# bm812inl.net
KiCad netlist of a schematic drawn in EAGLE
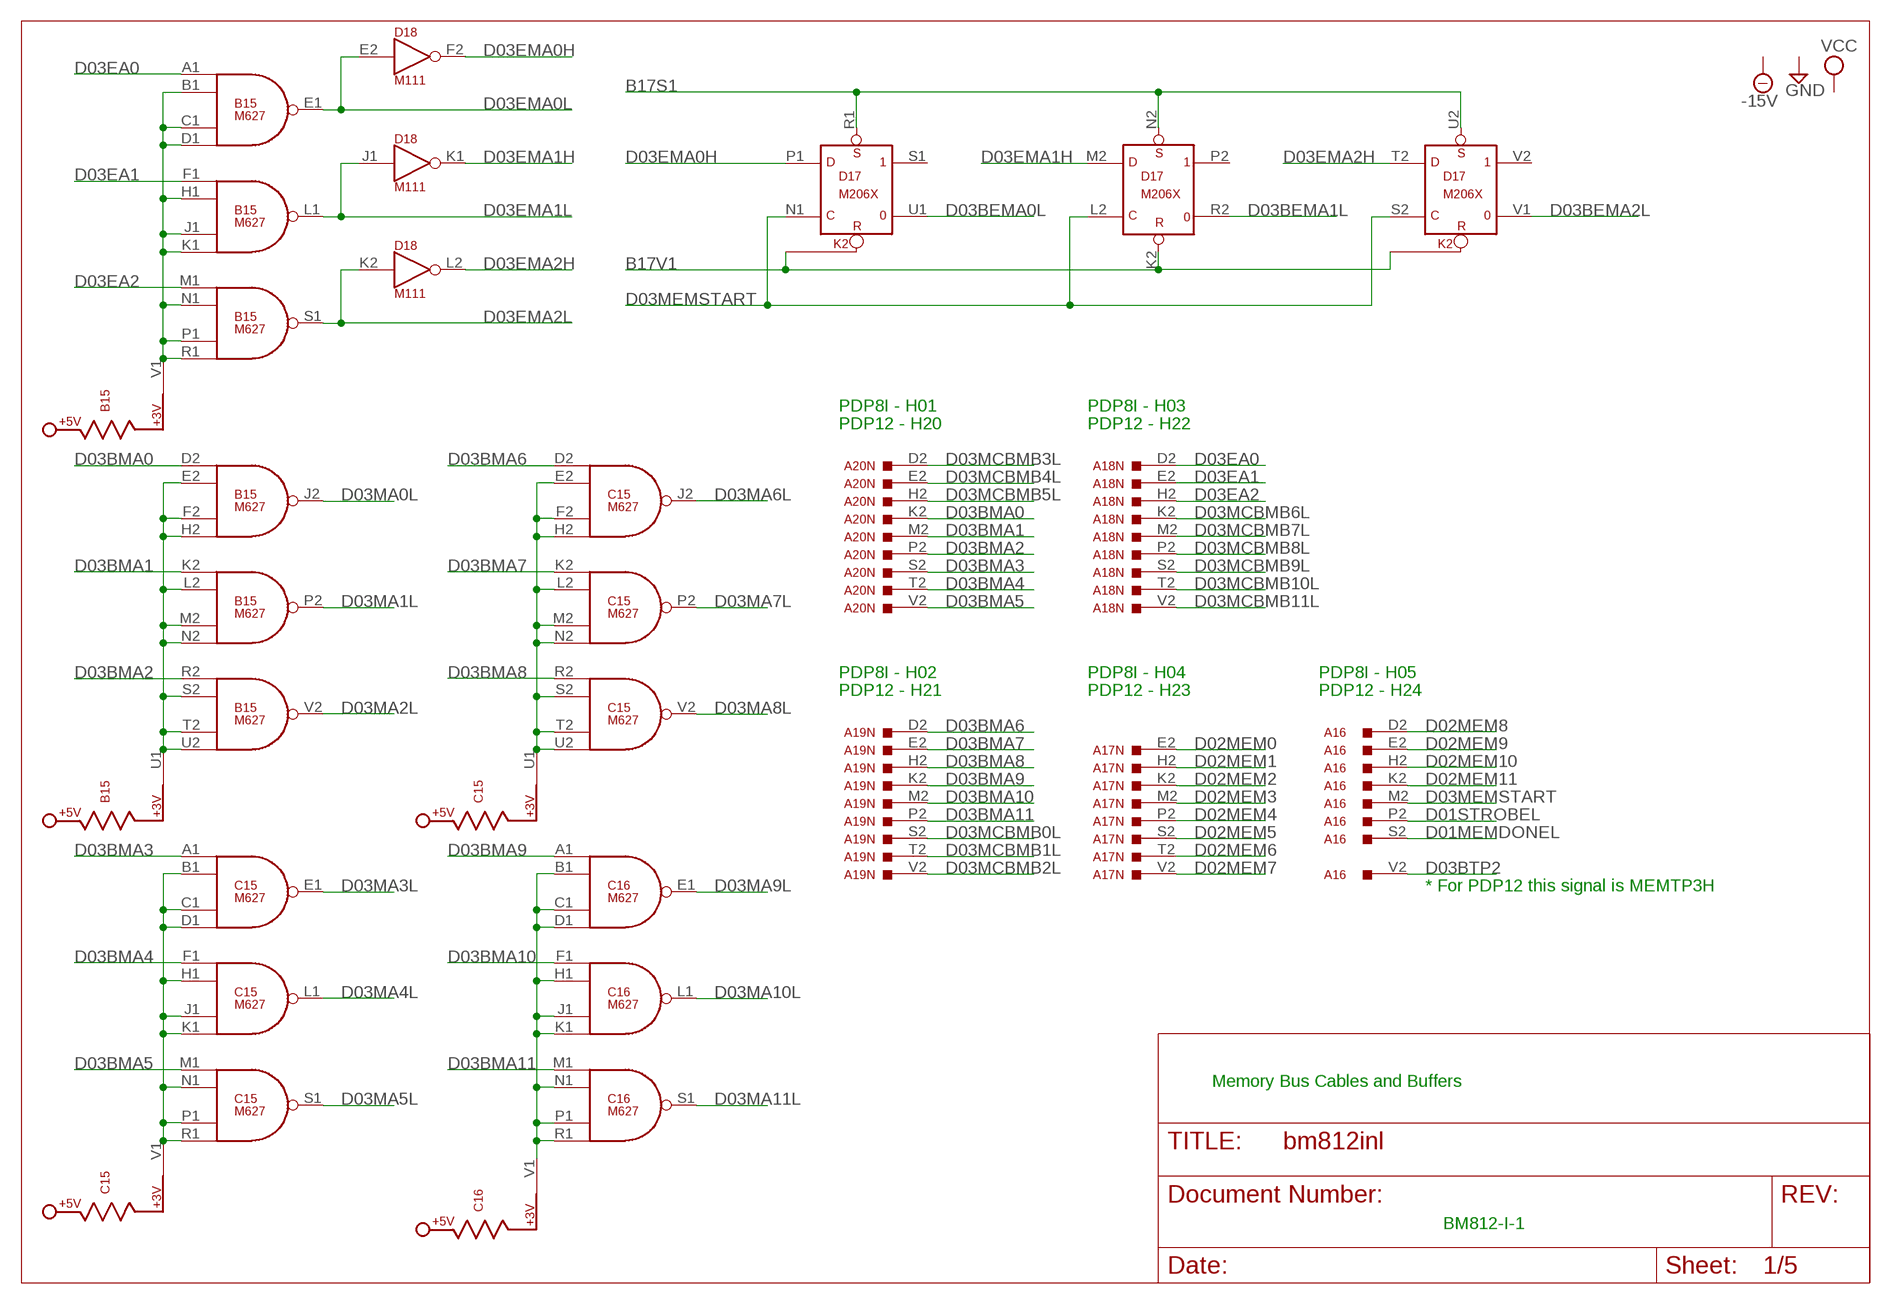
[diagram p0: schematic, sheet 1]
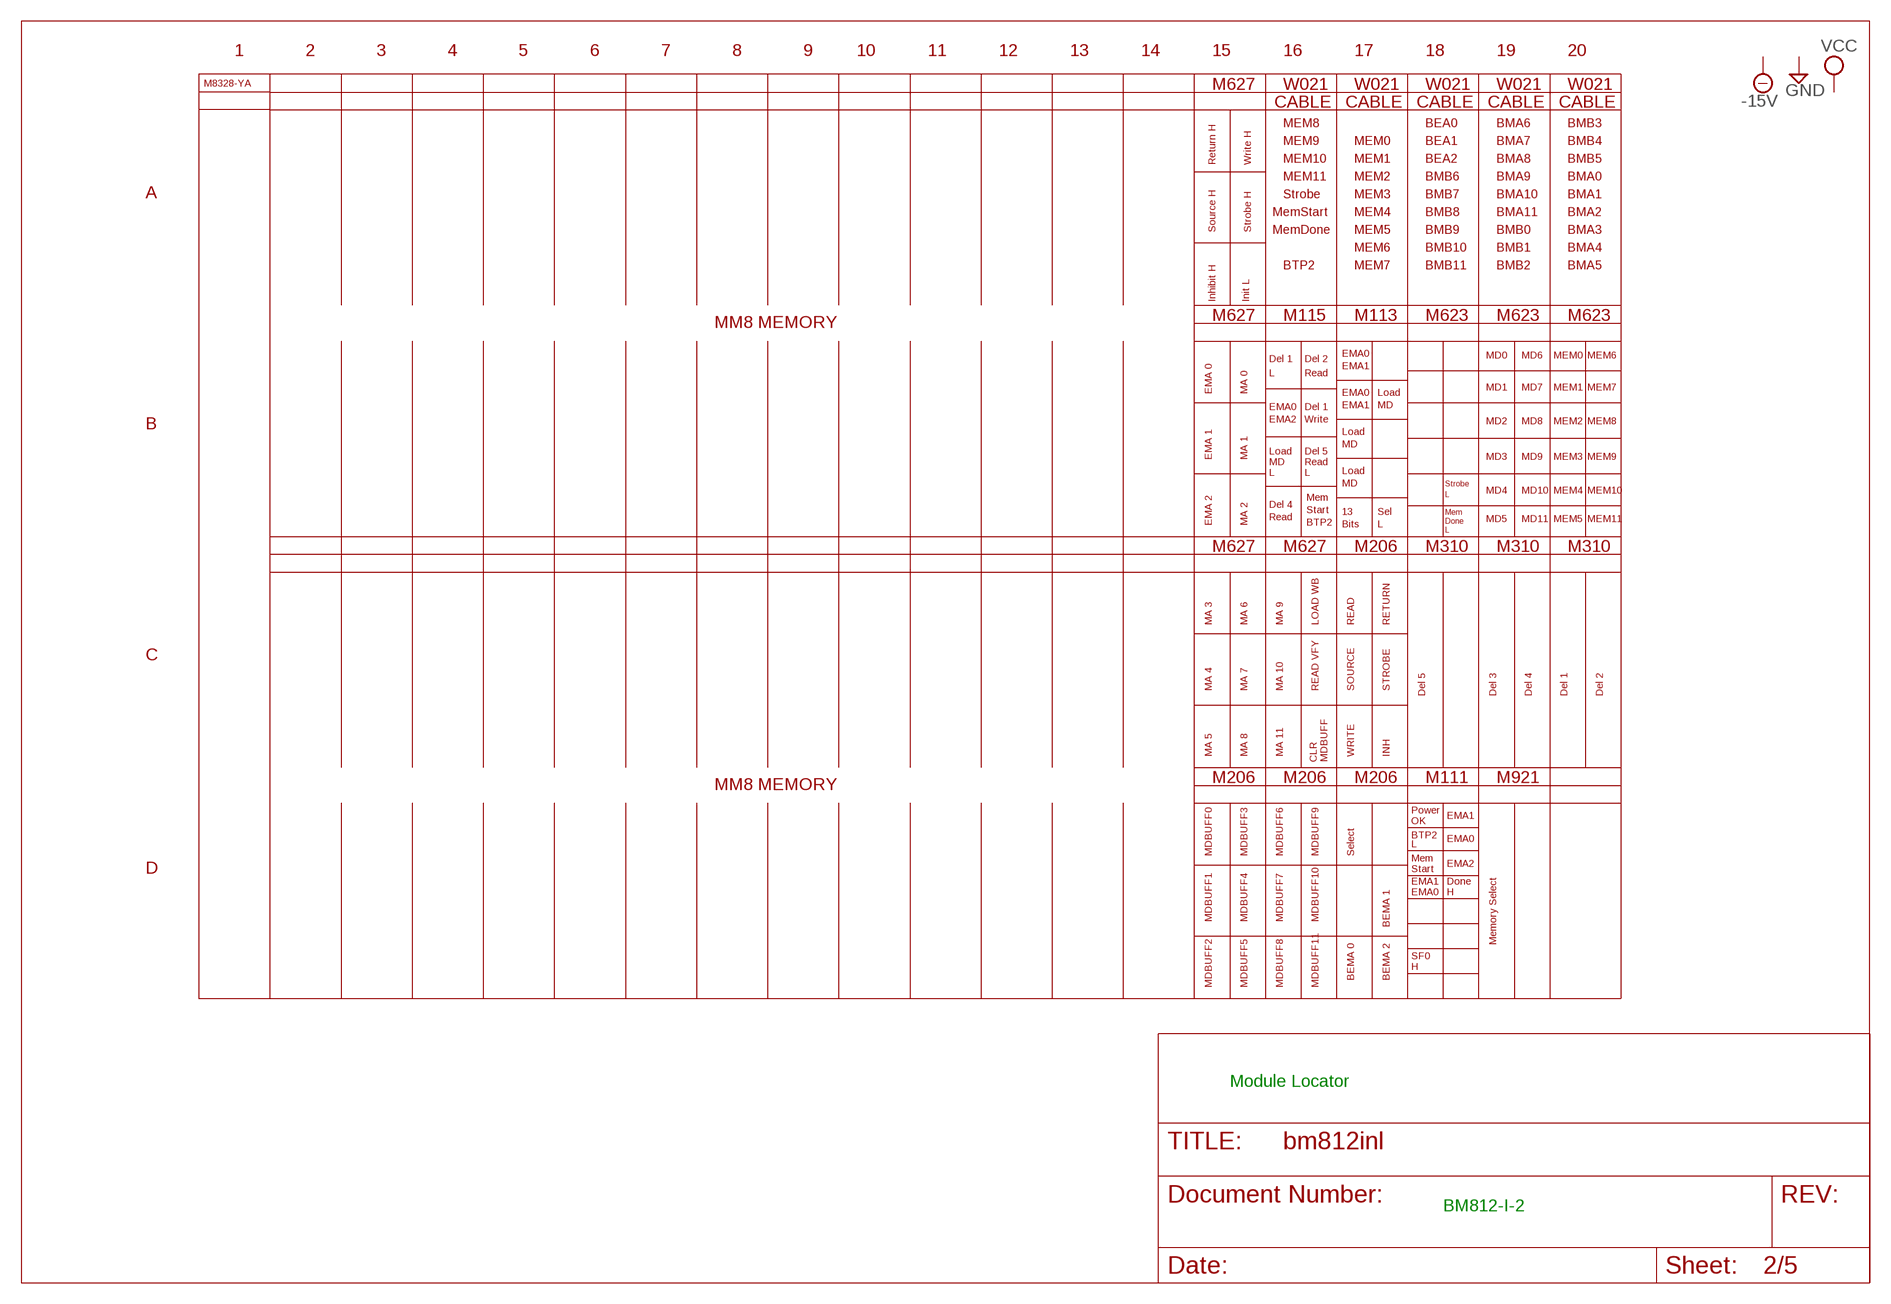
[diagram p1: schematic, sheet 2]
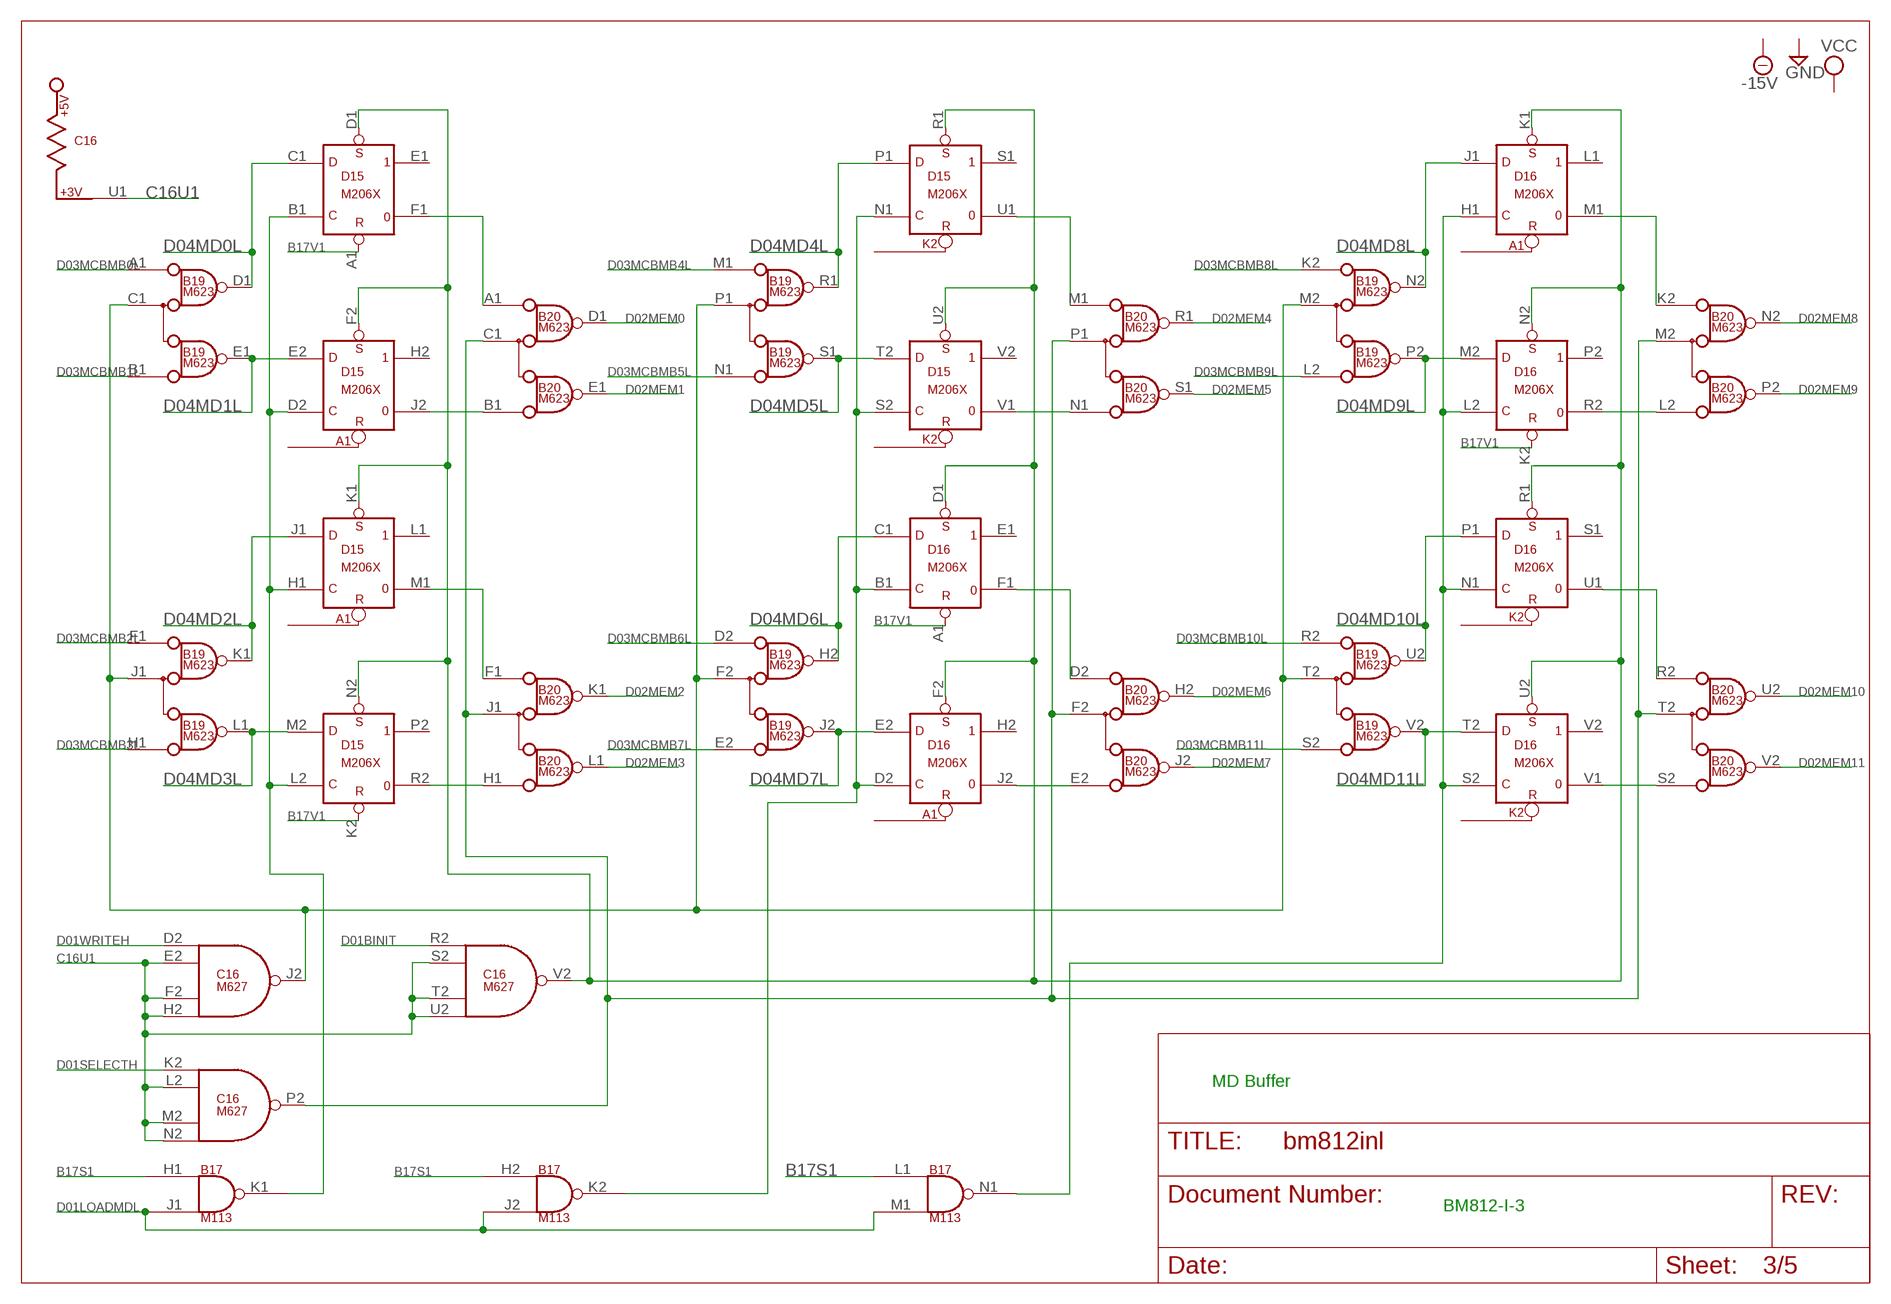
[diagram p2: schematic, sheet 3]
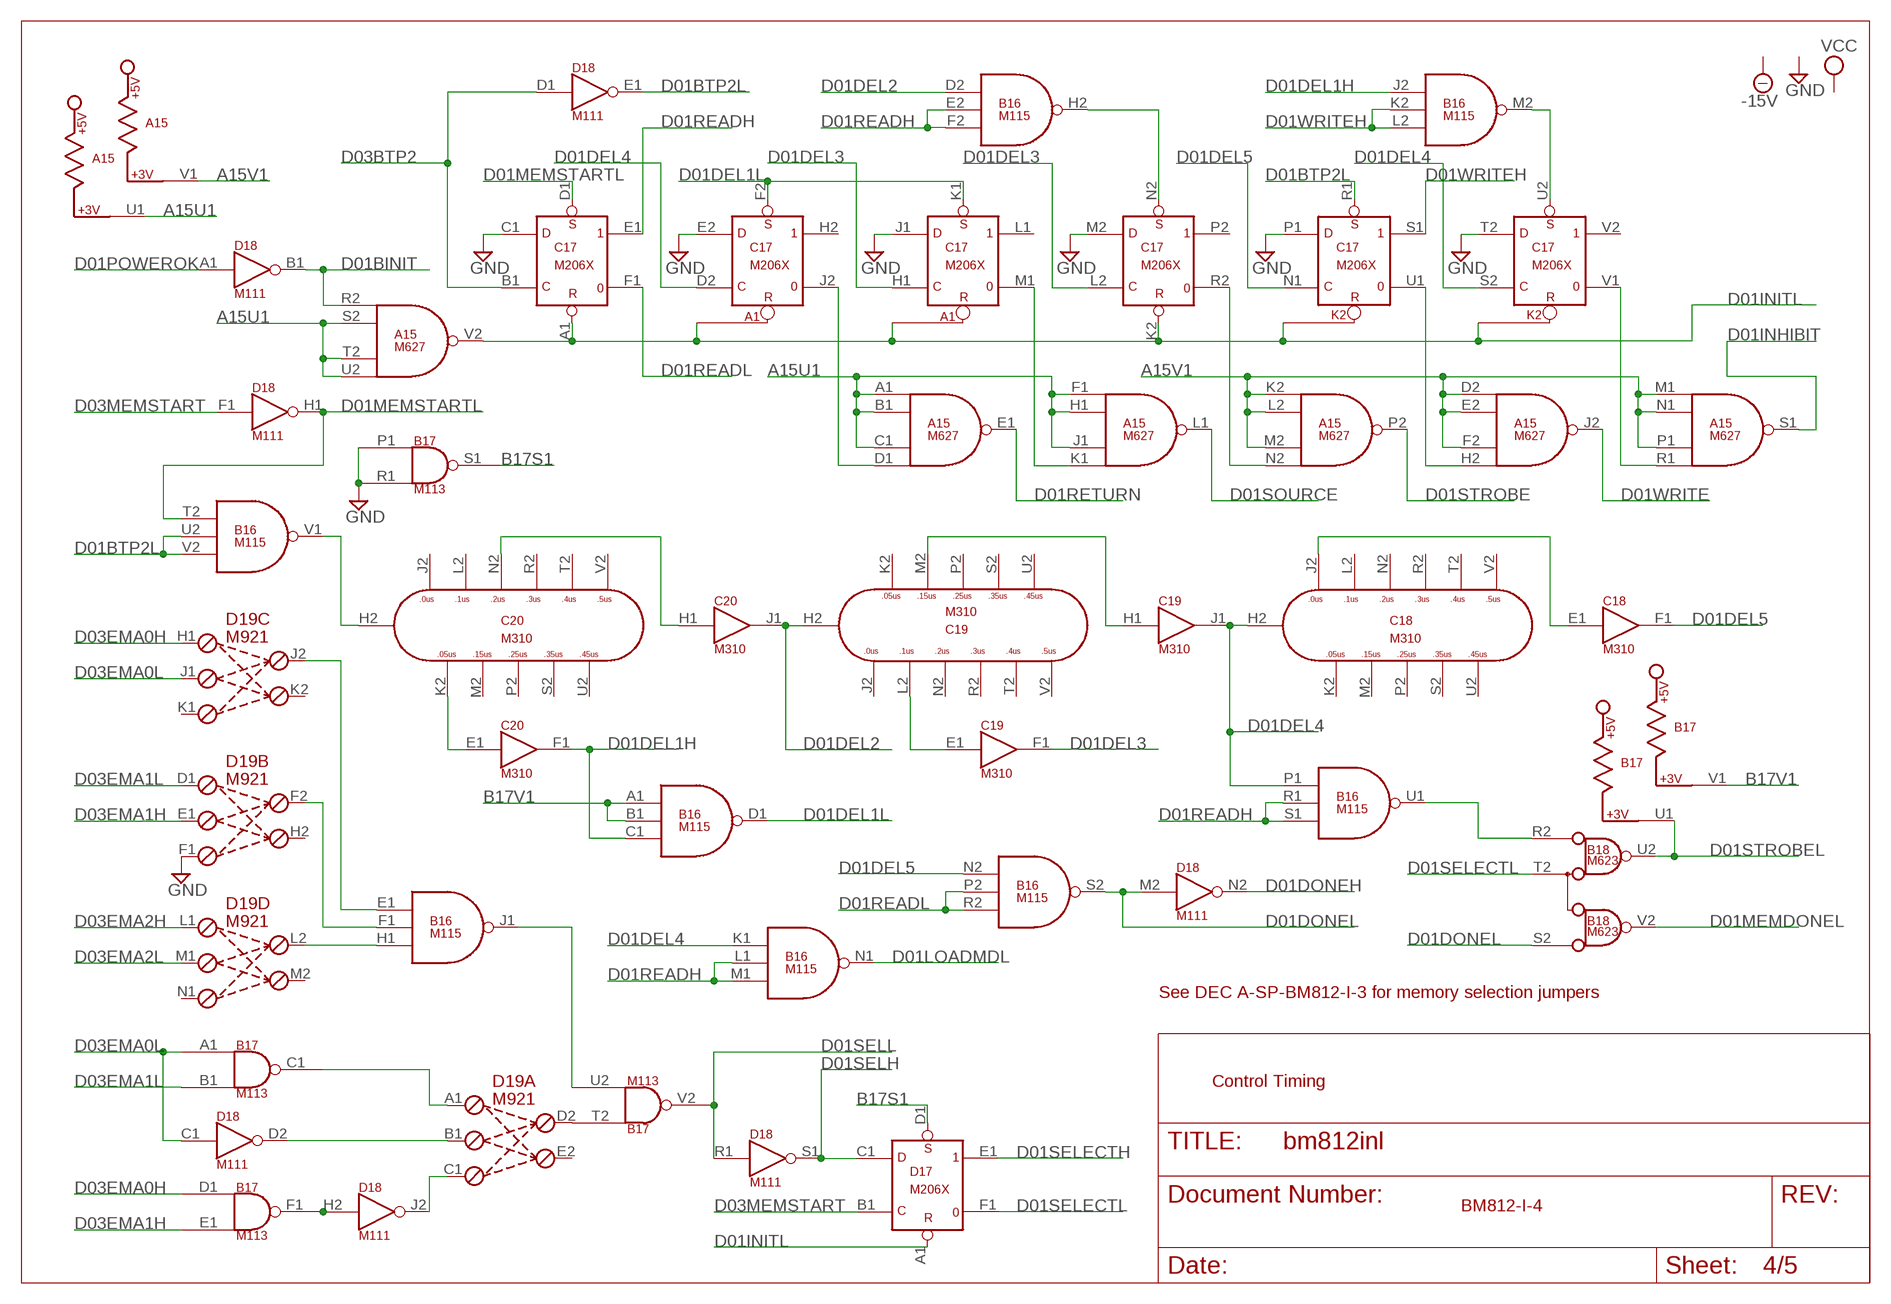
[diagram p3: schematic, sheet 4]
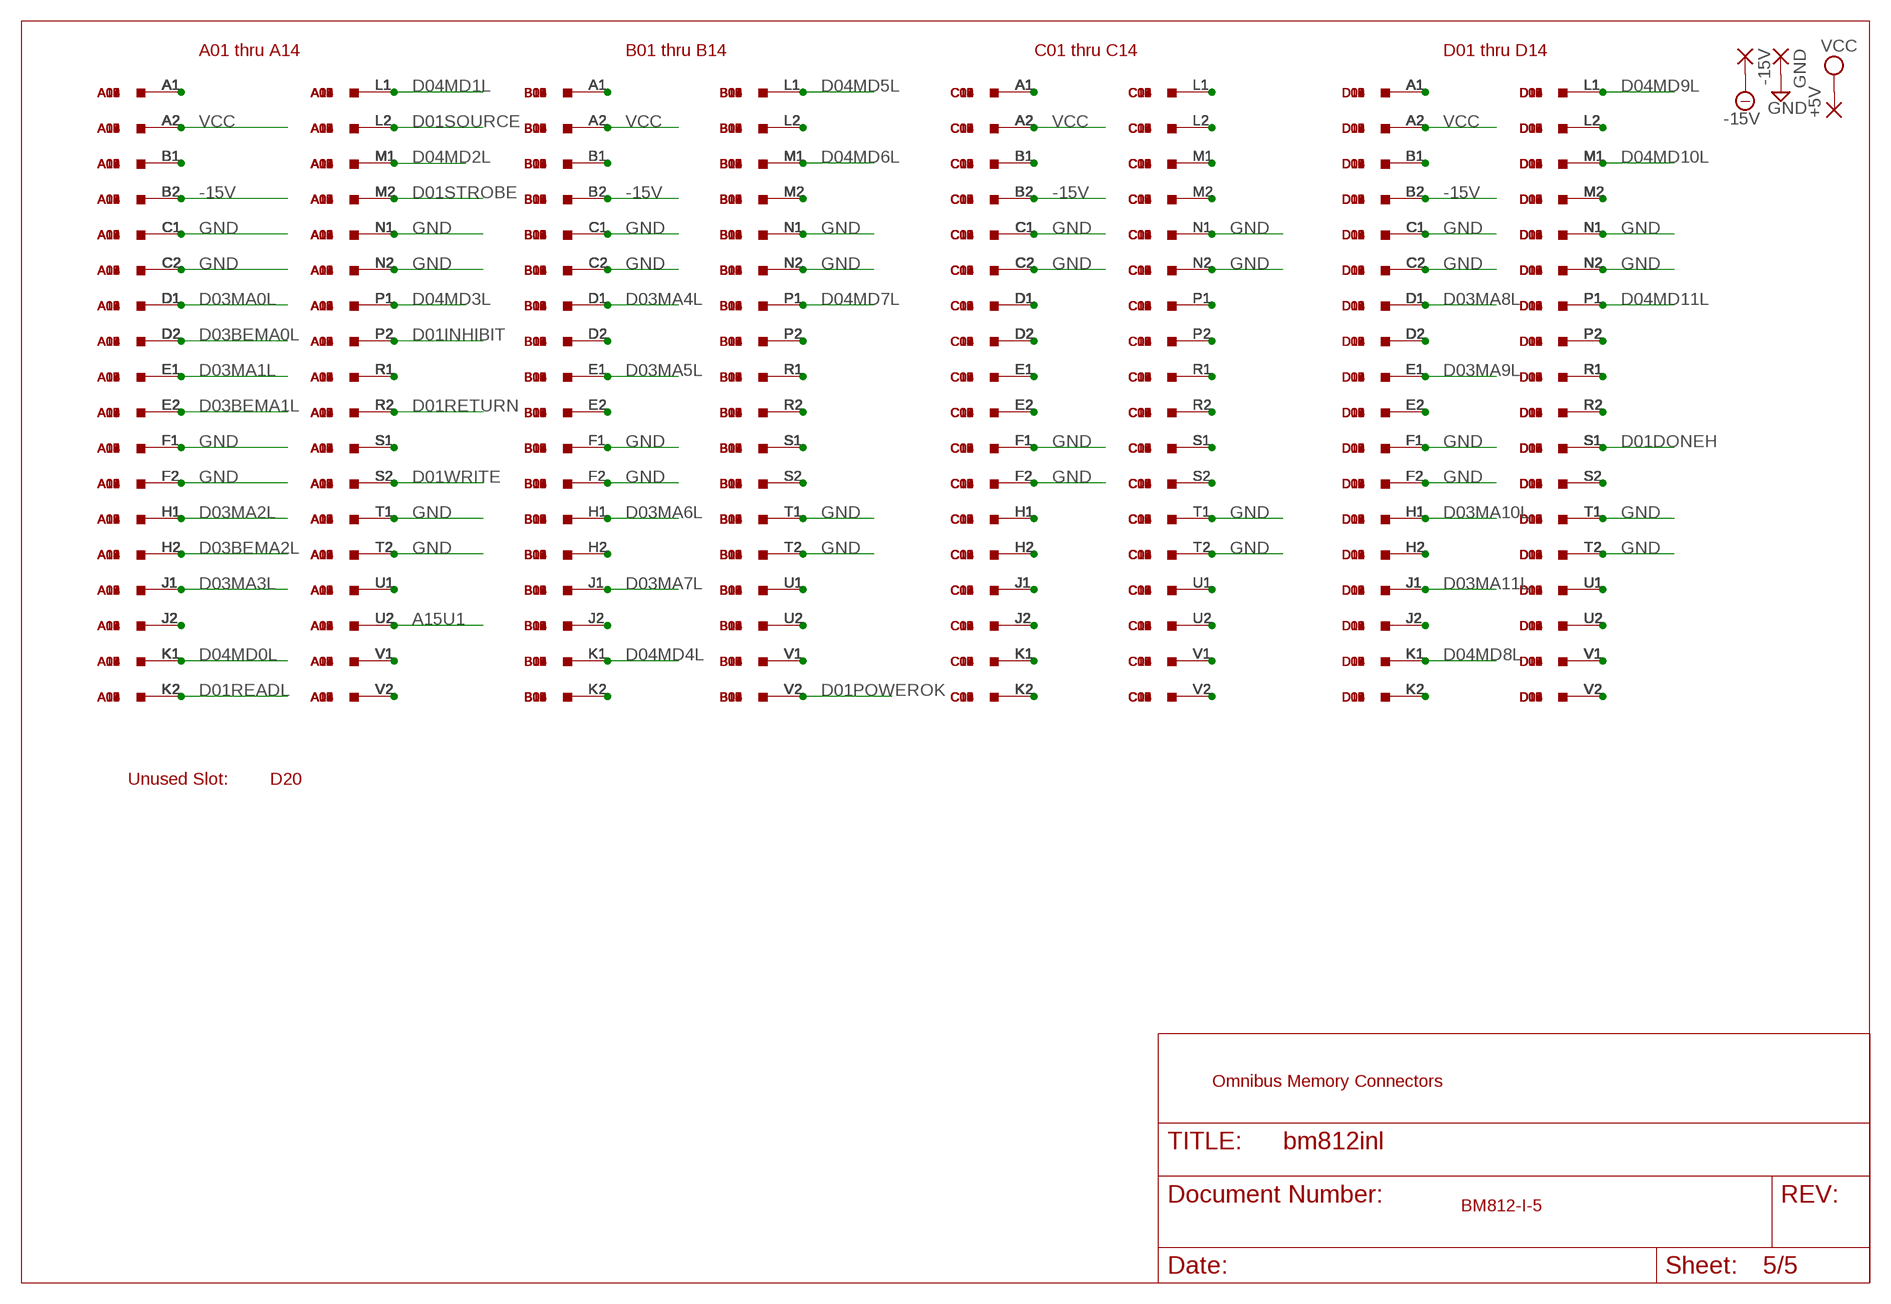
[diagram p4: schematic, sheet 5]

(export (version "E")
  (design (tool "Eeschema 10.0.6"))
  (components
    (comp (ref "A16")
      (value "M903")
      (footprint "eagle-import:H807")
      (libsource (lib "eagle-import") (part "M903"))
    )
    (comp (ref "A17N")
      (value "M903")
      (footprint "eagle-import:H807")
      (libsource (lib "eagle-import") (part "M903"))
    )
    (comp (ref "A18N")
      (value "M903")
      (footprint "eagle-import:H807")
      (libsource (lib "eagle-import") (part "M903"))
    )
    (comp (ref "A19N")
      (value "M903")
      (footprint "eagle-import:H807")
      (libsource (lib "eagle-import") (part "M903"))
    )
    (comp (ref "A20N")
      (value "M903")
      (footprint "eagle-import:H807")
      (libsource (lib "eagle-import") (part "M903"))
    )
    (comp (ref "B15")
      (value "M627")
      (footprint "eagle-import:H807")
      (libsource (lib "eagle-import") (part "M627"))
    )
    (comp (ref "C15")
      (value "M627")
      (footprint "eagle-import:H807")
      (libsource (lib "eagle-import") (part "M627"))
    )
    (comp (ref "C16")
      (value "M627")
      (footprint "eagle-import:H807")
      (libsource (lib "eagle-import") (part "M627"))
    )
    (comp (ref "D17")
      (value "M206X")
      (footprint "eagle-import:H807")
      (libsource (lib "eagle-import") (part "M206X"))
    )
    (comp (ref "D18")
      (value "M111")
      (footprint "eagle-import:H807")
      (libsource (lib "eagle-import") (part "M111"))
    )
    (comp (ref "A15")
      (value "M627")
      (footprint "eagle-import:H807")
      (libsource (lib "eagle-import") (part "M627"))
    )
    (comp (ref "B16")
      (value "M115")
      (footprint "eagle-import:H807")
      (libsource (lib "eagle-import") (part "M115"))
    )
    (comp (ref "B17")
      (value "M113")
      (footprint "eagle-import:H807")
      (libsource (lib "eagle-import") (part "M113"))
    )
    (comp (ref "B18")
      (value "M623")
      (footprint "eagle-import:H807")
      (libsource (lib "eagle-import") (part "M623"))
    )
    (comp (ref "C17")
      (value "M206X")
      (footprint "eagle-import:H807")
      (libsource (lib "eagle-import") (part "M206X"))
    )
    (comp (ref "C18")
      (value "M310")
      (footprint "eagle-import:H807")
      (libsource (lib "eagle-import") (part "M310"))
    )
    (comp (ref "C19")
      (value "M310")
      (footprint "eagle-import:H807")
      (libsource (lib "eagle-import") (part "M310"))
    )
    (comp (ref "C20")
      (value "M310")
      (footprint "eagle-import:H807")
      (libsource (lib "eagle-import") (part "M310"))
    )
    (comp (ref "D19")
      (value "M921")
      (footprint "eagle-import:H807")
      (libsource (lib "eagle-import") (part "M921"))
    )
    (comp (ref "+5V")
      (value "2,54/0,8")
      (footprint "eagle-import:2,54_0,8")
      (libsource (lib "eagle-import") (part "2,54/0,8"))
    )
    (comp (ref "-15V")
      (value "2,54/0,8")
      (footprint "eagle-import:2,54_0,8")
      (libsource (lib "eagle-import") (part "2,54/0,8"))
    )
    (comp (ref "A01")
      (value "M916")
      (footprint "eagle-import:H807")
      (libsource (lib "eagle-import") (part "M916"))
    )
    (comp (ref "A02")
      (value "M916")
      (footprint "eagle-import:H807")
      (libsource (lib "eagle-import") (part "M916"))
    )
    (comp (ref "A03")
      (value "M916")
      (footprint "eagle-import:H807")
      (libsource (lib "eagle-import") (part "M916"))
    )
    (comp (ref "A04")
      (value "M916")
      (footprint "eagle-import:H807")
      (libsource (lib "eagle-import") (part "M916"))
    )
    (comp (ref "A05")
      (value "M916")
      (footprint "eagle-import:H807")
      (libsource (lib "eagle-import") (part "M916"))
    )
    (comp (ref "A06")
      (value "M916")
      (footprint "eagle-import:H807")
      (libsource (lib "eagle-import") (part "M916"))
    )
    (comp (ref "A07")
      (value "M916")
      (footprint "eagle-import:H807")
      (libsource (lib "eagle-import") (part "M916"))
    )
    (comp (ref "A08")
      (value "M916")
      (footprint "eagle-import:H807")
      (libsource (lib "eagle-import") (part "M916"))
    )
    (comp (ref "A09")
      (value "M916")
      (footprint "eagle-import:H807")
      (libsource (lib "eagle-import") (part "M916"))
    )
    (comp (ref "A10")
      (value "M916")
      (footprint "eagle-import:H807")
      (libsource (lib "eagle-import") (part "M916"))
    )
    (comp (ref "A11")
      (value "M916")
      (footprint "eagle-import:H807")
      (libsource (lib "eagle-import") (part "M916"))
    )
    (comp (ref "A12")
      (value "M916")
      (footprint "eagle-import:H807")
      (libsource (lib "eagle-import") (part "M916"))
    )
    (comp (ref "A13")
      (value "M916")
      (footprint "eagle-import:H807")
      (libsource (lib "eagle-import") (part "M916"))
    )
    (comp (ref "A14")
      (value "M916")
      (footprint "eagle-import:H807")
      (libsource (lib "eagle-import") (part "M916"))
    )
    (comp (ref "B01")
      (value "M916")
      (footprint "eagle-import:H807")
      (libsource (lib "eagle-import") (part "M916"))
    )
    (comp (ref "B02")
      (value "M916")
      (footprint "eagle-import:H807")
      (libsource (lib "eagle-import") (part "M916"))
    )
    (comp (ref "B03")
      (value "M916")
      (footprint "eagle-import:H807")
      (libsource (lib "eagle-import") (part "M916"))
    )
    (comp (ref "B04")
      (value "M916")
      (footprint "eagle-import:H807")
      (libsource (lib "eagle-import") (part "M916"))
    )
    (comp (ref "B05")
      (value "M916")
      (footprint "eagle-import:H807")
      (libsource (lib "eagle-import") (part "M916"))
    )
    (comp (ref "B06")
      (value "M916")
      (footprint "eagle-import:H807")
      (libsource (lib "eagle-import") (part "M916"))
    )
    (comp (ref "B07")
      (value "M916")
      (footprint "eagle-import:H807")
      (libsource (lib "eagle-import") (part "M916"))
    )
    (comp (ref "B08")
      (value "M916")
      (footprint "eagle-import:H807")
      (libsource (lib "eagle-import") (part "M916"))
    )
    (comp (ref "B09")
      (value "M916")
      (footprint "eagle-import:H807")
      (libsource (lib "eagle-import") (part "M916"))
    )
    (comp (ref "B10")
      (value "M916")
      (footprint "eagle-import:H807")
      (libsource (lib "eagle-import") (part "M916"))
    )
    (comp (ref "B11")
      (value "M916")
      (footprint "eagle-import:H807")
      (libsource (lib "eagle-import") (part "M916"))
    )
    (comp (ref "B12")
      (value "M916")
      (footprint "eagle-import:H807")
      (libsource (lib "eagle-import") (part "M916"))
    )
    (comp (ref "B13")
      (value "M916")
      (footprint "eagle-import:H807")
      (libsource (lib "eagle-import") (part "M916"))
    )
    (comp (ref "B14")
      (value "M916")
      (footprint "eagle-import:H807")
      (libsource (lib "eagle-import") (part "M916"))
    )
    (comp (ref "C01")
      (value "M916")
      (footprint "eagle-import:H807")
      (libsource (lib "eagle-import") (part "M916"))
    )
    (comp (ref "C02")
      (value "M916")
      (footprint "eagle-import:H807")
      (libsource (lib "eagle-import") (part "M916"))
    )
    (comp (ref "C03")
      (value "M916")
      (footprint "eagle-import:H807")
      (libsource (lib "eagle-import") (part "M916"))
    )
    (comp (ref "C04")
      (value "M916")
      (footprint "eagle-import:H807")
      (libsource (lib "eagle-import") (part "M916"))
    )
    (comp (ref "C05")
      (value "M916")
      (footprint "eagle-import:H807")
      (libsource (lib "eagle-import") (part "M916"))
    )
    (comp (ref "C06")
      (value "M916")
      (footprint "eagle-import:H807")
      (libsource (lib "eagle-import") (part "M916"))
    )
    (comp (ref "C07")
      (value "M916")
      (footprint "eagle-import:H807")
      (libsource (lib "eagle-import") (part "M916"))
    )
    (comp (ref "C08")
      (value "M916")
      (footprint "eagle-import:H807")
      (libsource (lib "eagle-import") (part "M916"))
    )
    (comp (ref "C09")
      (value "M916")
      (footprint "eagle-import:H807")
      (libsource (lib "eagle-import") (part "M916"))
    )
    (comp (ref "C10")
      (value "M916")
      (footprint "eagle-import:H807")
      (libsource (lib "eagle-import") (part "M916"))
    )
    (comp (ref "C11")
      (value "M916")
      (footprint "eagle-import:H807")
      (libsource (lib "eagle-import") (part "M916"))
    )
    (comp (ref "C12")
      (value "M916")
      (footprint "eagle-import:H807")
      (libsource (lib "eagle-import") (part "M916"))
    )
    (comp (ref "C13")
      (value "M916")
      (footprint "eagle-import:H807")
      (libsource (lib "eagle-import") (part "M916"))
    )
    (comp (ref "C14")
      (value "M916")
      (footprint "eagle-import:H807")
      (libsource (lib "eagle-import") (part "M916"))
    )
    (comp (ref "D01")
      (value "M916")
      (footprint "eagle-import:H807")
      (libsource (lib "eagle-import") (part "M916"))
    )
    (comp (ref "D02")
      (value "M916")
      (footprint "eagle-import:H807")
      (libsource (lib "eagle-import") (part "M916"))
    )
    (comp (ref "D03")
      (value "M916")
      (footprint "eagle-import:H807")
      (libsource (lib "eagle-import") (part "M916"))
    )
    (comp (ref "D04")
      (value "M916")
      (footprint "eagle-import:H807")
      (libsource (lib "eagle-import") (part "M916"))
    )
    (comp (ref "D05")
      (value "M916")
      (footprint "eagle-import:H807")
      (libsource (lib "eagle-import") (part "M916"))
    )
    (comp (ref "D06")
      (value "M916")
      (footprint "eagle-import:H807")
      (libsource (lib "eagle-import") (part "M916"))
    )
    (comp (ref "D07")
      (value "M916")
      (footprint "eagle-import:H807")
      (libsource (lib "eagle-import") (part "M916"))
    )
    (comp (ref "D08")
      (value "M916")
      (footprint "eagle-import:H807")
      (libsource (lib "eagle-import") (part "M916"))
    )
    (comp (ref "D09")
      (value "M916")
      (footprint "eagle-import:H807")
      (libsource (lib "eagle-import") (part "M916"))
    )
    (comp (ref "D10")
      (value "M916")
      (footprint "eagle-import:H807")
      (libsource (lib "eagle-import") (part "M916"))
    )
    (comp (ref "D11")
      (value "M916")
      (footprint "eagle-import:H807")
      (libsource (lib "eagle-import") (part "M916"))
    )
    (comp (ref "D12")
      (value "M916")
      (footprint "eagle-import:H807")
      (libsource (lib "eagle-import") (part "M916"))
    )
    (comp (ref "D13")
      (value "M916")
      (footprint "eagle-import:H807")
      (libsource (lib "eagle-import") (part "M916"))
    )
    (comp (ref "D14")
      (value "M916")
      (footprint "eagle-import:H807")
      (libsource (lib "eagle-import") (part "M916"))
    )
    (comp (ref "D20")
      (value "H807")
      (footprint "eagle-import:H807")
      (libsource (lib "eagle-import") (part "H807"))
    )
    (comp (ref "GND")
      (value "2,54/0,8")
      (footprint "eagle-import:2,54_0,8")
      (libsource (lib "eagle-import") (part "2,54/0,8"))
    )
    (comp (ref "B19")
      (value "M623")
      (footprint "eagle-import:H807")
      (libsource (lib "eagle-import") (part "M623"))
    )
    (comp (ref "B20")
      (value "M623")
      (footprint "eagle-import:H807")
      (libsource (lib "eagle-import") (part "M623"))
    )
    (comp (ref "D15")
      (value "M206X")
      (footprint "eagle-import:H807")
      (libsource (lib "eagle-import") (part "M206X"))
    )
    (comp (ref "D16")
      (value "M206X")
      (footprint "eagle-import:H807")
      (libsource (lib "eagle-import") (part "M206X"))
    )
  )
  (nets
    (net (code "1") (name "-15V") (class "Default")
      (node (ref "-15V") (pin "1") (pinfunction "P_1") (pintype "passive"))
      (node (ref "A01") (pin "B2") (pinfunction "P$2_B2") (pintype "bidirectional"))
      (node (ref "A02") (pin "B2") (pinfunction "P$2_B2") (pintype "bidirectional"))
      (node (ref "A03") (pin "B2") (pinfunction "P$2_B2") (pintype "bidirectional"))
      (node (ref "A04") (pin "B2") (pinfunction "P$2_B2") (pintype "bidirectional"))
      (node (ref "A05") (pin "B2") (pinfunction "P$2_B2") (pintype "bidirectional"))
      (node (ref "A06") (pin "B2") (pinfunction "P$2_B2") (pintype "bidirectional"))
      (node (ref "A07") (pin "B2") (pinfunction "P$2_B2") (pintype "bidirectional"))
      (node (ref "A08") (pin "B2") (pinfunction "P$2_B2") (pintype "bidirectional"))
      (node (ref "A09") (pin "B2") (pinfunction "P$2_B2") (pintype "bidirectional"))
      (node (ref "A10") (pin "B2") (pinfunction "P$2_B2") (pintype "bidirectional"))
      (node (ref "A11") (pin "B2") (pinfunction "P$2_B2") (pintype "bidirectional"))
      (node (ref "A12") (pin "B2") (pinfunction "P$2_B2") (pintype "bidirectional"))
      (node (ref "A13") (pin "B2") (pinfunction "P$2_B2") (pintype "bidirectional"))
      (node (ref "A14") (pin "B2") (pinfunction "P$2_B2") (pintype "bidirectional"))
      (node (ref "B01") (pin "B2") (pinfunction "P$2_B2") (pintype "bidirectional"))
      (node (ref "B02") (pin "B2") (pinfunction "P$2_B2") (pintype "bidirectional"))
      (node (ref "B03") (pin "B2") (pinfunction "P$2_B2") (pintype "bidirectional"))
      (node (ref "B04") (pin "B2") (pinfunction "P$2_B2") (pintype "bidirectional"))
      (node (ref "B05") (pin "B2") (pinfunction "P$2_B2") (pintype "bidirectional"))
      (node (ref "B06") (pin "B2") (pinfunction "P$2_B2") (pintype "bidirectional"))
      (node (ref "B07") (pin "B2") (pinfunction "P$2_B2") (pintype "bidirectional"))
      (node (ref "B08") (pin "B2") (pinfunction "P$2_B2") (pintype "bidirectional"))
      (node (ref "B09") (pin "B2") (pinfunction "P$2_B2") (pintype "bidirectional"))
      (node (ref "B10") (pin "B2") (pinfunction "P$2_B2") (pintype "bidirectional"))
      (node (ref "B11") (pin "B2") (pinfunction "P$2_B2") (pintype "bidirectional"))
      (node (ref "B12") (pin "B2") (pinfunction "P$2_B2") (pintype "bidirectional"))
      (node (ref "B13") (pin "B2") (pinfunction "P$2_B2") (pintype "bidirectional"))
      (node (ref "B14") (pin "B2") (pinfunction "P$2_B2") (pintype "bidirectional"))
      (node (ref "C01") (pin "B2") (pinfunction "P$2_B2") (pintype "bidirectional"))
      (node (ref "C02") (pin "B2") (pinfunction "P$2_B2") (pintype "bidirectional"))
      (node (ref "C03") (pin "B2") (pinfunction "P$2_B2") (pintype "bidirectional"))
      (node (ref "C04") (pin "B2") (pinfunction "P$2_B2") (pintype "bidirectional"))
      (node (ref "C05") (pin "B2") (pinfunction "P$2_B2") (pintype "bidirectional"))
      (node (ref "C06") (pin "B2") (pinfunction "P$2_B2") (pintype "bidirectional"))
      (node (ref "C07") (pin "B2") (pinfunction "P$2_B2") (pintype "bidirectional"))
      (node (ref "C08") (pin "B2") (pinfunction "P$2_B2") (pintype "bidirectional"))
      (node (ref "C09") (pin "B2") (pinfunction "P$2_B2") (pintype "bidirectional"))
      (node (ref "C10") (pin "B2") (pinfunction "P$2_B2") (pintype "bidirectional"))
      (node (ref "C11") (pin "B2") (pinfunction "P$2_B2") (pintype "bidirectional"))
      (node (ref "C12") (pin "B2") (pinfunction "P$2_B2") (pintype "bidirectional"))
      (node (ref "C13") (pin "B2") (pinfunction "P$2_B2") (pintype "bidirectional"))
      (node (ref "C14") (pin "B2") (pinfunction "P$2_B2") (pintype "bidirectional"))
      (node (ref "D01") (pin "B2") (pinfunction "P$2_B2") (pintype "bidirectional"))
      (node (ref "D02") (pin "B2") (pinfunction "P$2_B2") (pintype "bidirectional"))
      (node (ref "D03") (pin "B2") (pinfunction "P$2_B2") (pintype "bidirectional"))
      (node (ref "D04") (pin "B2") (pinfunction "P$2_B2") (pintype "bidirectional"))
      (node (ref "D05") (pin "B2") (pinfunction "P$2_B2") (pintype "bidirectional"))
      (node (ref "D06") (pin "B2") (pinfunction "P$2_B2") (pintype "bidirectional"))
      (node (ref "D07") (pin "B2") (pinfunction "P$2_B2") (pintype "bidirectional"))
      (node (ref "D08") (pin "B2") (pinfunction "P$2_B2") (pintype "bidirectional"))
      (node (ref "D09") (pin "B2") (pinfunction "P$2_B2") (pintype "bidirectional"))
      (node (ref "D10") (pin "B2") (pinfunction "P$2_B2") (pintype "bidirectional"))
      (node (ref "D11") (pin "B2") (pinfunction "P$2_B2") (pintype "bidirectional"))
      (node (ref "D12") (pin "B2") (pinfunction "P$2_B2") (pintype "bidirectional"))
      (node (ref "D13") (pin "B2") (pinfunction "P$2_B2") (pintype "bidirectional"))
      (node (ref "D14") (pin "B2") (pinfunction "P$2_B2") (pintype "bidirectional"))
    )
    (net (code "2") (name "A15U1") (class "Default")
      (node (ref "A01") (pin "U2") (pinfunction "P$2_U2") (pintype "bidirectional"))
      (node (ref "A02") (pin "U2") (pinfunction "P$2_U2") (pintype "bidirectional"))
      (node (ref "A03") (pin "U2") (pinfunction "P$2_U2") (pintype "bidirectional"))
      (node (ref "A04") (pin "U2") (pinfunction "P$2_U2") (pintype "bidirectional"))
      (node (ref "A05") (pin "U2") (pinfunction "P$2_U2") (pintype "bidirectional"))
      (node (ref "A06") (pin "U2") (pinfunction "P$2_U2") (pintype "bidirectional"))
      (node (ref "A07") (pin "U2") (pinfunction "P$2_U2") (pintype "bidirectional"))
      (node (ref "A08") (pin "U2") (pinfunction "P$2_U2") (pintype "bidirectional"))
      (node (ref "A09") (pin "U2") (pinfunction "P$2_U2") (pintype "bidirectional"))
      (node (ref "A10") (pin "U2") (pinfunction "P$2_U2") (pintype "bidirectional"))
      (node (ref "A11") (pin "U2") (pinfunction "P$2_U2") (pintype "bidirectional"))
      (node (ref "A12") (pin "U2") (pinfunction "P$2_U2") (pintype "bidirectional"))
      (node (ref "A13") (pin "U2") (pinfunction "P$2_U2") (pintype "bidirectional"))
      (node (ref "A14") (pin "U2") (pinfunction "P$2_U2") (pintype "bidirectional"))
      (node (ref "A15") (pin "A1") (pinfunction "IN1_A1") (pintype "input"))
      (node (ref "A15") (pin "B1") (pinfunction "IN2_B1") (pintype "input"))
      (node (ref "A15") (pin "C1") (pinfunction "IN3_C1") (pintype "input"))
      (node (ref "A15") (pin "F1") (pinfunction "IN1_F1") (pintype "input"))
      (node (ref "A15") (pin "H1") (pinfunction "IN2_H1") (pintype "input"))
      (node (ref "A15") (pin "J1") (pinfunction "IN3_J1") (pintype "input"))
      (node (ref "A15") (pin "S2") (pinfunction "IN2_S2") (pintype "input"))
      (node (ref "A15") (pin "T2") (pinfunction "IN3_T2") (pintype "input"))
      (node (ref "A15") (pin "U1") (pinfunction "P$1_U1") (pintype "passive"))
      (node (ref "A15") (pin "U2") (pinfunction "IN4_U2") (pintype "input"))
    )
    (net (code "3") (name "A15V1") (class "Default")
      (node (ref "A15") (pin "D2") (pinfunction "IN1_D2") (pintype "input"))
      (node (ref "A15") (pin "E2") (pinfunction "IN2_E2") (pintype "input"))
      (node (ref "A15") (pin "F2") (pinfunction "IN3_F2") (pintype "input"))
      (node (ref "A15") (pin "K2") (pinfunction "IN1_K2") (pintype "input"))
      (node (ref "A15") (pin "L2") (pinfunction "IN2_L2") (pintype "input"))
      (node (ref "A15") (pin "M1") (pinfunction "IN1_M1") (pintype "input"))
      (node (ref "A15") (pin "M2") (pinfunction "IN3_M2") (pintype "input"))
      (node (ref "A15") (pin "N1") (pinfunction "IN2_N1") (pintype "input"))
      (node (ref "A15") (pin "P1") (pinfunction "IN3_P1") (pintype "input"))
      (node (ref "A15") (pin "V1") (pinfunction "P$1_V1") (pintype "passive"))
    )
    (net (code "4") (name "B17S1") (class "Default")
      (node (ref "B17") (pin "H1") (pinfunction "IN1_H1") (pintype "input"))
      (node (ref "B17") (pin "H2") (pinfunction "IN1_H2") (pintype "input"))
      (node (ref "B17") (pin "L1") (pinfunction "IN1_L1") (pintype "input"))
      (node (ref "B17") (pin "S1") (pinfunction "OUT_S1") (pintype "output"))
      (node (ref "D17") (pin "D1") (pinfunction "S_D1") (pintype "input"))
      (node (ref "D17") (pin "N2") (pinfunction "S_N2") (pintype "input"))
      (node (ref "D17") (pin "R1") (pinfunction "S_R1") (pintype "input"))
      (node (ref "D17") (pin "U2") (pinfunction "S_U2") (pintype "input"))
    )
    (net (code "5") (name "B17V1") (class "Default")
      (node (ref "B16") (pin "A1") (pinfunction "IN1_A1") (pintype "input"))
      (node (ref "B16") (pin "B1") (pinfunction "IN2_B1") (pintype "input"))
      (node (ref "B17") (pin "V1") (pinfunction "P$1_V1") (pintype "passive"))
      (node (ref "D15") (pin "A1") (pinfunction "R_A1") (pintype "input"))
      (node (ref "D15") (pin "K2") (pinfunction "R_K2") (pintype "input"))
      (node (ref "D16") (pin "A1") (pinfunction "R_A1") (pintype "input"))
      (node (ref "D16") (pin "K2") (pinfunction "R_K2") (pintype "input"))
      (node (ref "D17") (pin "K2") (pinfunction "R_K2") (pintype "input"))
    )
    (net (code "6") (name "C16U1") (class "Default")
      (node (ref "C16") (pin "E2") (pinfunction "IN2_E2") (pintype "input"))
      (node (ref "C16") (pin "F2") (pinfunction "IN3_F2") (pintype "input"))
      (node (ref "C16") (pin "H2") (pinfunction "IN4_H2") (pintype "input"))
      (node (ref "C16") (pin "L2") (pinfunction "IN2_L2") (pintype "input"))
      (node (ref "C16") (pin "M2") (pinfunction "IN3_M2") (pintype "input"))
      (node (ref "C16") (pin "N2") (pinfunction "IN4_N2") (pintype "input"))
      (node (ref "C16") (pin "S2") (pinfunction "IN2_S2") (pintype "input"))
      (node (ref "C16") (pin "T2") (pinfunction "IN3_T2") (pintype "input"))
      (node (ref "C16") (pin "U1") (pinfunction "P$1_U1") (pintype "passive"))
      (node (ref "C16") (pin "U2") (pinfunction "IN4_U2") (pintype "input"))
    )
    (net (code "7") (name "D01BINIT") (class "Default")
      (node (ref "A15") (pin "R2") (pinfunction "IN1_R2") (pintype "input"))
      (node (ref "C16") (pin "R2") (pinfunction "IN1_R2") (pintype "input"))
      (node (ref "D18") (pin "B1") (pinfunction "OUT_B1") (pintype "output"))
    )
    (net (code "8") (name "D01BTP2L") (class "Default")
      (node (ref "B16") (pin "U2") (pinfunction "IN2_U2") (pintype "input"))
      (node (ref "B16") (pin "V2") (pinfunction "IN3_V2") (pintype "input"))
      (node (ref "C17") (pin "R1") (pinfunction "S_R1") (pintype "input"))
      (node (ref "D18") (pin "E1") (pinfunction "OUT_E1") (pintype "output"))
    )
    (net (code "9") (name "D01DEL1H") (class "Default")
      (node (ref "B16") (pin "C1") (pinfunction "IN3_C1") (pintype "input"))
      (node (ref "B16") (pin "J2") (pinfunction "IN1_J2") (pintype "input"))
      (node (ref "C20") (pin "F1") (pinfunction "OUT_F1") (pintype "output"))
    )
    (net (code "10") (name "D01DEL1L") (class "Default")
      (node (ref "B16") (pin "D1") (pinfunction "OUT_D1") (pintype "output"))
      (node (ref "C17") (pin "F2") (pinfunction "S_F2") (pintype "input"))
      (node (ref "C17") (pin "K1") (pinfunction "S_K1") (pintype "input"))
    )
    (net (code "11") (name "D01DEL2") (class "Default")
      (node (ref "B16") (pin "D2") (pinfunction "IN1_D2") (pintype "input"))
      (node (ref "C19") (pin "H2") (pinfunction "H2_H2") (pintype "input"))
      (node (ref "C20") (pin "J1") (pinfunction "OUT_J1") (pintype "output"))
    )
    (net (code "12") (name "D01DEL3") (class "Default")
      (node (ref "C17") (pin "H1") (pinfunction "C_H1") (pintype "input"))
      (node (ref "C17") (pin "L2") (pinfunction "C_L2") (pintype "input"))
      (node (ref "C19") (pin "F1") (pinfunction "OUT_F1") (pintype "output"))
    )
    (net (code "13") (name "D01DEL4") (class "Default")
      (node (ref "B16") (pin "K1") (pinfunction "IN1_K1") (pintype "input"))
      (node (ref "B16") (pin "P1") (pinfunction "IN1_P1") (pintype "input"))
      (node (ref "C17") (pin "D2") (pinfunction "C_D2") (pintype "input"))
      (node (ref "C17") (pin "S2") (pinfunction "C_S2") (pintype "input"))
      (node (ref "C18") (pin "H2") (pinfunction "H2_H2") (pintype "input"))
      (node (ref "C19") (pin "J1") (pinfunction "OUT_J1") (pintype "output"))
    )
    (net (code "14") (name "D01DEL5") (class "Default")
      (node (ref "B16") (pin "N2") (pinfunction "IN1_N2") (pintype "input"))
      (node (ref "C17") (pin "N1") (pinfunction "C_N1") (pintype "input"))
      (node (ref "C18") (pin "F1") (pinfunction "OUT_F1") (pintype "output"))
    )
    (net (code "15") (name "D01DONEH") (class "Default")
      (node (ref "D01") (pin "S1") (pinfunction "P$2_S1") (pintype "bidirectional"))
      (node (ref "D02") (pin "S1") (pinfunction "P$2_S1") (pintype "bidirectional"))
      (node (ref "D03") (pin "S1") (pinfunction "P$2_S1") (pintype "bidirectional"))
      (node (ref "D04") (pin "S1") (pinfunction "P$2_S1") (pintype "bidirectional"))
      (node (ref "D05") (pin "S1") (pinfunction "P$2_S1") (pintype "bidirectional"))
      (node (ref "D06") (pin "S1") (pinfunction "P$2_S1") (pintype "bidirectional"))
      (node (ref "D07") (pin "S1") (pinfunction "P$2_S1") (pintype "bidirectional"))
      (node (ref "D08") (pin "S1") (pinfunction "P$2_S1") (pintype "bidirectional"))
      (node (ref "D09") (pin "S1") (pinfunction "P$2_S1") (pintype "bidirectional"))
      (node (ref "D10") (pin "S1") (pinfunction "P$2_S1") (pintype "bidirectional"))
      (node (ref "D11") (pin "S1") (pinfunction "P$2_S1") (pintype "bidirectional"))
      (node (ref "D12") (pin "S1") (pinfunction "P$2_S1") (pintype "bidirectional"))
      (node (ref "D13") (pin "S1") (pinfunction "P$2_S1") (pintype "bidirectional"))
      (node (ref "D14") (pin "S1") (pinfunction "P$2_S1") (pintype "bidirectional"))
      (node (ref "D18") (pin "N2") (pinfunction "OUT_N2") (pintype "output"))
    )
    (net (code "16") (name "D01DONEL") (class "Default")
      (node (ref "B16") (pin "S2") (pinfunction "OUT_S2") (pintype "output"))
      (node (ref "B18") (pin "S2") (pinfunction "B_S2") (pintype "input"))
      (node (ref "D18") (pin "M2") (pinfunction "IN_M2") (pintype "input"))
    )
    (net (code "17") (name "D01INHIBIT") (class "Default")
      (node (ref "A01") (pin "P2") (pinfunction "P$2_P2") (pintype "bidirectional"))
      (node (ref "A02") (pin "P2") (pinfunction "P$2_P2") (pintype "bidirectional"))
      (node (ref "A03") (pin "P2") (pinfunction "P$2_P2") (pintype "bidirectional"))
      (node (ref "A04") (pin "P2") (pinfunction "P$2_P2") (pintype "bidirectional"))
      (node (ref "A05") (pin "P2") (pinfunction "P$2_P2") (pintype "bidirectional"))
      (node (ref "A06") (pin "P2") (pinfunction "P$2_P2") (pintype "bidirectional"))
      (node (ref "A07") (pin "P2") (pinfunction "P$2_P2") (pintype "bidirectional"))
      (node (ref "A08") (pin "P2") (pinfunction "P$2_P2") (pintype "bidirectional"))
      (node (ref "A09") (pin "P2") (pinfunction "P$2_P2") (pintype "bidirectional"))
      (node (ref "A10") (pin "P2") (pinfunction "P$2_P2") (pintype "bidirectional"))
      (node (ref "A11") (pin "P2") (pinfunction "P$2_P2") (pintype "bidirectional"))
      (node (ref "A12") (pin "P2") (pinfunction "P$2_P2") (pintype "bidirectional"))
      (node (ref "A13") (pin "P2") (pinfunction "P$2_P2") (pintype "bidirectional"))
      (node (ref "A14") (pin "P2") (pinfunction "P$2_P2") (pintype "bidirectional"))
      (node (ref "A15") (pin "S1") (pinfunction "OUT_S1") (pintype "output"))
    )
    (net (code "18") (name "D01INITL") (class "Default")
      (node (ref "A15") (pin "V2") (pinfunction "OUT_V2") (pintype "output"))
      (node (ref "C17") (pin "A1") (pinfunction "R_A1") (pintype "input"))
      (node (ref "C17") (pin "K2") (pinfunction "R_K2") (pintype "input"))
      (node (ref "D17") (pin "A1") (pinfunction "R_A1") (pintype "input"))
    )
    (net (code "19") (name "D01LOADMDL") (class "Default")
      (node (ref "B16") (pin "N1") (pinfunction "OUT_N1") (pintype "output"))
      (node (ref "B17") (pin "J1") (pinfunction "IN2_J1") (pintype "input"))
      (node (ref "B17") (pin "J2") (pinfunction "IN2_J2") (pintype "input"))
      (node (ref "B17") (pin "M1") (pinfunction "IN2_M1") (pintype "input"))
    )
    (net (code "20") (name "D01MEMDONEL") (class "Default")
      (node (ref "A16") (pin "S2") (pinfunction "P$2_S2") (pintype "bidirectional"))
      (node (ref "B18") (pin "V2") (pinfunction "E_V2") (pintype "open_collector"))
    )
    (net (code "21") (name "D01MEMSTARTL") (class "Default")
      (node (ref "B16") (pin "T2") (pinfunction "IN1_T2") (pintype "input"))
      (node (ref "C17") (pin "D1") (pinfunction "S_D1") (pintype "input"))
      (node (ref "D18") (pin "H1") (pinfunction "OUT_H1") (pintype "output"))
    )
    (net (code "22") (name "D01POWEROK") (class "Default")
      (node (ref "B01") (pin "V2") (pinfunction "P$2_V2") (pintype "bidirectional"))
      (node (ref "B02") (pin "V2") (pinfunction "P$2_V2") (pintype "bidirectional"))
      (node (ref "B03") (pin "V2") (pinfunction "P$2_V2") (pintype "bidirectional"))
      (node (ref "B04") (pin "V2") (pinfunction "P$2_V2") (pintype "bidirectional"))
      (node (ref "B05") (pin "V2") (pinfunction "P$2_V2") (pintype "bidirectional"))
      (node (ref "B06") (pin "V2") (pinfunction "P$2_V2") (pintype "bidirectional"))
      (node (ref "B07") (pin "V2") (pinfunction "P$2_V2") (pintype "bidirectional"))
      (node (ref "B08") (pin "V2") (pinfunction "P$2_V2") (pintype "bidirectional"))
      (node (ref "B09") (pin "V2") (pinfunction "P$2_V2") (pintype "bidirectional"))
      (node (ref "B10") (pin "V2") (pinfunction "P$2_V2") (pintype "bidirectional"))
      (node (ref "B11") (pin "V2") (pinfunction "P$2_V2") (pintype "bidirectional"))
      (node (ref "B12") (pin "V2") (pinfunction "P$2_V2") (pintype "bidirectional"))
      (node (ref "B13") (pin "V2") (pinfunction "P$2_V2") (pintype "bidirectional"))
      (node (ref "B14") (pin "V2") (pinfunction "P$2_V2") (pintype "bidirectional"))
      (node (ref "D18") (pin "A1") (pinfunction "IN_A1") (pintype "input"))
    )
    (net (code "23") (name "D01READH") (class "Default")
      (node (ref "B16") (pin "E2") (pinfunction "IN2_E2") (pintype "input"))
      (node (ref "B16") (pin "F2") (pinfunction "IN3_F2") (pintype "input"))
      (node (ref "B16") (pin "L1") (pinfunction "IN2_L1") (pintype "input"))
      (node (ref "B16") (pin "M1") (pinfunction "IN3_M1") (pintype "input"))
      (node (ref "B16") (pin "R1") (pinfunction "IN2_R1") (pintype "input"))
      (node (ref "B16") (pin "S1") (pinfunction "IN3_S1") (pintype "input"))
      (node (ref "C17") (pin "E1") (pinfunction "1_E1") (pintype "output"))
    )
    (net (code "24") (name "D01READL") (class "Default")
      (node (ref "A01") (pin "K2") (pinfunction "P$2_K2") (pintype "bidirectional"))
      (node (ref "A02") (pin "K2") (pinfunction "P$2_K2") (pintype "bidirectional"))
      (node (ref "A03") (pin "K2") (pinfunction "P$2_K2") (pintype "bidirectional"))
      (node (ref "A04") (pin "K2") (pinfunction "P$2_K2") (pintype "bidirectional"))
      (node (ref "A05") (pin "K2") (pinfunction "P$2_K2") (pintype "bidirectional"))
      (node (ref "A06") (pin "K2") (pinfunction "P$2_K2") (pintype "bidirectional"))
      (node (ref "A07") (pin "K2") (pinfunction "P$2_K2") (pintype "bidirectional"))
      (node (ref "A08") (pin "K2") (pinfunction "P$2_K2") (pintype "bidirectional"))
      (node (ref "A09") (pin "K2") (pinfunction "P$2_K2") (pintype "bidirectional"))
      (node (ref "A10") (pin "K2") (pinfunction "P$2_K2") (pintype "bidirectional"))
      (node (ref "A11") (pin "K2") (pinfunction "P$2_K2") (pintype "bidirectional"))
      (node (ref "A12") (pin "K2") (pinfunction "P$2_K2") (pintype "bidirectional"))
      (node (ref "A13") (pin "K2") (pinfunction "P$2_K2") (pintype "bidirectional"))
      (node (ref "A14") (pin "K2") (pinfunction "P$2_K2") (pintype "bidirectional"))
      (node (ref "B16") (pin "P2") (pinfunction "IN2_P2") (pintype "input"))
      (node (ref "B16") (pin "R2") (pinfunction "IN3_R2") (pintype "input"))
      (node (ref "C17") (pin "F1") (pinfunction "0_F1") (pintype "output"))
    )
    (net (code "25") (name "D01RETURN") (class "Default")
      (node (ref "A01") (pin "R2") (pinfunction "P$2_R2") (pintype "bidirectional"))
      (node (ref "A02") (pin "R2") (pinfunction "P$2_R2") (pintype "bidirectional"))
      (node (ref "A03") (pin "R2") (pinfunction "P$2_R2") (pintype "bidirectional"))
      (node (ref "A04") (pin "R2") (pinfunction "P$2_R2") (pintype "bidirectional"))
      (node (ref "A05") (pin "R2") (pinfunction "P$2_R2") (pintype "bidirectional"))
      (node (ref "A06") (pin "R2") (pinfunction "P$2_R2") (pintype "bidirectional"))
      (node (ref "A07") (pin "R2") (pinfunction "P$2_R2") (pintype "bidirectional"))
      (node (ref "A08") (pin "R2") (pinfunction "P$2_R2") (pintype "bidirectional"))
      (node (ref "A09") (pin "R2") (pinfunction "P$2_R2") (pintype "bidirectional"))
      (node (ref "A10") (pin "R2") (pinfunction "P$2_R2") (pintype "bidirectional"))
      (node (ref "A11") (pin "R2") (pinfunction "P$2_R2") (pintype "bidirectional"))
      (node (ref "A12") (pin "R2") (pinfunction "P$2_R2") (pintype "bidirectional"))
      (node (ref "A13") (pin "R2") (pinfunction "P$2_R2") (pintype "bidirectional"))
      (node (ref "A14") (pin "R2") (pinfunction "P$2_R2") (pintype "bidirectional"))
      (node (ref "A15") (pin "E1") (pinfunction "OUT_E1") (pintype "output"))
    )
    (net (code "26") (name "D01SELECTH") (class "Default")
      (node (ref "C16") (pin "K2") (pinfunction "IN1_K2") (pintype "input"))
      (node (ref "D17") (pin "E1") (pinfunction "1_E1") (pintype "output"))
    )
    (net (code "27") (name "D01SELECTL") (class "Default")
      (node (ref "B18") (pin "T2") (pinfunction "C_T2") (pintype "input"))
      (node (ref "D17") (pin "F1") (pinfunction "0_F1") (pintype "output"))
    )
    (net (code "28") (name "D01SELH") (class "Default")
      (node (ref "D17") (pin "C1") (pinfunction "D_C1") (pintype "input"))
      (node (ref "D18") (pin "S1") (pinfunction "OUT_S1") (pintype "output"))
    )
    (net (code "29") (name "D01SELL") (class "Default")
      (node (ref "B17") (pin "V2") (pinfunction "OUT_V2") (pintype "output"))
      (node (ref "D18") (pin "R1") (pinfunction "IN_R1") (pintype "input"))
    )
    (net (code "30") (name "D01SOURCE") (class "Default")
      (node (ref "A01") (pin "L2") (pinfunction "P$2_L2") (pintype "bidirectional"))
      (node (ref "A02") (pin "L2") (pinfunction "P$2_L2") (pintype "bidirectional"))
      (node (ref "A03") (pin "L2") (pinfunction "P$2_L2") (pintype "bidirectional"))
      (node (ref "A04") (pin "L2") (pinfunction "P$2_L2") (pintype "bidirectional"))
      (node (ref "A05") (pin "L2") (pinfunction "P$2_L2") (pintype "bidirectional"))
      (node (ref "A06") (pin "L2") (pinfunction "P$2_L2") (pintype "bidirectional"))
      (node (ref "A07") (pin "L2") (pinfunction "P$2_L2") (pintype "bidirectional"))
      (node (ref "A08") (pin "L2") (pinfunction "P$2_L2") (pintype "bidirectional"))
      (node (ref "A09") (pin "L2") (pinfunction "P$2_L2") (pintype "bidirectional"))
      (node (ref "A10") (pin "L2") (pinfunction "P$2_L2") (pintype "bidirectional"))
      (node (ref "A11") (pin "L2") (pinfunction "P$2_L2") (pintype "bidirectional"))
      (node (ref "A12") (pin "L2") (pinfunction "P$2_L2") (pintype "bidirectional"))
      (node (ref "A13") (pin "L2") (pinfunction "P$2_L2") (pintype "bidirectional"))
      (node (ref "A14") (pin "L2") (pinfunction "P$2_L2") (pintype "bidirectional"))
      (node (ref "A15") (pin "L1") (pinfunction "OUT_L1") (pintype "output"))
    )
    (net (code "31") (name "D01STROBE") (class "Default")
      (node (ref "A01") (pin "M2") (pinfunction "P$2_M2") (pintype "bidirectional"))
      (node (ref "A02") (pin "M2") (pinfunction "P$2_M2") (pintype "bidirectional"))
      (node (ref "A03") (pin "M2") (pinfunction "P$2_M2") (pintype "bidirectional"))
      (node (ref "A04") (pin "M2") (pinfunction "P$2_M2") (pintype "bidirectional"))
      (node (ref "A05") (pin "M2") (pinfunction "P$2_M2") (pintype "bidirectional"))
      (node (ref "A06") (pin "M2") (pinfunction "P$2_M2") (pintype "bidirectional"))
      (node (ref "A07") (pin "M2") (pinfunction "P$2_M2") (pintype "bidirectional"))
      (node (ref "A08") (pin "M2") (pinfunction "P$2_M2") (pintype "bidirectional"))
      (node (ref "A09") (pin "M2") (pinfunction "P$2_M2") (pintype "bidirectional"))
      (node (ref "A10") (pin "M2") (pinfunction "P$2_M2") (pintype "bidirectional"))
      (node (ref "A11") (pin "M2") (pinfunction "P$2_M2") (pintype "bidirectional"))
      (node (ref "A12") (pin "M2") (pinfunction "P$2_M2") (pintype "bidirectional"))
      (node (ref "A13") (pin "M2") (pinfunction "P$2_M2") (pintype "bidirectional"))
      (node (ref "A14") (pin "M2") (pinfunction "P$2_M2") (pintype "bidirectional"))
      (node (ref "A15") (pin "P2") (pinfunction "OUT_P2") (pintype "output"))
    )
    (net (code "32") (name "D01STROBEL") (class "Default")
      (node (ref "A16") (pin "P2") (pinfunction "P$2_P2") (pintype "bidirectional"))
      (node (ref "B17") (pin "U1") (pinfunction "P$1_U1") (pintype "passive"))
      (node (ref "B18") (pin "U2") (pinfunction "D_U2") (pintype "open_collector"))
    )
    (net (code "33") (name "D01WRITE") (class "Default")
      (node (ref "A01") (pin "S2") (pinfunction "P$2_S2") (pintype "bidirectional"))
      (node (ref "A02") (pin "S2") (pinfunction "P$2_S2") (pintype "bidirectional"))
      (node (ref "A03") (pin "S2") (pinfunction "P$2_S2") (pintype "bidirectional"))
      (node (ref "A04") (pin "S2") (pinfunction "P$2_S2") (pintype "bidirectional"))
      (node (ref "A05") (pin "S2") (pinfunction "P$2_S2") (pintype "bidirectional"))
      (node (ref "A06") (pin "S2") (pinfunction "P$2_S2") (pintype "bidirectional"))
      (node (ref "A07") (pin "S2") (pinfunction "P$2_S2") (pintype "bidirectional"))
      (node (ref "A08") (pin "S2") (pinfunction "P$2_S2") (pintype "bidirectional"))
      (node (ref "A09") (pin "S2") (pinfunction "P$2_S2") (pintype "bidirectional"))
      (node (ref "A10") (pin "S2") (pinfunction "P$2_S2") (pintype "bidirectional"))
      (node (ref "A11") (pin "S2") (pinfunction "P$2_S2") (pintype "bidirectional"))
      (node (ref "A12") (pin "S2") (pinfunction "P$2_S2") (pintype "bidirectional"))
      (node (ref "A13") (pin "S2") (pinfunction "P$2_S2") (pintype "bidirectional"))
      (node (ref "A14") (pin "S2") (pinfunction "P$2_S2") (pintype "bidirectional"))
      (node (ref "A15") (pin "J2") (pinfunction "OUT_J2") (pintype "output"))
    )
    (net (code "34") (name "D01WRITEH") (class "Default")
      (node (ref "B16") (pin "K2") (pinfunction "IN2_K2") (pintype "input"))
      (node (ref "B16") (pin "L2") (pinfunction "IN3_L2") (pintype "input"))
      (node (ref "C16") (pin "D2") (pinfunction "IN1_D2") (pintype "input"))
      (node (ref "C17") (pin "S1") (pinfunction "1_S1") (pintype "output"))
    )
    (net (code "35") (name "D02MEM0") (class "Default")
      (node (ref "A17N") (pin "E2") (pinfunction "P$2_E2") (pintype "bidirectional"))
      (node (ref "B20") (pin "D1") (pinfunction "D_D1") (pintype "open_collector"))
    )
    (net (code "36") (name "D02MEM1") (class "Default")
      (node (ref "A17N") (pin "H2") (pinfunction "P$2_H2") (pintype "bidirectional"))
      (node (ref "B20") (pin "E1") (pinfunction "E_E1") (pintype "open_collector"))
    )
    (net (code "37") (name "D02MEM2") (class "Default")
      (node (ref "A17N") (pin "K2") (pinfunction "P$2_K2") (pintype "bidirectional"))
      (node (ref "B20") (pin "K1") (pinfunction "D_K1") (pintype "open_collector"))
    )
    (net (code "38") (name "D02MEM3") (class "Default")
      (node (ref "A17N") (pin "M2") (pinfunction "P$2_M2") (pintype "bidirectional"))
      (node (ref "B20") (pin "L1") (pinfunction "E_L1") (pintype "open_collector"))
    )
    (net (code "39") (name "D02MEM4") (class "Default")
      (node (ref "A17N") (pin "P2") (pinfunction "P$2_P2") (pintype "bidirectional"))
      (node (ref "B20") (pin "R1") (pinfunction "D_R1") (pintype "open_collector"))
    )
    (net (code "40") (name "D02MEM5") (class "Default")
      (node (ref "A17N") (pin "S2") (pinfunction "P$2_S2") (pintype "bidirectional"))
      (node (ref "B20") (pin "S1") (pinfunction "E_S1") (pintype "open_collector"))
    )
    (net (code "41") (name "D02MEM6") (class "Default")
      (node (ref "A17N") (pin "T2") (pinfunction "P$2_T2") (pintype "bidirectional"))
      (node (ref "B20") (pin "H2") (pinfunction "D_H2") (pintype "open_collector"))
    )
    (net (code "42") (name "D02MEM7") (class "Default")
      (node (ref "A17N") (pin "V2") (pinfunction "P$2_V2") (pintype "bidirectional"))
      (node (ref "B20") (pin "J2") (pinfunction "E_J2") (pintype "open_collector"))
    )
    (net (code "43") (name "D02MEM8") (class "Default")
      (node (ref "A16") (pin "D2") (pinfunction "P$2_D2") (pintype "bidirectional"))
      (node (ref "B20") (pin "N2") (pinfunction "D_N2") (pintype "open_collector"))
    )
    (net (code "44") (name "D02MEM9") (class "Default")
      (node (ref "A16") (pin "E2") (pinfunction "P$2_E2") (pintype "bidirectional"))
      (node (ref "B20") (pin "P2") (pinfunction "E_P2") (pintype "open_collector"))
    )
    (net (code "45") (name "D02MEM10") (class "Default")
      (node (ref "A16") (pin "H2") (pinfunction "P$2_H2") (pintype "bidirectional"))
      (node (ref "B20") (pin "U2") (pinfunction "D_U2") (pintype "open_collector"))
    )
    (net (code "46") (name "D02MEM11") (class "Default")
      (node (ref "A16") (pin "K2") (pinfunction "P$2_K2") (pintype "bidirectional"))
      (node (ref "B20") (pin "V2") (pinfunction "E_V2") (pintype "open_collector"))
    )
    (net (code "47") (name "D03BEMA0L") (class "Default")
      (node (ref "A01") (pin "D2") (pinfunction "P$2_D2") (pintype "bidirectional"))
      (node (ref "A02") (pin "D2") (pinfunction "P$2_D2") (pintype "bidirectional"))
      (node (ref "A03") (pin "D2") (pinfunction "P$2_D2") (pintype "bidirectional"))
      (node (ref "A04") (pin "D2") (pinfunction "P$2_D2") (pintype "bidirectional"))
      (node (ref "A05") (pin "D2") (pinfunction "P$2_D2") (pintype "bidirectional"))
      (node (ref "A06") (pin "D2") (pinfunction "P$2_D2") (pintype "bidirectional"))
      (node (ref "A07") (pin "D2") (pinfunction "P$2_D2") (pintype "bidirectional"))
      (node (ref "A08") (pin "D2") (pinfunction "P$2_D2") (pintype "bidirectional"))
      (node (ref "A09") (pin "D2") (pinfunction "P$2_D2") (pintype "bidirectional"))
      (node (ref "A10") (pin "D2") (pinfunction "P$2_D2") (pintype "bidirectional"))
      (node (ref "A11") (pin "D2") (pinfunction "P$2_D2") (pintype "bidirectional"))
      (node (ref "A12") (pin "D2") (pinfunction "P$2_D2") (pintype "bidirectional"))
      (node (ref "A13") (pin "D2") (pinfunction "P$2_D2") (pintype "bidirectional"))
      (node (ref "A14") (pin "D2") (pinfunction "P$2_D2") (pintype "bidirectional"))
      (node (ref "D17") (pin "U1") (pinfunction "0_U1") (pintype "output"))
    )
    (net (code "48") (name "D03BEMA1L") (class "Default")
      (node (ref "A01") (pin "E2") (pinfunction "P$2_E2") (pintype "bidirectional"))
      (node (ref "A02") (pin "E2") (pinfunction "P$2_E2") (pintype "bidirectional"))
      (node (ref "A03") (pin "E2") (pinfunction "P$2_E2") (pintype "bidirectional"))
      (node (ref "A04") (pin "E2") (pinfunction "P$2_E2") (pintype "bidirectional"))
      (node (ref "A05") (pin "E2") (pinfunction "P$2_E2") (pintype "bidirectional"))
      (node (ref "A06") (pin "E2") (pinfunction "P$2_E2") (pintype "bidirectional"))
      (node (ref "A07") (pin "E2") (pinfunction "P$2_E2") (pintype "bidirectional"))
      (node (ref "A08") (pin "E2") (pinfunction "P$2_E2") (pintype "bidirectional"))
      (node (ref "A09") (pin "E2") (pinfunction "P$2_E2") (pintype "bidirectional"))
      (node (ref "A10") (pin "E2") (pinfunction "P$2_E2") (pintype "bidirectional"))
      (node (ref "A11") (pin "E2") (pinfunction "P$2_E2") (pintype "bidirectional"))
      (node (ref "A12") (pin "E2") (pinfunction "P$2_E2") (pintype "bidirectional"))
      (node (ref "A13") (pin "E2") (pinfunction "P$2_E2") (pintype "bidirectional"))
      (node (ref "A14") (pin "E2") (pinfunction "P$2_E2") (pintype "bidirectional"))
      (node (ref "D17") (pin "R2") (pinfunction "0_R2") (pintype "output"))
    )
    (net (code "49") (name "D03BEMA2L") (class "Default")
      (node (ref "A01") (pin "H2") (pinfunction "P$2_H2") (pintype "bidirectional"))
      (node (ref "A02") (pin "H2") (pinfunction "P$2_H2") (pintype "bidirectional"))
      (node (ref "A03") (pin "H2") (pinfunction "P$2_H2") (pintype "bidirectional"))
      (node (ref "A04") (pin "H2") (pinfunction "P$2_H2") (pintype "bidirectional"))
      (node (ref "A05") (pin "H2") (pinfunction "P$2_H2") (pintype "bidirectional"))
      (node (ref "A06") (pin "H2") (pinfunction "P$2_H2") (pintype "bidirectional"))
      (node (ref "A07") (pin "H2") (pinfunction "P$2_H2") (pintype "bidirectional"))
      (node (ref "A08") (pin "H2") (pinfunction "P$2_H2") (pintype "bidirectional"))
      (node (ref "A09") (pin "H2") (pinfunction "P$2_H2") (pintype "bidirectional"))
      (node (ref "A10") (pin "H2") (pinfunction "P$2_H2") (pintype "bidirectional"))
      (node (ref "A11") (pin "H2") (pinfunction "P$2_H2") (pintype "bidirectional"))
      (node (ref "A12") (pin "H2") (pinfunction "P$2_H2") (pintype "bidirectional"))
      (node (ref "A13") (pin "H2") (pinfunction "P$2_H2") (pintype "bidirectional"))
      (node (ref "A14") (pin "H2") (pinfunction "P$2_H2") (pintype "bidirectional"))
      (node (ref "D17") (pin "V1") (pinfunction "0_V1") (pintype "output"))
    )
    (net (code "50") (name "D03BMA0") (class "Default")
      (node (ref "A20N") (pin "K2") (pinfunction "P$2_K2") (pintype "bidirectional"))
      (node (ref "B15") (pin "D2") (pinfunction "IN1_D2") (pintype "input"))
    )
    (net (code "51") (name "D03BMA1") (class "Default")
      (node (ref "A20N") (pin "M2") (pinfunction "P$2_M2") (pintype "bidirectional"))
      (node (ref "B15") (pin "K2") (pinfunction "IN1_K2") (pintype "input"))
    )
    (net (code "52") (name "D03BMA2") (class "Default")
      (node (ref "A20N") (pin "P2") (pinfunction "P$2_P2") (pintype "bidirectional"))
      (node (ref "B15") (pin "R2") (pinfunction "IN1_R2") (pintype "input"))
    )
    (net (code "53") (name "D03BMA3") (class "Default")
      (node (ref "A20N") (pin "S2") (pinfunction "P$2_S2") (pintype "bidirectional"))
      (node (ref "C15") (pin "A1") (pinfunction "IN1_A1") (pintype "input"))
    )
    (net (code "54") (name "D03BMA4") (class "Default")
      (node (ref "A20N") (pin "T2") (pinfunction "P$2_T2") (pintype "bidirectional"))
      (node (ref "C15") (pin "F1") (pinfunction "IN1_F1") (pintype "input"))
    )
    (net (code "55") (name "D03BMA5") (class "Default")
      (node (ref "A20N") (pin "V2") (pinfunction "P$2_V2") (pintype "bidirectional"))
      (node (ref "C15") (pin "M1") (pinfunction "IN1_M1") (pintype "input"))
    )
    (net (code "56") (name "D03BMA6") (class "Default")
      (node (ref "A19N") (pin "D2") (pinfunction "P$2_D2") (pintype "bidirectional"))
      (node (ref "C15") (pin "D2") (pinfunction "IN1_D2") (pintype "input"))
    )
    (net (code "57") (name "D03BMA7") (class "Default")
      (node (ref "A19N") (pin "E2") (pinfunction "P$2_E2") (pintype "bidirectional"))
      (node (ref "C15") (pin "K2") (pinfunction "IN1_K2") (pintype "input"))
    )
    (net (code "58") (name "D03BMA8") (class "Default")
      (node (ref "A19N") (pin "H2") (pinfunction "P$2_H2") (pintype "bidirectional"))
      (node (ref "C15") (pin "R2") (pinfunction "IN1_R2") (pintype "input"))
    )
    (net (code "59") (name "D03BMA9") (class "Default")
      (node (ref "A19N") (pin "K2") (pinfunction "P$2_K2") (pintype "bidirectional"))
      (node (ref "C16") (pin "A1") (pinfunction "IN1_A1") (pintype "input"))
    )
    (net (code "60") (name "D03BMA10") (class "Default")
      (node (ref "A19N") (pin "M2") (pinfunction "P$2_M2") (pintype "bidirectional"))
      (node (ref "C16") (pin "F1") (pinfunction "IN1_F1") (pintype "input"))
    )
    (net (code "61") (name "D03BMA11") (class "Default")
      (node (ref "A19N") (pin "P2") (pinfunction "P$2_P2") (pintype "bidirectional"))
      (node (ref "C16") (pin "M1") (pinfunction "IN1_M1") (pintype "input"))
    )
    (net (code "62") (name "D03BTP2") (class "Default")
      (node (ref "A16") (pin "V2") (pinfunction "P$2_V2") (pintype "bidirectional"))
      (node (ref "C17") (pin "B1") (pinfunction "C_B1") (pintype "input"))
      (node (ref "D18") (pin "D1") (pinfunction "IN_D1") (pintype "input"))
    )
    (net (code "63") (name "D03EA0") (class "Default")
      (node (ref "A18N") (pin "D2") (pinfunction "P$2_D2") (pintype "bidirectional"))
      (node (ref "B15") (pin "A1") (pinfunction "IN1_A1") (pintype "input"))
    )
    (net (code "64") (name "D03EA1") (class "Default")
      (node (ref "A18N") (pin "E2") (pinfunction "P$2_E2") (pintype "bidirectional"))
      (node (ref "B15") (pin "F1") (pinfunction "IN1_F1") (pintype "input"))
    )
    (net (code "65") (name "D03EA2") (class "Default")
      (node (ref "A18N") (pin "H2") (pinfunction "P$2_H2") (pintype "bidirectional"))
      (node (ref "B15") (pin "M1") (pinfunction "IN1_M1") (pintype "input"))
    )
    (net (code "66") (name "D03EMA0H") (class "Default")
      (node (ref "B17") (pin "D1") (pinfunction "IN1_D1") (pintype "input"))
      (node (ref "D17") (pin "P1") (pinfunction "D_P1") (pintype "input"))
      (node (ref "D18") (pin "F2") (pinfunction "OUT_F2") (pintype "output"))
      (node (ref "D19") (pin "H1") (pinfunction "L1_H1") (pintype "bidirectional"))
    )
    (net (code "67") (name "D03EMA0L") (class "Default")
      (node (ref "B15") (pin "E1") (pinfunction "OUT_E1") (pintype "output"))
      (node (ref "B17") (pin "A1") (pinfunction "IN1_A1") (pintype "input"))
      (node (ref "D18") (pin "C1") (pinfunction "IN_C1") (pintype "input"))
      (node (ref "D18") (pin "E2") (pinfunction "IN_E2") (pintype "input"))
      (node (ref "D19") (pin "J1") (pinfunction "L2_J1") (pintype "bidirectional"))
    )
    (net (code "68") (name "D03EMA1H") (class "Default")
      (node (ref "B17") (pin "E1") (pinfunction "IN2_E1") (pintype "input"))
      (node (ref "D17") (pin "M2") (pinfunction "D_M2") (pintype "input"))
      (node (ref "D18") (pin "K1") (pinfunction "OUT_K1") (pintype "output"))
      (node (ref "D19") (pin "E1") (pinfunction "L2_E1") (pintype "bidirectional"))
    )
    (net (code "69") (name "D03EMA1L") (class "Default")
      (node (ref "B15") (pin "L1") (pinfunction "OUT_L1") (pintype "output"))
      (node (ref "B17") (pin "B1") (pinfunction "IN2_B1") (pintype "input"))
      (node (ref "D18") (pin "J1") (pinfunction "IN_J1") (pintype "input"))
      (node (ref "D19") (pin "D1") (pinfunction "L1_D1") (pintype "bidirectional"))
    )
    (net (code "70") (name "D03EMA2H") (class "Default")
      (node (ref "D17") (pin "T2") (pinfunction "D_T2") (pintype "input"))
      (node (ref "D18") (pin "L2") (pinfunction "OUT_L2") (pintype "output"))
      (node (ref "D19") (pin "L1") (pinfunction "L1_L1") (pintype "bidirectional"))
    )
    (net (code "71") (name "D03EMA2L") (class "Default")
      (node (ref "B15") (pin "S1") (pinfunction "OUT_S1") (pintype "output"))
      (node (ref "D18") (pin "K2") (pinfunction "IN_K2") (pintype "input"))
      (node (ref "D19") (pin "M1") (pinfunction "L2_M1") (pintype "bidirectional"))
    )
    (net (code "72") (name "D03MA0L") (class "Default")
      (node (ref "A01") (pin "D1") (pinfunction "P$2_D1") (pintype "bidirectional"))
      (node (ref "A02") (pin "D1") (pinfunction "P$2_D1") (pintype "bidirectional"))
      (node (ref "A03") (pin "D1") (pinfunction "P$2_D1") (pintype "bidirectional"))
      (node (ref "A04") (pin "D1") (pinfunction "P$2_D1") (pintype "bidirectional"))
      (node (ref "A05") (pin "D1") (pinfunction "P$2_D1") (pintype "bidirectional"))
      (node (ref "A06") (pin "D1") (pinfunction "P$2_D1") (pintype "bidirectional"))
      (node (ref "A07") (pin "D1") (pinfunction "P$2_D1") (pintype "bidirectional"))
      (node (ref "A08") (pin "D1") (pinfunction "P$2_D1") (pintype "bidirectional"))
      (node (ref "A09") (pin "D1") (pinfunction "P$2_D1") (pintype "bidirectional"))
      (node (ref "A10") (pin "D1") (pinfunction "P$2_D1") (pintype "bidirectional"))
      (node (ref "A11") (pin "D1") (pinfunction "P$2_D1") (pintype "bidirectional"))
      (node (ref "A12") (pin "D1") (pinfunction "P$2_D1") (pintype "bidirectional"))
      (node (ref "A13") (pin "D1") (pinfunction "P$2_D1") (pintype "bidirectional"))
      (node (ref "A14") (pin "D1") (pinfunction "P$2_D1") (pintype "bidirectional"))
      (node (ref "B15") (pin "J2") (pinfunction "OUT_J2") (pintype "output"))
    )
    (net (code "73") (name "D03MA1L") (class "Default")
      (node (ref "A01") (pin "E1") (pinfunction "P$2_E1") (pintype "bidirectional"))
      (node (ref "A02") (pin "E1") (pinfunction "P$2_E1") (pintype "bidirectional"))
      (node (ref "A03") (pin "E1") (pinfunction "P$2_E1") (pintype "bidirectional"))
      (node (ref "A04") (pin "E1") (pinfunction "P$2_E1") (pintype "bidirectional"))
      (node (ref "A05") (pin "E1") (pinfunction "P$2_E1") (pintype "bidirectional"))
      (node (ref "A06") (pin "E1") (pinfunction "P$2_E1") (pintype "bidirectional"))
      (node (ref "A07") (pin "E1") (pinfunction "P$2_E1") (pintype "bidirectional"))
      (node (ref "A08") (pin "E1") (pinfunction "P$2_E1") (pintype "bidirectional"))
      (node (ref "A09") (pin "E1") (pinfunction "P$2_E1") (pintype "bidirectional"))
      (node (ref "A10") (pin "E1") (pinfunction "P$2_E1") (pintype "bidirectional"))
      (node (ref "A11") (pin "E1") (pinfunction "P$2_E1") (pintype "bidirectional"))
      (node (ref "A12") (pin "E1") (pinfunction "P$2_E1") (pintype "bidirectional"))
      (node (ref "A13") (pin "E1") (pinfunction "P$2_E1") (pintype "bidirectional"))
      (node (ref "A14") (pin "E1") (pinfunction "P$2_E1") (pintype "bidirectional"))
      (node (ref "B15") (pin "P2") (pinfunction "OUT_P2") (pintype "output"))
    )
    (net (code "74") (name "D03MA2L") (class "Default")
      (node (ref "A01") (pin "H1") (pinfunction "P$2_H1") (pintype "bidirectional"))
      (node (ref "A02") (pin "H1") (pinfunction "P$2_H1") (pintype "bidirectional"))
      (node (ref "A03") (pin "H1") (pinfunction "P$2_H1") (pintype "bidirectional"))
      (node (ref "A04") (pin "H1") (pinfunction "P$2_H1") (pintype "bidirectional"))
      (node (ref "A05") (pin "H1") (pinfunction "P$2_H1") (pintype "bidirectional"))
      (node (ref "A06") (pin "H1") (pinfunction "P$2_H1") (pintype "bidirectional"))
      (node (ref "A07") (pin "H1") (pinfunction "P$2_H1") (pintype "bidirectional"))
      (node (ref "A08") (pin "H1") (pinfunction "P$2_H1") (pintype "bidirectional"))
      (node (ref "A09") (pin "H1") (pinfunction "P$2_H1") (pintype "bidirectional"))
      (node (ref "A10") (pin "H1") (pinfunction "P$2_H1") (pintype "bidirectional"))
      (node (ref "A11") (pin "H1") (pinfunction "P$2_H1") (pintype "bidirectional"))
      (node (ref "A12") (pin "H1") (pinfunction "P$2_H1") (pintype "bidirectional"))
      (node (ref "A13") (pin "H1") (pinfunction "P$2_H1") (pintype "bidirectional"))
      (node (ref "A14") (pin "H1") (pinfunction "P$2_H1") (pintype "bidirectional"))
      (node (ref "B15") (pin "V2") (pinfunction "OUT_V2") (pintype "output"))
    )
    (net (code "75") (name "D03MA3L") (class "Default")
      (node (ref "A01") (pin "J1") (pinfunction "P$2_J1") (pintype "bidirectional"))
      (node (ref "A02") (pin "J1") (pinfunction "P$2_J1") (pintype "bidirectional"))
      (node (ref "A03") (pin "J1") (pinfunction "P$2_J1") (pintype "bidirectional"))
      (node (ref "A04") (pin "J1") (pinfunction "P$2_J1") (pintype "bidirectional"))
      (node (ref "A05") (pin "J1") (pinfunction "P$2_J1") (pintype "bidirectional"))
      (node (ref "A06") (pin "J1") (pinfunction "P$2_J1") (pintype "bidirectional"))
      (node (ref "A07") (pin "J1") (pinfunction "P$2_J1") (pintype "bidirectional"))
      (node (ref "A08") (pin "J1") (pinfunction "P$2_J1") (pintype "bidirectional"))
      (node (ref "A09") (pin "J1") (pinfunction "P$2_J1") (pintype "bidirectional"))
      (node (ref "A10") (pin "J1") (pinfunction "P$2_J1") (pintype "bidirectional"))
      (node (ref "A11") (pin "J1") (pinfunction "P$2_J1") (pintype "bidirectional"))
      (node (ref "A12") (pin "J1") (pinfunction "P$2_J1") (pintype "bidirectional"))
      (node (ref "A13") (pin "J1") (pinfunction "P$2_J1") (pintype "bidirectional"))
      (node (ref "A14") (pin "J1") (pinfunction "P$2_J1") (pintype "bidirectional"))
      (node (ref "C15") (pin "E1") (pinfunction "OUT_E1") (pintype "output"))
    )
    (net (code "76") (name "D03MA4L") (class "Default")
      (node (ref "B01") (pin "D1") (pinfunction "P$2_D1") (pintype "bidirectional"))
      (node (ref "B02") (pin "D1") (pinfunction "P$2_D1") (pintype "bidirectional"))
      (node (ref "B03") (pin "D1") (pinfunction "P$2_D1") (pintype "bidirectional"))
      (node (ref "B04") (pin "D1") (pinfunction "P$2_D1") (pintype "bidirectional"))
      (node (ref "B05") (pin "D1") (pinfunction "P$2_D1") (pintype "bidirectional"))
      (node (ref "B06") (pin "D1") (pinfunction "P$2_D1") (pintype "bidirectional"))
      (node (ref "B07") (pin "D1") (pinfunction "P$2_D1") (pintype "bidirectional"))
      (node (ref "B08") (pin "D1") (pinfunction "P$2_D1") (pintype "bidirectional"))
      (node (ref "B09") (pin "D1") (pinfunction "P$2_D1") (pintype "bidirectional"))
      (node (ref "B10") (pin "D1") (pinfunction "P$2_D1") (pintype "bidirectional"))
      (node (ref "B11") (pin "D1") (pinfunction "P$2_D1") (pintype "bidirectional"))
      (node (ref "B12") (pin "D1") (pinfunction "P$2_D1") (pintype "bidirectional"))
      (node (ref "B13") (pin "D1") (pinfunction "P$2_D1") (pintype "bidirectional"))
      (node (ref "B14") (pin "D1") (pinfunction "P$2_D1") (pintype "bidirectional"))
      (node (ref "C15") (pin "L1") (pinfunction "OUT_L1") (pintype "output"))
    )
    (net (code "77") (name "D03MA5L") (class "Default")
      (node (ref "B01") (pin "E1") (pinfunction "P$2_E1") (pintype "bidirectional"))
      (node (ref "B02") (pin "E1") (pinfunction "P$2_E1") (pintype "bidirectional"))
      (node (ref "B03") (pin "E1") (pinfunction "P$2_E1") (pintype "bidirectional"))
      (node (ref "B04") (pin "E1") (pinfunction "P$2_E1") (pintype "bidirectional"))
      (node (ref "B05") (pin "E1") (pinfunction "P$2_E1") (pintype "bidirectional"))
      (node (ref "B06") (pin "E1") (pinfunction "P$2_E1") (pintype "bidirectional"))
      (node (ref "B07") (pin "E1") (pinfunction "P$2_E1") (pintype "bidirectional"))
      (node (ref "B08") (pin "E1") (pinfunction "P$2_E1") (pintype "bidirectional"))
      (node (ref "B09") (pin "E1") (pinfunction "P$2_E1") (pintype "bidirectional"))
      (node (ref "B10") (pin "E1") (pinfunction "P$2_E1") (pintype "bidirectional"))
      (node (ref "B11") (pin "E1") (pinfunction "P$2_E1") (pintype "bidirectional"))
      (node (ref "B12") (pin "E1") (pinfunction "P$2_E1") (pintype "bidirectional"))
      (node (ref "B13") (pin "E1") (pinfunction "P$2_E1") (pintype "bidirectional"))
      (node (ref "B14") (pin "E1") (pinfunction "P$2_E1") (pintype "bidirectional"))
      (node (ref "C15") (pin "S1") (pinfunction "OUT_S1") (pintype "output"))
    )
    (net (code "78") (name "D03MA6L") (class "Default")
      (node (ref "B01") (pin "H1") (pinfunction "P$2_H1") (pintype "bidirectional"))
      (node (ref "B02") (pin "H1") (pinfunction "P$2_H1") (pintype "bidirectional"))
      (node (ref "B03") (pin "H1") (pinfunction "P$2_H1") (pintype "bidirectional"))
      (node (ref "B04") (pin "H1") (pinfunction "P$2_H1") (pintype "bidirectional"))
      (node (ref "B05") (pin "H1") (pinfunction "P$2_H1") (pintype "bidirectional"))
      (node (ref "B06") (pin "H1") (pinfunction "P$2_H1") (pintype "bidirectional"))
      (node (ref "B07") (pin "H1") (pinfunction "P$2_H1") (pintype "bidirectional"))
      (node (ref "B08") (pin "H1") (pinfunction "P$2_H1") (pintype "bidirectional"))
      (node (ref "B09") (pin "H1") (pinfunction "P$2_H1") (pintype "bidirectional"))
      (node (ref "B10") (pin "H1") (pinfunction "P$2_H1") (pintype "bidirectional"))
      (node (ref "B11") (pin "H1") (pinfunction "P$2_H1") (pintype "bidirectional"))
      (node (ref "B12") (pin "H1") (pinfunction "P$2_H1") (pintype "bidirectional"))
      (node (ref "B13") (pin "H1") (pinfunction "P$2_H1") (pintype "bidirectional"))
      (node (ref "B14") (pin "H1") (pinfunction "P$2_H1") (pintype "bidirectional"))
      (node (ref "C15") (pin "J2") (pinfunction "OUT_J2") (pintype "output"))
    )
    (net (code "79") (name "D03MA7L") (class "Default")
      (node (ref "B01") (pin "J1") (pinfunction "P$2_J1") (pintype "bidirectional"))
      (node (ref "B02") (pin "J1") (pinfunction "P$2_J1") (pintype "bidirectional"))
      (node (ref "B03") (pin "J1") (pinfunction "P$2_J1") (pintype "bidirectional"))
      (node (ref "B04") (pin "J1") (pinfunction "P$2_J1") (pintype "bidirectional"))
      (node (ref "B05") (pin "J1") (pinfunction "P$2_J1") (pintype "bidirectional"))
      (node (ref "B06") (pin "J1") (pinfunction "P$2_J1") (pintype "bidirectional"))
      (node (ref "B07") (pin "J1") (pinfunction "P$2_J1") (pintype "bidirectional"))
      (node (ref "B08") (pin "J1") (pinfunction "P$2_J1") (pintype "bidirectional"))
      (node (ref "B09") (pin "J1") (pinfunction "P$2_J1") (pintype "bidirectional"))
      (node (ref "B10") (pin "J1") (pinfunction "P$2_J1") (pintype "bidirectional"))
      (node (ref "B11") (pin "J1") (pinfunction "P$2_J1") (pintype "bidirectional"))
      (node (ref "B12") (pin "J1") (pinfunction "P$2_J1") (pintype "bidirectional"))
      (node (ref "B13") (pin "J1") (pinfunction "P$2_J1") (pintype "bidirectional"))
      (node (ref "B14") (pin "J1") (pinfunction "P$2_J1") (pintype "bidirectional"))
      (node (ref "C15") (pin "P2") (pinfunction "OUT_P2") (pintype "output"))
    )
    (net (code "80") (name "D03MA8L") (class "Default")
      (node (ref "C15") (pin "V2") (pinfunction "OUT_V2") (pintype "output"))
      (node (ref "D01") (pin "D1") (pinfunction "P$2_D1") (pintype "bidirectional"))
      (node (ref "D02") (pin "D1") (pinfunction "P$2_D1") (pintype "bidirectional"))
      (node (ref "D03") (pin "D1") (pinfunction "P$2_D1") (pintype "bidirectional"))
      (node (ref "D04") (pin "D1") (pinfunction "P$2_D1") (pintype "bidirectional"))
      (node (ref "D05") (pin "D1") (pinfunction "P$2_D1") (pintype "bidirectional"))
      (node (ref "D06") (pin "D1") (pinfunction "P$2_D1") (pintype "bidirectional"))
      (node (ref "D07") (pin "D1") (pinfunction "P$2_D1") (pintype "bidirectional"))
      (node (ref "D08") (pin "D1") (pinfunction "P$2_D1") (pintype "bidirectional"))
      (node (ref "D09") (pin "D1") (pinfunction "P$2_D1") (pintype "bidirectional"))
      (node (ref "D10") (pin "D1") (pinfunction "P$2_D1") (pintype "bidirectional"))
      (node (ref "D11") (pin "D1") (pinfunction "P$2_D1") (pintype "bidirectional"))
      (node (ref "D12") (pin "D1") (pinfunction "P$2_D1") (pintype "bidirectional"))
      (node (ref "D13") (pin "D1") (pinfunction "P$2_D1") (pintype "bidirectional"))
      (node (ref "D14") (pin "D1") (pinfunction "P$2_D1") (pintype "bidirectional"))
    )
    (net (code "81") (name "D03MA9L") (class "Default")
      (node (ref "C16") (pin "E1") (pinfunction "OUT_E1") (pintype "output"))
      (node (ref "D01") (pin "E1") (pinfunction "P$2_E1") (pintype "bidirectional"))
      (node (ref "D02") (pin "E1") (pinfunction "P$2_E1") (pintype "bidirectional"))
      (node (ref "D03") (pin "E1") (pinfunction "P$2_E1") (pintype "bidirectional"))
      (node (ref "D04") (pin "E1") (pinfunction "P$2_E1") (pintype "bidirectional"))
      (node (ref "D05") (pin "E1") (pinfunction "P$2_E1") (pintype "bidirectional"))
      (node (ref "D06") (pin "E1") (pinfunction "P$2_E1") (pintype "bidirectional"))
      (node (ref "D07") (pin "E1") (pinfunction "P$2_E1") (pintype "bidirectional"))
      (node (ref "D08") (pin "E1") (pinfunction "P$2_E1") (pintype "bidirectional"))
      (node (ref "D09") (pin "E1") (pinfunction "P$2_E1") (pintype "bidirectional"))
      (node (ref "D10") (pin "E1") (pinfunction "P$2_E1") (pintype "bidirectional"))
      (node (ref "D11") (pin "E1") (pinfunction "P$2_E1") (pintype "bidirectional"))
      (node (ref "D12") (pin "E1") (pinfunction "P$2_E1") (pintype "bidirectional"))
      (node (ref "D13") (pin "E1") (pinfunction "P$2_E1") (pintype "bidirectional"))
      (node (ref "D14") (pin "E1") (pinfunction "P$2_E1") (pintype "bidirectional"))
    )
    (net (code "82") (name "D03MA10L") (class "Default")
      (node (ref "C16") (pin "L1") (pinfunction "OUT_L1") (pintype "output"))
      (node (ref "D01") (pin "H1") (pinfunction "P$2_H1") (pintype "bidirectional"))
      (node (ref "D02") (pin "H1") (pinfunction "P$2_H1") (pintype "bidirectional"))
      (node (ref "D03") (pin "H1") (pinfunction "P$2_H1") (pintype "bidirectional"))
      (node (ref "D04") (pin "H1") (pinfunction "P$2_H1") (pintype "bidirectional"))
      (node (ref "D05") (pin "H1") (pinfunction "P$2_H1") (pintype "bidirectional"))
      (node (ref "D06") (pin "H1") (pinfunction "P$2_H1") (pintype "bidirectional"))
      (node (ref "D07") (pin "H1") (pinfunction "P$2_H1") (pintype "bidirectional"))
      (node (ref "D08") (pin "H1") (pinfunction "P$2_H1") (pintype "bidirectional"))
      (node (ref "D09") (pin "H1") (pinfunction "P$2_H1") (pintype "bidirectional"))
      (node (ref "D10") (pin "H1") (pinfunction "P$2_H1") (pintype "bidirectional"))
      (node (ref "D11") (pin "H1") (pinfunction "P$2_H1") (pintype "bidirectional"))
      (node (ref "D12") (pin "H1") (pinfunction "P$2_H1") (pintype "bidirectional"))
      (node (ref "D13") (pin "H1") (pinfunction "P$2_H1") (pintype "bidirectional"))
      (node (ref "D14") (pin "H1") (pinfunction "P$2_H1") (pintype "bidirectional"))
    )
    (net (code "83") (name "D03MA11L") (class "Default")
      (node (ref "C16") (pin "S1") (pinfunction "OUT_S1") (pintype "output"))
      (node (ref "D01") (pin "J1") (pinfunction "P$2_J1") (pintype "bidirectional"))
      (node (ref "D02") (pin "J1") (pinfunction "P$2_J1") (pintype "bidirectional"))
      (node (ref "D03") (pin "J1") (pinfunction "P$2_J1") (pintype "bidirectional"))
      (node (ref "D04") (pin "J1") (pinfunction "P$2_J1") (pintype "bidirectional"))
      (node (ref "D05") (pin "J1") (pinfunction "P$2_J1") (pintype "bidirectional"))
      (node (ref "D06") (pin "J1") (pinfunction "P$2_J1") (pintype "bidirectional"))
      (node (ref "D07") (pin "J1") (pinfunction "P$2_J1") (pintype "bidirectional"))
      (node (ref "D08") (pin "J1") (pinfunction "P$2_J1") (pintype "bidirectional"))
      (node (ref "D09") (pin "J1") (pinfunction "P$2_J1") (pintype "bidirectional"))
      (node (ref "D10") (pin "J1") (pinfunction "P$2_J1") (pintype "bidirectional"))
      (node (ref "D11") (pin "J1") (pinfunction "P$2_J1") (pintype "bidirectional"))
      (node (ref "D12") (pin "J1") (pinfunction "P$2_J1") (pintype "bidirectional"))
      (node (ref "D13") (pin "J1") (pinfunction "P$2_J1") (pintype "bidirectional"))
      (node (ref "D14") (pin "J1") (pinfunction "P$2_J1") (pintype "bidirectional"))
    )
    (net (code "84") (name "D03MCBMB0L") (class "Default")
      (node (ref "A19N") (pin "S2") (pinfunction "P$2_S2") (pintype "bidirectional"))
      (node (ref "B19") (pin "A1") (pinfunction "A_A1") (pintype "input"))
    )
    (net (code "85") (name "D03MCBMB1L") (class "Default")
      (node (ref "A19N") (pin "T2") (pinfunction "P$2_T2") (pintype "bidirectional"))
      (node (ref "B19") (pin "B1") (pinfunction "B_B1") (pintype "input"))
    )
    (net (code "86") (name "D03MCBMB2L") (class "Default")
      (node (ref "A19N") (pin "V2") (pinfunction "P$2_V2") (pintype "bidirectional"))
      (node (ref "B19") (pin "F1") (pinfunction "A_F1") (pintype "input"))
    )
    (net (code "87") (name "D03MCBMB3L") (class "Default")
      (node (ref "A20N") (pin "D2") (pinfunction "P$2_D2") (pintype "bidirectional"))
      (node (ref "B19") (pin "H1") (pinfunction "B_H1") (pintype "input"))
    )
    (net (code "88") (name "D03MCBMB4L") (class "Default")
      (node (ref "A20N") (pin "E2") (pinfunction "P$2_E2") (pintype "bidirectional"))
      (node (ref "B19") (pin "M1") (pinfunction "A_M1") (pintype "input"))
    )
    (net (code "89") (name "D03MCBMB5L") (class "Default")
      (node (ref "A20N") (pin "H2") (pinfunction "P$2_H2") (pintype "bidirectional"))
      (node (ref "B19") (pin "N1") (pinfunction "B_N1") (pintype "input"))
    )
    (net (code "90") (name "D03MCBMB6L") (class "Default")
      (node (ref "A18N") (pin "K2") (pinfunction "P$2_K2") (pintype "bidirectional"))
      (node (ref "B19") (pin "D2") (pinfunction "A_D2") (pintype "input"))
    )
    (net (code "91") (name "D03MCBMB7L") (class "Default")
      (node (ref "A18N") (pin "M2") (pinfunction "P$2_M2") (pintype "bidirectional"))
      (node (ref "B19") (pin "E2") (pinfunction "B_E2") (pintype "input"))
    )
    (net (code "92") (name "D03MCBMB8L") (class "Default")
      (node (ref "A18N") (pin "P2") (pinfunction "P$2_P2") (pintype "bidirectional"))
      (node (ref "B19") (pin "K2") (pinfunction "A_K2") (pintype "input"))
    )
    (net (code "93") (name "D03MCBMB9L") (class "Default")
      (node (ref "A18N") (pin "S2") (pinfunction "P$2_S2") (pintype "bidirectional"))
      (node (ref "B19") (pin "L2") (pinfunction "B_L2") (pintype "input"))
    )
    (net (code "94") (name "D03MCBMB10L") (class "Default")
      (node (ref "A18N") (pin "T2") (pinfunction "P$2_T2") (pintype "bidirectional"))
      (node (ref "B19") (pin "R2") (pinfunction "A_R2") (pintype "input"))
    )
    (net (code "95") (name "D03MCBMB11L") (class "Default")
      (node (ref "A18N") (pin "V2") (pinfunction "P$2_V2") (pintype "bidirectional"))
      (node (ref "B19") (pin "S2") (pinfunction "B_S2") (pintype "input"))
    )
    (net (code "96") (name "D03MEMSTART") (class "Default")
      (node (ref "A16") (pin "M2") (pinfunction "P$2_M2") (pintype "bidirectional"))
      (node (ref "D17") (pin "B1") (pinfunction "C_B1") (pintype "input"))
      (node (ref "D17") (pin "L2") (pinfunction "C_L2") (pintype "input"))
      (node (ref "D17") (pin "N1") (pinfunction "C_N1") (pintype "input"))
      (node (ref "D17") (pin "S2") (pinfunction "C_S2") (pintype "input"))
      (node (ref "D18") (pin "F1") (pinfunction "IN_F1") (pintype "input"))
    )
    (net (code "97") (name "D04MD0L") (class "Default")
      (node (ref "A01") (pin "K1") (pinfunction "P$2_K1") (pintype "bidirectional"))
      (node (ref "A02") (pin "K1") (pinfunction "P$2_K1") (pintype "bidirectional"))
      (node (ref "A03") (pin "K1") (pinfunction "P$2_K1") (pintype "bidirectional"))
      (node (ref "A04") (pin "K1") (pinfunction "P$2_K1") (pintype "bidirectional"))
      (node (ref "A05") (pin "K1") (pinfunction "P$2_K1") (pintype "bidirectional"))
      (node (ref "A06") (pin "K1") (pinfunction "P$2_K1") (pintype "bidirectional"))
      (node (ref "A07") (pin "K1") (pinfunction "P$2_K1") (pintype "bidirectional"))
      (node (ref "A08") (pin "K1") (pinfunction "P$2_K1") (pintype "bidirectional"))
      (node (ref "A09") (pin "K1") (pinfunction "P$2_K1") (pintype "bidirectional"))
      (node (ref "A10") (pin "K1") (pinfunction "P$2_K1") (pintype "bidirectional"))
      (node (ref "A11") (pin "K1") (pinfunction "P$2_K1") (pintype "bidirectional"))
      (node (ref "A12") (pin "K1") (pinfunction "P$2_K1") (pintype "bidirectional"))
      (node (ref "A13") (pin "K1") (pinfunction "P$2_K1") (pintype "bidirectional"))
      (node (ref "A14") (pin "K1") (pinfunction "P$2_K1") (pintype "bidirectional"))
      (node (ref "B19") (pin "D1") (pinfunction "D_D1") (pintype "open_collector"))
      (node (ref "D15") (pin "C1") (pinfunction "D_C1") (pintype "input"))
    )
    (net (code "98") (name "D04MD1L") (class "Default")
      (node (ref "A01") (pin "L1") (pinfunction "P$2_L1") (pintype "bidirectional"))
      (node (ref "A02") (pin "L1") (pinfunction "P$2_L1") (pintype "bidirectional"))
      (node (ref "A03") (pin "L1") (pinfunction "P$2_L1") (pintype "bidirectional"))
      (node (ref "A04") (pin "L1") (pinfunction "P$2_L1") (pintype "bidirectional"))
      (node (ref "A05") (pin "L1") (pinfunction "P$2_L1") (pintype "bidirectional"))
      (node (ref "A06") (pin "L1") (pinfunction "P$2_L1") (pintype "bidirectional"))
      (node (ref "A07") (pin "L1") (pinfunction "P$2_L1") (pintype "bidirectional"))
      (node (ref "A08") (pin "L1") (pinfunction "P$2_L1") (pintype "bidirectional"))
      (node (ref "A09") (pin "L1") (pinfunction "P$2_L1") (pintype "bidirectional"))
      (node (ref "A10") (pin "L1") (pinfunction "P$2_L1") (pintype "bidirectional"))
      (node (ref "A11") (pin "L1") (pinfunction "P$2_L1") (pintype "bidirectional"))
      (node (ref "A12") (pin "L1") (pinfunction "P$2_L1") (pintype "bidirectional"))
      (node (ref "A13") (pin "L1") (pinfunction "P$2_L1") (pintype "bidirectional"))
      (node (ref "A14") (pin "L1") (pinfunction "P$2_L1") (pintype "bidirectional"))
      (node (ref "B19") (pin "E1") (pinfunction "E_E1") (pintype "open_collector"))
      (node (ref "D15") (pin "E2") (pinfunction "D_E2") (pintype "input"))
    )
    (net (code "99") (name "D04MD2L") (class "Default")
      (node (ref "A01") (pin "M1") (pinfunction "P$2_M1") (pintype "bidirectional"))
      (node (ref "A02") (pin "M1") (pinfunction "P$2_M1") (pintype "bidirectional"))
      (node (ref "A03") (pin "M1") (pinfunction "P$2_M1") (pintype "bidirectional"))
      (node (ref "A04") (pin "M1") (pinfunction "P$2_M1") (pintype "bidirectional"))
      (node (ref "A05") (pin "M1") (pinfunction "P$2_M1") (pintype "bidirectional"))
      (node (ref "A06") (pin "M1") (pinfunction "P$2_M1") (pintype "bidirectional"))
      (node (ref "A07") (pin "M1") (pinfunction "P$2_M1") (pintype "bidirectional"))
      (node (ref "A08") (pin "M1") (pinfunction "P$2_M1") (pintype "bidirectional"))
      (node (ref "A09") (pin "M1") (pinfunction "P$2_M1") (pintype "bidirectional"))
      (node (ref "A10") (pin "M1") (pinfunction "P$2_M1") (pintype "bidirectional"))
      (node (ref "A11") (pin "M1") (pinfunction "P$2_M1") (pintype "bidirectional"))
      (node (ref "A12") (pin "M1") (pinfunction "P$2_M1") (pintype "bidirectional"))
      (node (ref "A13") (pin "M1") (pinfunction "P$2_M1") (pintype "bidirectional"))
      (node (ref "A14") (pin "M1") (pinfunction "P$2_M1") (pintype "bidirectional"))
      (node (ref "B19") (pin "K1") (pinfunction "D_K1") (pintype "open_collector"))
      (node (ref "D15") (pin "J1") (pinfunction "D_J1") (pintype "input"))
    )
    (net (code "100") (name "D04MD3L") (class "Default")
      (node (ref "A01") (pin "P1") (pinfunction "P$2_P1") (pintype "bidirectional"))
      (node (ref "A02") (pin "P1") (pinfunction "P$2_P1") (pintype "bidirectional"))
      (node (ref "A03") (pin "P1") (pinfunction "P$2_P1") (pintype "bidirectional"))
      (node (ref "A04") (pin "P1") (pinfunction "P$2_P1") (pintype "bidirectional"))
      (node (ref "A05") (pin "P1") (pinfunction "P$2_P1") (pintype "bidirectional"))
      (node (ref "A06") (pin "P1") (pinfunction "P$2_P1") (pintype "bidirectional"))
      (node (ref "A07") (pin "P1") (pinfunction "P$2_P1") (pintype "bidirectional"))
      (node (ref "A08") (pin "P1") (pinfunction "P$2_P1") (pintype "bidirectional"))
      (node (ref "A09") (pin "P1") (pinfunction "P$2_P1") (pintype "bidirectional"))
      (node (ref "A10") (pin "P1") (pinfunction "P$2_P1") (pintype "bidirectional"))
      (node (ref "A11") (pin "P1") (pinfunction "P$2_P1") (pintype "bidirectional"))
      (node (ref "A12") (pin "P1") (pinfunction "P$2_P1") (pintype "bidirectional"))
      (node (ref "A13") (pin "P1") (pinfunction "P$2_P1") (pintype "bidirectional"))
      (node (ref "A14") (pin "P1") (pinfunction "P$2_P1") (pintype "bidirectional"))
      (node (ref "B19") (pin "L1") (pinfunction "E_L1") (pintype "open_collector"))
      (node (ref "D15") (pin "M2") (pinfunction "D_M2") (pintype "input"))
    )
    (net (code "101") (name "D04MD4L") (class "Default")
      (node (ref "B01") (pin "K1") (pinfunction "P$2_K1") (pintype "bidirectional"))
      (node (ref "B02") (pin "K1") (pinfunction "P$2_K1") (pintype "bidirectional"))
      (node (ref "B03") (pin "K1") (pinfunction "P$2_K1") (pintype "bidirectional"))
      (node (ref "B04") (pin "K1") (pinfunction "P$2_K1") (pintype "bidirectional"))
      (node (ref "B05") (pin "K1") (pinfunction "P$2_K1") (pintype "bidirectional"))
      (node (ref "B06") (pin "K1") (pinfunction "P$2_K1") (pintype "bidirectional"))
      (node (ref "B07") (pin "K1") (pinfunction "P$2_K1") (pintype "bidirectional"))
      (node (ref "B08") (pin "K1") (pinfunction "P$2_K1") (pintype "bidirectional"))
      (node (ref "B09") (pin "K1") (pinfunction "P$2_K1") (pintype "bidirectional"))
      (node (ref "B10") (pin "K1") (pinfunction "P$2_K1") (pintype "bidirectional"))
      (node (ref "B11") (pin "K1") (pinfunction "P$2_K1") (pintype "bidirectional"))
      (node (ref "B12") (pin "K1") (pinfunction "P$2_K1") (pintype "bidirectional"))
      (node (ref "B13") (pin "K1") (pinfunction "P$2_K1") (pintype "bidirectional"))
      (node (ref "B14") (pin "K1") (pinfunction "P$2_K1") (pintype "bidirectional"))
      (node (ref "B19") (pin "R1") (pinfunction "D_R1") (pintype "open_collector"))
      (node (ref "D15") (pin "P1") (pinfunction "D_P1") (pintype "input"))
    )
    (net (code "102") (name "D04MD5L") (class "Default")
      (node (ref "B01") (pin "L1") (pinfunction "P$2_L1") (pintype "bidirectional"))
      (node (ref "B02") (pin "L1") (pinfunction "P$2_L1") (pintype "bidirectional"))
      (node (ref "B03") (pin "L1") (pinfunction "P$2_L1") (pintype "bidirectional"))
      (node (ref "B04") (pin "L1") (pinfunction "P$2_L1") (pintype "bidirectional"))
      (node (ref "B05") (pin "L1") (pinfunction "P$2_L1") (pintype "bidirectional"))
      (node (ref "B06") (pin "L1") (pinfunction "P$2_L1") (pintype "bidirectional"))
      (node (ref "B07") (pin "L1") (pinfunction "P$2_L1") (pintype "bidirectional"))
      (node (ref "B08") (pin "L1") (pinfunction "P$2_L1") (pintype "bidirectional"))
      (node (ref "B09") (pin "L1") (pinfunction "P$2_L1") (pintype "bidirectional"))
      (node (ref "B10") (pin "L1") (pinfunction "P$2_L1") (pintype "bidirectional"))
      (node (ref "B11") (pin "L1") (pinfunction "P$2_L1") (pintype "bidirectional"))
      (node (ref "B12") (pin "L1") (pinfunction "P$2_L1") (pintype "bidirectional"))
      (node (ref "B13") (pin "L1") (pinfunction "P$2_L1") (pintype "bidirectional"))
      (node (ref "B14") (pin "L1") (pinfunction "P$2_L1") (pintype "bidirectional"))
      (node (ref "B19") (pin "S1") (pinfunction "E_S1") (pintype "open_collector"))
      (node (ref "D15") (pin "T2") (pinfunction "D_T2") (pintype "input"))
    )
    (net (code "103") (name "D04MD6L") (class "Default")
      (node (ref "B01") (pin "M1") (pinfunction "P$2_M1") (pintype "bidirectional"))
      (node (ref "B02") (pin "M1") (pinfunction "P$2_M1") (pintype "bidirectional"))
      (node (ref "B03") (pin "M1") (pinfunction "P$2_M1") (pintype "bidirectional"))
      (node (ref "B04") (pin "M1") (pinfunction "P$2_M1") (pintype "bidirectional"))
      (node (ref "B05") (pin "M1") (pinfunction "P$2_M1") (pintype "bidirectional"))
      (node (ref "B06") (pin "M1") (pinfunction "P$2_M1") (pintype "bidirectional"))
      (node (ref "B07") (pin "M1") (pinfunction "P$2_M1") (pintype "bidirectional"))
      (node (ref "B08") (pin "M1") (pinfunction "P$2_M1") (pintype "bidirectional"))
      (node (ref "B09") (pin "M1") (pinfunction "P$2_M1") (pintype "bidirectional"))
      (node (ref "B10") (pin "M1") (pinfunction "P$2_M1") (pintype "bidirectional"))
      (node (ref "B11") (pin "M1") (pinfunction "P$2_M1") (pintype "bidirectional"))
      (node (ref "B12") (pin "M1") (pinfunction "P$2_M1") (pintype "bidirectional"))
      (node (ref "B13") (pin "M1") (pinfunction "P$2_M1") (pintype "bidirectional"))
      (node (ref "B14") (pin "M1") (pinfunction "P$2_M1") (pintype "bidirectional"))
      (node (ref "B19") (pin "H2") (pinfunction "D_H2") (pintype "open_collector"))
      (node (ref "D16") (pin "C1") (pinfunction "D_C1") (pintype "input"))
    )
    (net (code "104") (name "D04MD7L") (class "Default")
      (node (ref "B01") (pin "P1") (pinfunction "P$2_P1") (pintype "bidirectional"))
      (node (ref "B02") (pin "P1") (pinfunction "P$2_P1") (pintype "bidirectional"))
      (node (ref "B03") (pin "P1") (pinfunction "P$2_P1") (pintype "bidirectional"))
      (node (ref "B04") (pin "P1") (pinfunction "P$2_P1") (pintype "bidirectional"))
      (node (ref "B05") (pin "P1") (pinfunction "P$2_P1") (pintype "bidirectional"))
      (node (ref "B06") (pin "P1") (pinfunction "P$2_P1") (pintype "bidirectional"))
      (node (ref "B07") (pin "P1") (pinfunction "P$2_P1") (pintype "bidirectional"))
      (node (ref "B08") (pin "P1") (pinfunction "P$2_P1") (pintype "bidirectional"))
      (node (ref "B09") (pin "P1") (pinfunction "P$2_P1") (pintype "bidirectional"))
      (node (ref "B10") (pin "P1") (pinfunction "P$2_P1") (pintype "bidirectional"))
      (node (ref "B11") (pin "P1") (pinfunction "P$2_P1") (pintype "bidirectional"))
      (node (ref "B12") (pin "P1") (pinfunction "P$2_P1") (pintype "bidirectional"))
      (node (ref "B13") (pin "P1") (pinfunction "P$2_P1") (pintype "bidirectional"))
      (node (ref "B14") (pin "P1") (pinfunction "P$2_P1") (pintype "bidirectional"))
      (node (ref "B19") (pin "J2") (pinfunction "E_J2") (pintype "open_collector"))
      (node (ref "D16") (pin "E2") (pinfunction "D_E2") (pintype "input"))
    )
    (net (code "105") (name "D04MD8L") (class "Default")
      (node (ref "B19") (pin "N2") (pinfunction "D_N2") (pintype "open_collector"))
      (node (ref "D01") (pin "K1") (pinfunction "P$2_K1") (pintype "bidirectional"))
      (node (ref "D02") (pin "K1") (pinfunction "P$2_K1") (pintype "bidirectional"))
      (node (ref "D03") (pin "K1") (pinfunction "P$2_K1") (pintype "bidirectional"))
      (node (ref "D04") (pin "K1") (pinfunction "P$2_K1") (pintype "bidirectional"))
      (node (ref "D05") (pin "K1") (pinfunction "P$2_K1") (pintype "bidirectional"))
      (node (ref "D06") (pin "K1") (pinfunction "P$2_K1") (pintype "bidirectional"))
      (node (ref "D07") (pin "K1") (pinfunction "P$2_K1") (pintype "bidirectional"))
      (node (ref "D08") (pin "K1") (pinfunction "P$2_K1") (pintype "bidirectional"))
      (node (ref "D09") (pin "K1") (pinfunction "P$2_K1") (pintype "bidirectional"))
      (node (ref "D10") (pin "K1") (pinfunction "P$2_K1") (pintype "bidirectional"))
      (node (ref "D11") (pin "K1") (pinfunction "P$2_K1") (pintype "bidirectional"))
      (node (ref "D12") (pin "K1") (pinfunction "P$2_K1") (pintype "bidirectional"))
      (node (ref "D13") (pin "K1") (pinfunction "P$2_K1") (pintype "bidirectional"))
      (node (ref "D14") (pin "K1") (pinfunction "P$2_K1") (pintype "bidirectional"))
      (node (ref "D16") (pin "J1") (pinfunction "D_J1") (pintype "input"))
    )
    (net (code "106") (name "D04MD9L") (class "Default")
      (node (ref "B19") (pin "P2") (pinfunction "E_P2") (pintype "open_collector"))
      (node (ref "D01") (pin "L1") (pinfunction "P$2_L1") (pintype "bidirectional"))
      (node (ref "D02") (pin "L1") (pinfunction "P$2_L1") (pintype "bidirectional"))
      (node (ref "D03") (pin "L1") (pinfunction "P$2_L1") (pintype "bidirectional"))
      (node (ref "D04") (pin "L1") (pinfunction "P$2_L1") (pintype "bidirectional"))
      (node (ref "D05") (pin "L1") (pinfunction "P$2_L1") (pintype "bidirectional"))
      (node (ref "D06") (pin "L1") (pinfunction "P$2_L1") (pintype "bidirectional"))
      (node (ref "D07") (pin "L1") (pinfunction "P$2_L1") (pintype "bidirectional"))
      (node (ref "D08") (pin "L1") (pinfunction "P$2_L1") (pintype "bidirectional"))
      (node (ref "D09") (pin "L1") (pinfunction "P$2_L1") (pintype "bidirectional"))
      (node (ref "D10") (pin "L1") (pinfunction "P$2_L1") (pintype "bidirectional"))
      (node (ref "D11") (pin "L1") (pinfunction "P$2_L1") (pintype "bidirectional"))
      (node (ref "D12") (pin "L1") (pinfunction "P$2_L1") (pintype "bidirectional"))
      (node (ref "D13") (pin "L1") (pinfunction "P$2_L1") (pintype "bidirectional"))
      (node (ref "D14") (pin "L1") (pinfunction "P$2_L1") (pintype "bidirectional"))
      (node (ref "D16") (pin "M2") (pinfunction "D_M2") (pintype "input"))
    )
    (net (code "107") (name "D04MD10L") (class "Default")
      (node (ref "B19") (pin "U2") (pinfunction "D_U2") (pintype "open_collector"))
      (node (ref "D01") (pin "M1") (pinfunction "P$2_M1") (pintype "bidirectional"))
      (node (ref "D02") (pin "M1") (pinfunction "P$2_M1") (pintype "bidirectional"))
      (node (ref "D03") (pin "M1") (pinfunction "P$2_M1") (pintype "bidirectional"))
      (node (ref "D04") (pin "M1") (pinfunction "P$2_M1") (pintype "bidirectional"))
      (node (ref "D05") (pin "M1") (pinfunction "P$2_M1") (pintype "bidirectional"))
      (node (ref "D06") (pin "M1") (pinfunction "P$2_M1") (pintype "bidirectional"))
      (node (ref "D07") (pin "M1") (pinfunction "P$2_M1") (pintype "bidirectional"))
      (node (ref "D08") (pin "M1") (pinfunction "P$2_M1") (pintype "bidirectional"))
      (node (ref "D09") (pin "M1") (pinfunction "P$2_M1") (pintype "bidirectional"))
      (node (ref "D10") (pin "M1") (pinfunction "P$2_M1") (pintype "bidirectional"))
      (node (ref "D11") (pin "M1") (pinfunction "P$2_M1") (pintype "bidirectional"))
      (node (ref "D12") (pin "M1") (pinfunction "P$2_M1") (pintype "bidirectional"))
      (node (ref "D13") (pin "M1") (pinfunction "P$2_M1") (pintype "bidirectional"))
      (node (ref "D14") (pin "M1") (pinfunction "P$2_M1") (pintype "bidirectional"))
      (node (ref "D16") (pin "P1") (pinfunction "D_P1") (pintype "input"))
    )
    (net (code "108") (name "D04MD11L") (class "Default")
      (node (ref "B19") (pin "V2") (pinfunction "E_V2") (pintype "open_collector"))
      (node (ref "D01") (pin "P1") (pinfunction "P$2_P1") (pintype "bidirectional"))
      (node (ref "D02") (pin "P1") (pinfunction "P$2_P1") (pintype "bidirectional"))
      (node (ref "D03") (pin "P1") (pinfunction "P$2_P1") (pintype "bidirectional"))
      (node (ref "D04") (pin "P1") (pinfunction "P$2_P1") (pintype "bidirectional"))
      (node (ref "D05") (pin "P1") (pinfunction "P$2_P1") (pintype "bidirectional"))
      (node (ref "D06") (pin "P1") (pinfunction "P$2_P1") (pintype "bidirectional"))
      (node (ref "D07") (pin "P1") (pinfunction "P$2_P1") (pintype "bidirectional"))
      (node (ref "D08") (pin "P1") (pinfunction "P$2_P1") (pintype "bidirectional"))
      (node (ref "D09") (pin "P1") (pinfunction "P$2_P1") (pintype "bidirectional"))
      (node (ref "D10") (pin "P1") (pinfunction "P$2_P1") (pintype "bidirectional"))
      (node (ref "D11") (pin "P1") (pinfunction "P$2_P1") (pintype "bidirectional"))
      (node (ref "D12") (pin "P1") (pinfunction "P$2_P1") (pintype "bidirectional"))
      (node (ref "D13") (pin "P1") (pinfunction "P$2_P1") (pintype "bidirectional"))
      (node (ref "D14") (pin "P1") (pinfunction "P$2_P1") (pintype "bidirectional"))
      (node (ref "D16") (pin "T2") (pinfunction "D_T2") (pintype "input"))
    )
    (net (code "109") (name "GND") (class "Default")
      (node (ref "A01") (pin "C1") (pinfunction "P$2_C1") (pintype "bidirectional"))
      (node (ref "A01") (pin "C2") (pinfunction "P$2_C2") (pintype "bidirectional"))
      (node (ref "A01") (pin "F1") (pinfunction "P$2_F1") (pintype "bidirectional"))
      (node (ref "A01") (pin "F2") (pinfunction "P$2_F2") (pintype "bidirectional"))
      (node (ref "A01") (pin "N1") (pinfunction "P$2_N1") (pintype "bidirectional"))
      (node (ref "A01") (pin "N2") (pinfunction "P$2_N2") (pintype "bidirectional"))
      (node (ref "A01") (pin "T1") (pinfunction "P$2_T1") (pintype "bidirectional"))
      (node (ref "A01") (pin "T2") (pinfunction "P$2_T2") (pintype "bidirectional"))
      (node (ref "A02") (pin "C1") (pinfunction "P$2_C1") (pintype "bidirectional"))
      (node (ref "A02") (pin "C2") (pinfunction "P$2_C2") (pintype "bidirectional"))
      (node (ref "A02") (pin "F1") (pinfunction "P$2_F1") (pintype "bidirectional"))
      (node (ref "A02") (pin "F2") (pinfunction "P$2_F2") (pintype "bidirectional"))
      (node (ref "A02") (pin "N1") (pinfunction "P$2_N1") (pintype "bidirectional"))
      (node (ref "A02") (pin "N2") (pinfunction "P$2_N2") (pintype "bidirectional"))
      (node (ref "A02") (pin "T1") (pinfunction "P$2_T1") (pintype "bidirectional"))
      (node (ref "A02") (pin "T2") (pinfunction "P$2_T2") (pintype "bidirectional"))
      (node (ref "A03") (pin "C1") (pinfunction "P$2_C1") (pintype "bidirectional"))
      (node (ref "A03") (pin "C2") (pinfunction "P$2_C2") (pintype "bidirectional"))
      (node (ref "A03") (pin "F1") (pinfunction "P$2_F1") (pintype "bidirectional"))
      (node (ref "A03") (pin "F2") (pinfunction "P$2_F2") (pintype "bidirectional"))
      (node (ref "A03") (pin "N1") (pinfunction "P$2_N1") (pintype "bidirectional"))
      (node (ref "A03") (pin "N2") (pinfunction "P$2_N2") (pintype "bidirectional"))
      (node (ref "A03") (pin "T1") (pinfunction "P$2_T1") (pintype "bidirectional"))
      (node (ref "A03") (pin "T2") (pinfunction "P$2_T2") (pintype "bidirectional"))
      (node (ref "A04") (pin "C1") (pinfunction "P$2_C1") (pintype "bidirectional"))
      (node (ref "A04") (pin "C2") (pinfunction "P$2_C2") (pintype "bidirectional"))
      (node (ref "A04") (pin "F1") (pinfunction "P$2_F1") (pintype "bidirectional"))
      (node (ref "A04") (pin "F2") (pinfunction "P$2_F2") (pintype "bidirectional"))
      (node (ref "A04") (pin "N1") (pinfunction "P$2_N1") (pintype "bidirectional"))
      (node (ref "A04") (pin "N2") (pinfunction "P$2_N2") (pintype "bidirectional"))
      (node (ref "A04") (pin "T1") (pinfunction "P$2_T1") (pintype "bidirectional"))
      (node (ref "A04") (pin "T2") (pinfunction "P$2_T2") (pintype "bidirectional"))
      (node (ref "A05") (pin "C1") (pinfunction "P$2_C1") (pintype "bidirectional"))
      (node (ref "A05") (pin "C2") (pinfunction "P$2_C2") (pintype "bidirectional"))
      (node (ref "A05") (pin "F1") (pinfunction "P$2_F1") (pintype "bidirectional"))
      (node (ref "A05") (pin "F2") (pinfunction "P$2_F2") (pintype "bidirectional"))
      (node (ref "A05") (pin "N1") (pinfunction "P$2_N1") (pintype "bidirectional"))
      (node (ref "A05") (pin "N2") (pinfunction "P$2_N2") (pintype "bidirectional"))
      (node (ref "A05") (pin "T1") (pinfunction "P$2_T1") (pintype "bidirectional"))
      (node (ref "A05") (pin "T2") (pinfunction "P$2_T2") (pintype "bidirectional"))
      (node (ref "A06") (pin "C1") (pinfunction "P$2_C1") (pintype "bidirectional"))
      (node (ref "A06") (pin "C2") (pinfunction "P$2_C2") (pintype "bidirectional"))
      (node (ref "A06") (pin "F1") (pinfunction "P$2_F1") (pintype "bidirectional"))
      (node (ref "A06") (pin "F2") (pinfunction "P$2_F2") (pintype "bidirectional"))
      (node (ref "A06") (pin "N1") (pinfunction "P$2_N1") (pintype "bidirectional"))
      (node (ref "A06") (pin "N2") (pinfunction "P$2_N2") (pintype "bidirectional"))
      (node (ref "A06") (pin "T1") (pinfunction "P$2_T1") (pintype "bidirectional"))
      (node (ref "A06") (pin "T2") (pinfunction "P$2_T2") (pintype "bidirectional"))
      (node (ref "A07") (pin "C1") (pinfunction "P$2_C1") (pintype "bidirectional"))
      (node (ref "A07") (pin "C2") (pinfunction "P$2_C2") (pintype "bidirectional"))
      (node (ref "A07") (pin "F1") (pinfunction "P$2_F1") (pintype "bidirectional"))
      (node (ref "A07") (pin "F2") (pinfunction "P$2_F2") (pintype "bidirectional"))
      (node (ref "A07") (pin "N1") (pinfunction "P$2_N1") (pintype "bidirectional"))
      (node (ref "A07") (pin "N2") (pinfunction "P$2_N2") (pintype "bidirectional"))
      (node (ref "A07") (pin "T1") (pinfunction "P$2_T1") (pintype "bidirectional"))
      (node (ref "A07") (pin "T2") (pinfunction "P$2_T2") (pintype "bidirectional"))
      (node (ref "A08") (pin "C1") (pinfunction "P$2_C1") (pintype "bidirectional"))
      (node (ref "A08") (pin "C2") (pinfunction "P$2_C2") (pintype "bidirectional"))
      (node (ref "A08") (pin "F1") (pinfunction "P$2_F1") (pintype "bidirectional"))
      (node (ref "A08") (pin "F2") (pinfunction "P$2_F2") (pintype "bidirectional"))
      (node (ref "A08") (pin "N1") (pinfunction "P$2_N1") (pintype "bidirectional"))
      (node (ref "A08") (pin "N2") (pinfunction "P$2_N2") (pintype "bidirectional"))
      (node (ref "A08") (pin "T1") (pinfunction "P$2_T1") (pintype "bidirectional"))
      (node (ref "A08") (pin "T2") (pinfunction "P$2_T2") (pintype "bidirectional"))
      (node (ref "A09") (pin "C1") (pinfunction "P$2_C1") (pintype "bidirectional"))
      (node (ref "A09") (pin "C2") (pinfunction "P$2_C2") (pintype "bidirectional"))
      (node (ref "A09") (pin "F1") (pinfunction "P$2_F1") (pintype "bidirectional"))
      (node (ref "A09") (pin "F2") (pinfunction "P$2_F2") (pintype "bidirectional"))
      (node (ref "A09") (pin "N1") (pinfunction "P$2_N1") (pintype "bidirectional"))
      (node (ref "A09") (pin "N2") (pinfunction "P$2_N2") (pintype "bidirectional"))
      (node (ref "A09") (pin "T1") (pinfunction "P$2_T1") (pintype "bidirectional"))
      (node (ref "A09") (pin "T2") (pinfunction "P$2_T2") (pintype "bidirectional"))
      (node (ref "A10") (pin "C1") (pinfunction "P$2_C1") (pintype "bidirectional"))
      (node (ref "A10") (pin "C2") (pinfunction "P$2_C2") (pintype "bidirectional"))
      (node (ref "A10") (pin "F1") (pinfunction "P$2_F1") (pintype "bidirectional"))
      (node (ref "A10") (pin "F2") (pinfunction "P$2_F2") (pintype "bidirectional"))
      (node (ref "A10") (pin "N1") (pinfunction "P$2_N1") (pintype "bidirectional"))
      (node (ref "A10") (pin "N2") (pinfunction "P$2_N2") (pintype "bidirectional"))
      (node (ref "A10") (pin "T1") (pinfunction "P$2_T1") (pintype "bidirectional"))
      (node (ref "A10") (pin "T2") (pinfunction "P$2_T2") (pintype "bidirectional"))
      (node (ref "A11") (pin "C1") (pinfunction "P$2_C1") (pintype "bidirectional"))
      (node (ref "A11") (pin "C2") (pinfunction "P$2_C2") (pintype "bidirectional"))
      (node (ref "A11") (pin "F1") (pinfunction "P$2_F1") (pintype "bidirectional"))
      (node (ref "A11") (pin "F2") (pinfunction "P$2_F2") (pintype "bidirectional"))
      (node (ref "A11") (pin "N1") (pinfunction "P$2_N1") (pintype "bidirectional"))
      (node (ref "A11") (pin "N2") (pinfunction "P$2_N2") (pintype "bidirectional"))
      (node (ref "A11") (pin "T1") (pinfunction "P$2_T1") (pintype "bidirectional"))
      (node (ref "A11") (pin "T2") (pinfunction "P$2_T2") (pintype "bidirectional"))
      (node (ref "A12") (pin "C1") (pinfunction "P$2_C1") (pintype "bidirectional"))
      (node (ref "A12") (pin "C2") (pinfunction "P$2_C2") (pintype "bidirectional"))
      (node (ref "A12") (pin "F1") (pinfunction "P$2_F1") (pintype "bidirectional"))
      (node (ref "A12") (pin "F2") (pinfunction "P$2_F2") (pintype "bidirectional"))
      (node (ref "A12") (pin "N1") (pinfunction "P$2_N1") (pintype "bidirectional"))
      (node (ref "A12") (pin "N2") (pinfunction "P$2_N2") (pintype "bidirectional"))
      (node (ref "A12") (pin "T1") (pinfunction "P$2_T1") (pintype "bidirectional"))
      (node (ref "A12") (pin "T2") (pinfunction "P$2_T2") (pintype "bidirectional"))
      (node (ref "A13") (pin "C1") (pinfunction "P$2_C1") (pintype "bidirectional"))
      (node (ref "A13") (pin "C2") (pinfunction "P$2_C2") (pintype "bidirectional"))
      (node (ref "A13") (pin "F1") (pinfunction "P$2_F1") (pintype "bidirectional"))
      (node (ref "A13") (pin "F2") (pinfunction "P$2_F2") (pintype "bidirectional"))
      (node (ref "A13") (pin "N1") (pinfunction "P$2_N1") (pintype "bidirectional"))
      (node (ref "A13") (pin "N2") (pinfunction "P$2_N2") (pintype "bidirectional"))
      (node (ref "A13") (pin "T1") (pinfunction "P$2_T1") (pintype "bidirectional"))
      (node (ref "A13") (pin "T2") (pinfunction "P$2_T2") (pintype "bidirectional"))
      (node (ref "A14") (pin "C1") (pinfunction "P$2_C1") (pintype "bidirectional"))
      (node (ref "A14") (pin "C2") (pinfunction "P$2_C2") (pintype "bidirectional"))
      (node (ref "A14") (pin "F1") (pinfunction "P$2_F1") (pintype "bidirectional"))
      (node (ref "A14") (pin "F2") (pinfunction "P$2_F2") (pintype "bidirectional"))
      (node (ref "A14") (pin "N1") (pinfunction "P$2_N1") (pintype "bidirectional"))
      (node (ref "A14") (pin "N2") (pinfunction "P$2_N2") (pintype "bidirectional"))
      (node (ref "A14") (pin "T1") (pinfunction "P$2_T1") (pintype "bidirectional"))
      (node (ref "A14") (pin "T2") (pinfunction "P$2_T2") (pintype "bidirectional"))
      (node (ref "B01") (pin "C1") (pinfunction "P$2_C1") (pintype "bidirectional"))
      (node (ref "B01") (pin "C2") (pinfunction "P$2_C2") (pintype "bidirectional"))
      (node (ref "B01") (pin "F1") (pinfunction "P$2_F1") (pintype "bidirectional"))
      (node (ref "B01") (pin "F2") (pinfunction "P$2_F2") (pintype "bidirectional"))
      (node (ref "B01") (pin "N1") (pinfunction "P$2_N1") (pintype "bidirectional"))
      (node (ref "B01") (pin "N2") (pinfunction "P$2_N2") (pintype "bidirectional"))
      (node (ref "B01") (pin "T1") (pinfunction "P$2_T1") (pintype "bidirectional"))
      (node (ref "B01") (pin "T2") (pinfunction "P$2_T2") (pintype "bidirectional"))
      (node (ref "B02") (pin "C1") (pinfunction "P$2_C1") (pintype "bidirectional"))
      (node (ref "B02") (pin "C2") (pinfunction "P$2_C2") (pintype "bidirectional"))
      (node (ref "B02") (pin "F1") (pinfunction "P$2_F1") (pintype "bidirectional"))
      (node (ref "B02") (pin "F2") (pinfunction "P$2_F2") (pintype "bidirectional"))
      (node (ref "B02") (pin "N1") (pinfunction "P$2_N1") (pintype "bidirectional"))
      (node (ref "B02") (pin "N2") (pinfunction "P$2_N2") (pintype "bidirectional"))
      (node (ref "B02") (pin "T1") (pinfunction "P$2_T1") (pintype "bidirectional"))
      (node (ref "B02") (pin "T2") (pinfunction "P$2_T2") (pintype "bidirectional"))
      (node (ref "B03") (pin "C1") (pinfunction "P$2_C1") (pintype "bidirectional"))
      (node (ref "B03") (pin "C2") (pinfunction "P$2_C2") (pintype "bidirectional"))
      (node (ref "B03") (pin "F1") (pinfunction "P$2_F1") (pintype "bidirectional"))
      (node (ref "B03") (pin "F2") (pinfunction "P$2_F2") (pintype "bidirectional"))
      (node (ref "B03") (pin "N1") (pinfunction "P$2_N1") (pintype "bidirectional"))
      (node (ref "B03") (pin "N2") (pinfunction "P$2_N2") (pintype "bidirectional"))
      (node (ref "B03") (pin "T1") (pinfunction "P$2_T1") (pintype "bidirectional"))
      (node (ref "B03") (pin "T2") (pinfunction "P$2_T2") (pintype "bidirectional"))
      (node (ref "B04") (pin "C1") (pinfunction "P$2_C1") (pintype "bidirectional"))
      (node (ref "B04") (pin "C2") (pinfunction "P$2_C2") (pintype "bidirectional"))
      (node (ref "B04") (pin "F1") (pinfunction "P$2_F1") (pintype "bidirectional"))
      (node (ref "B04") (pin "F2") (pinfunction "P$2_F2") (pintype "bidirectional"))
      (node (ref "B04") (pin "N1") (pinfunction "P$2_N1") (pintype "bidirectional"))
      (node (ref "B04") (pin "N2") (pinfunction "P$2_N2") (pintype "bidirectional"))
      (node (ref "B04") (pin "T1") (pinfunction "P$2_T1") (pintype "bidirectional"))
      (node (ref "B04") (pin "T2") (pinfunction "P$2_T2") (pintype "bidirectional"))
      (node (ref "B05") (pin "C1") (pinfunction "P$2_C1") (pintype "bidirectional"))
      (node (ref "B05") (pin "C2") (pinfunction "P$2_C2") (pintype "bidirectional"))
      (node (ref "B05") (pin "F1") (pinfunction "P$2_F1") (pintype "bidirectional"))
      (node (ref "B05") (pin "F2") (pinfunction "P$2_F2") (pintype "bidirectional"))
      (node (ref "B05") (pin "N1") (pinfunction "P$2_N1") (pintype "bidirectional"))
      (node (ref "B05") (pin "N2") (pinfunction "P$2_N2") (pintype "bidirectional"))
      (node (ref "B05") (pin "T1") (pinfunction "P$2_T1") (pintype "bidirectional"))
      (node (ref "B05") (pin "T2") (pinfunction "P$2_T2") (pintype "bidirectional"))
      (node (ref "B06") (pin "C1") (pinfunction "P$2_C1") (pintype "bidirectional"))
      (node (ref "B06") (pin "C2") (pinfunction "P$2_C2") (pintype "bidirectional"))
      (node (ref "B06") (pin "F1") (pinfunction "P$2_F1") (pintype "bidirectional"))
      (node (ref "B06") (pin "F2") (pinfunction "P$2_F2") (pintype "bidirectional"))
      (node (ref "B06") (pin "N1") (pinfunction "P$2_N1") (pintype "bidirectional"))
      (node (ref "B06") (pin "N2") (pinfunction "P$2_N2") (pintype "bidirectional"))
      (node (ref "B06") (pin "T1") (pinfunction "P$2_T1") (pintype "bidirectional"))
      (node (ref "B06") (pin "T2") (pinfunction "P$2_T2") (pintype "bidirectional"))
      (node (ref "B07") (pin "C1") (pinfunction "P$2_C1") (pintype "bidirectional"))
      (node (ref "B07") (pin "C2") (pinfunction "P$2_C2") (pintype "bidirectional"))
      (node (ref "B07") (pin "F1") (pinfunction "P$2_F1") (pintype "bidirectional"))
      (node (ref "B07") (pin "F2") (pinfunction "P$2_F2") (pintype "bidirectional"))
      (node (ref "B07") (pin "N1") (pinfunction "P$2_N1") (pintype "bidirectional"))
      (node (ref "B07") (pin "N2") (pinfunction "P$2_N2") (pintype "bidirectional"))
      (node (ref "B07") (pin "T1") (pinfunction "P$2_T1") (pintype "bidirectional"))
      (node (ref "B07") (pin "T2") (pinfunction "P$2_T2") (pintype "bidirectional"))
      (node (ref "B08") (pin "C1") (pinfunction "P$2_C1") (pintype "bidirectional"))
      (node (ref "B08") (pin "C2") (pinfunction "P$2_C2") (pintype "bidirectional"))
      (node (ref "B08") (pin "F1") (pinfunction "P$2_F1") (pintype "bidirectional"))
      (node (ref "B08") (pin "F2") (pinfunction "P$2_F2") (pintype "bidirectional"))
      (node (ref "B08") (pin "N1") (pinfunction "P$2_N1") (pintype "bidirectional"))
      (node (ref "B08") (pin "N2") (pinfunction "P$2_N2") (pintype "bidirectional"))
      (node (ref "B08") (pin "T1") (pinfunction "P$2_T1") (pintype "bidirectional"))
      (node (ref "B08") (pin "T2") (pinfunction "P$2_T2") (pintype "bidirectional"))
      (node (ref "B09") (pin "C1") (pinfunction "P$2_C1") (pintype "bidirectional"))
      (node (ref "B09") (pin "C2") (pinfunction "P$2_C2") (pintype "bidirectional"))
      (node (ref "B09") (pin "F1") (pinfunction "P$2_F1") (pintype "bidirectional"))
      (node (ref "B09") (pin "F2") (pinfunction "P$2_F2") (pintype "bidirectional"))
      (node (ref "B09") (pin "N1") (pinfunction "P$2_N1") (pintype "bidirectional"))
      (node (ref "B09") (pin "N2") (pinfunction "P$2_N2") (pintype "bidirectional"))
      (node (ref "B09") (pin "T1") (pinfunction "P$2_T1") (pintype "bidirectional"))
      (node (ref "B09") (pin "T2") (pinfunction "P$2_T2") (pintype "bidirectional"))
      (node (ref "B10") (pin "C1") (pinfunction "P$2_C1") (pintype "bidirectional"))
      (node (ref "B10") (pin "C2") (pinfunction "P$2_C2") (pintype "bidirectional"))
      (node (ref "B10") (pin "F1") (pinfunction "P$2_F1") (pintype "bidirectional"))
      (node (ref "B10") (pin "F2") (pinfunction "P$2_F2") (pintype "bidirectional"))
      (node (ref "B10") (pin "N1") (pinfunction "P$2_N1") (pintype "bidirectional"))
      (node (ref "B10") (pin "N2") (pinfunction "P$2_N2") (pintype "bidirectional"))
      (node (ref "B10") (pin "T1") (pinfunction "P$2_T1") (pintype "bidirectional"))
      (node (ref "B10") (pin "T2") (pinfunction "P$2_T2") (pintype "bidirectional"))
      (node (ref "B11") (pin "C1") (pinfunction "P$2_C1") (pintype "bidirectional"))
      (node (ref "B11") (pin "C2") (pinfunction "P$2_C2") (pintype "bidirectional"))
      (node (ref "B11") (pin "F1") (pinfunction "P$2_F1") (pintype "bidirectional"))
      (node (ref "B11") (pin "F2") (pinfunction "P$2_F2") (pintype "bidirectional"))
      (node (ref "B11") (pin "N1") (pinfunction "P$2_N1") (pintype "bidirectional"))
      (node (ref "B11") (pin "N2") (pinfunction "P$2_N2") (pintype "bidirectional"))
      (node (ref "B11") (pin "T1") (pinfunction "P$2_T1") (pintype "bidirectional"))
      (node (ref "B11") (pin "T2") (pinfunction "P$2_T2") (pintype "bidirectional"))
      (node (ref "B12") (pin "C1") (pinfunction "P$2_C1") (pintype "bidirectional"))
      (node (ref "B12") (pin "C2") (pinfunction "P$2_C2") (pintype "bidirectional"))
      (node (ref "B12") (pin "F1") (pinfunction "P$2_F1") (pintype "bidirectional"))
      (node (ref "B12") (pin "F2") (pinfunction "P$2_F2") (pintype "bidirectional"))
      (node (ref "B12") (pin "N1") (pinfunction "P$2_N1") (pintype "bidirectional"))
      (node (ref "B12") (pin "N2") (pinfunction "P$2_N2") (pintype "bidirectional"))
      (node (ref "B12") (pin "T1") (pinfunction "P$2_T1") (pintype "bidirectional"))
      (node (ref "B12") (pin "T2") (pinfunction "P$2_T2") (pintype "bidirectional"))
      (node (ref "B13") (pin "C1") (pinfunction "P$2_C1") (pintype "bidirectional"))
      (node (ref "B13") (pin "C2") (pinfunction "P$2_C2") (pintype "bidirectional"))
      (node (ref "B13") (pin "F1") (pinfunction "P$2_F1") (pintype "bidirectional"))
      (node (ref "B13") (pin "F2") (pinfunction "P$2_F2") (pintype "bidirectional"))
      (node (ref "B13") (pin "N1") (pinfunction "P$2_N1") (pintype "bidirectional"))
      (node (ref "B13") (pin "N2") (pinfunction "P$2_N2") (pintype "bidirectional"))
      (node (ref "B13") (pin "T1") (pinfunction "P$2_T1") (pintype "bidirectional"))
      (node (ref "B13") (pin "T2") (pinfunction "P$2_T2") (pintype "bidirectional"))
      (node (ref "B14") (pin "C1") (pinfunction "P$2_C1") (pintype "bidirectional"))
      (node (ref "B14") (pin "C2") (pinfunction "P$2_C2") (pintype "bidirectional"))
      (node (ref "B14") (pin "F1") (pinfunction "P$2_F1") (pintype "bidirectional"))
      (node (ref "B14") (pin "F2") (pinfunction "P$2_F2") (pintype "bidirectional"))
      (node (ref "B14") (pin "N1") (pinfunction "P$2_N1") (pintype "bidirectional"))
      (node (ref "B14") (pin "N2") (pinfunction "P$2_N2") (pintype "bidirectional"))
      (node (ref "B14") (pin "T1") (pinfunction "P$2_T1") (pintype "bidirectional"))
      (node (ref "B14") (pin "T2") (pinfunction "P$2_T2") (pintype "bidirectional"))
      (node (ref "B17") (pin "P1") (pinfunction "IN1_P1") (pintype "input"))
      (node (ref "B17") (pin "R1") (pinfunction "IN2_R1") (pintype "input"))
      (node (ref "C01") (pin "C1") (pinfunction "P$2_C1") (pintype "bidirectional"))
      (node (ref "C01") (pin "C2") (pinfunction "P$2_C2") (pintype "bidirectional"))
      (node (ref "C01") (pin "F1") (pinfunction "P$2_F1") (pintype "bidirectional"))
      (node (ref "C01") (pin "F2") (pinfunction "P$2_F2") (pintype "bidirectional"))
      (node (ref "C01") (pin "N1") (pinfunction "P$2_N1") (pintype "bidirectional"))
      (node (ref "C01") (pin "N2") (pinfunction "P$2_N2") (pintype "bidirectional"))
      (node (ref "C01") (pin "T1") (pinfunction "P$2_T1") (pintype "bidirectional"))
      (node (ref "C01") (pin "T2") (pinfunction "P$2_T2") (pintype "bidirectional"))
      (node (ref "C02") (pin "C1") (pinfunction "P$2_C1") (pintype "bidirectional"))
      (node (ref "C02") (pin "C2") (pinfunction "P$2_C2") (pintype "bidirectional"))
      (node (ref "C02") (pin "F1") (pinfunction "P$2_F1") (pintype "bidirectional"))
      (node (ref "C02") (pin "F2") (pinfunction "P$2_F2") (pintype "bidirectional"))
      (node (ref "C02") (pin "N1") (pinfunction "P$2_N1") (pintype "bidirectional"))
      (node (ref "C02") (pin "N2") (pinfunction "P$2_N2") (pintype "bidirectional"))
      (node (ref "C02") (pin "T1") (pinfunction "P$2_T1") (pintype "bidirectional"))
      (node (ref "C02") (pin "T2") (pinfunction "P$2_T2") (pintype "bidirectional"))
      (node (ref "C03") (pin "C1") (pinfunction "P$2_C1") (pintype "bidirectional"))
      (node (ref "C03") (pin "C2") (pinfunction "P$2_C2") (pintype "bidirectional"))
      (node (ref "C03") (pin "F1") (pinfunction "P$2_F1") (pintype "bidirectional"))
      (node (ref "C03") (pin "F2") (pinfunction "P$2_F2") (pintype "bidirectional"))
      (node (ref "C03") (pin "N1") (pinfunction "P$2_N1") (pintype "bidirectional"))
      (node (ref "C03") (pin "N2") (pinfunction "P$2_N2") (pintype "bidirectional"))
      (node (ref "C03") (pin "T1") (pinfunction "P$2_T1") (pintype "bidirectional"))
      (node (ref "C03") (pin "T2") (pinfunction "P$2_T2") (pintype "bidirectional"))
      (node (ref "C04") (pin "C1") (pinfunction "P$2_C1") (pintype "bidirectional"))
      (node (ref "C04") (pin "C2") (pinfunction "P$2_C2") (pintype "bidirectional"))
      (node (ref "C04") (pin "F1") (pinfunction "P$2_F1") (pintype "bidirectional"))
      (node (ref "C04") (pin "F2") (pinfunction "P$2_F2") (pintype "bidirectional"))
      (node (ref "C04") (pin "N1") (pinfunction "P$2_N1") (pintype "bidirectional"))
      (node (ref "C04") (pin "N2") (pinfunction "P$2_N2") (pintype "bidirectional"))
      (node (ref "C04") (pin "T1") (pinfunction "P$2_T1") (pintype "bidirectional"))
      (node (ref "C04") (pin "T2") (pinfunction "P$2_T2") (pintype "bidirectional"))
      (node (ref "C05") (pin "C1") (pinfunction "P$2_C1") (pintype "bidirectional"))
      (node (ref "C05") (pin "C2") (pinfunction "P$2_C2") (pintype "bidirectional"))
      (node (ref "C05") (pin "F1") (pinfunction "P$2_F1") (pintype "bidirectional"))
      (node (ref "C05") (pin "F2") (pinfunction "P$2_F2") (pintype "bidirectional"))
      (node (ref "C05") (pin "N1") (pinfunction "P$2_N1") (pintype "bidirectional"))
      (node (ref "C05") (pin "N2") (pinfunction "P$2_N2") (pintype "bidirectional"))
      (node (ref "C05") (pin "T1") (pinfunction "P$2_T1") (pintype "bidirectional"))
      (node (ref "C05") (pin "T2") (pinfunction "P$2_T2") (pintype "bidirectional"))
      (node (ref "C06") (pin "C1") (pinfunction "P$2_C1") (pintype "bidirectional"))
      (node (ref "C06") (pin "C2") (pinfunction "P$2_C2") (pintype "bidirectional"))
      (node (ref "C06") (pin "F1") (pinfunction "P$2_F1") (pintype "bidirectional"))
      (node (ref "C06") (pin "F2") (pinfunction "P$2_F2") (pintype "bidirectional"))
      (node (ref "C06") (pin "N1") (pinfunction "P$2_N1") (pintype "bidirectional"))
      (node (ref "C06") (pin "N2") (pinfunction "P$2_N2") (pintype "bidirectional"))
      (node (ref "C06") (pin "T1") (pinfunction "P$2_T1") (pintype "bidirectional"))
      (node (ref "C06") (pin "T2") (pinfunction "P$2_T2") (pintype "bidirectional"))
      (node (ref "C07") (pin "C1") (pinfunction "P$2_C1") (pintype "bidirectional"))
      (node (ref "C07") (pin "C2") (pinfunction "P$2_C2") (pintype "bidirectional"))
      (node (ref "C07") (pin "F1") (pinfunction "P$2_F1") (pintype "bidirectional"))
      (node (ref "C07") (pin "F2") (pinfunction "P$2_F2") (pintype "bidirectional"))
      (node (ref "C07") (pin "N1") (pinfunction "P$2_N1") (pintype "bidirectional"))
      (node (ref "C07") (pin "N2") (pinfunction "P$2_N2") (pintype "bidirectional"))
      (node (ref "C07") (pin "T1") (pinfunction "P$2_T1") (pintype "bidirectional"))
      (node (ref "C07") (pin "T2") (pinfunction "P$2_T2") (pintype "bidirectional"))
      (node (ref "C08") (pin "C1") (pinfunction "P$2_C1") (pintype "bidirectional"))
      (node (ref "C08") (pin "C2") (pinfunction "P$2_C2") (pintype "bidirectional"))
      (node (ref "C08") (pin "F1") (pinfunction "P$2_F1") (pintype "bidirectional"))
      (node (ref "C08") (pin "F2") (pinfunction "P$2_F2") (pintype "bidirectional"))
      (node (ref "C08") (pin "N1") (pinfunction "P$2_N1") (pintype "bidirectional"))
      (node (ref "C08") (pin "N2") (pinfunction "P$2_N2") (pintype "bidirectional"))
      (node (ref "C08") (pin "T1") (pinfunction "P$2_T1") (pintype "bidirectional"))
      (node (ref "C08") (pin "T2") (pinfunction "P$2_T2") (pintype "bidirectional"))
      (node (ref "C09") (pin "C1") (pinfunction "P$2_C1") (pintype "bidirectional"))
      (node (ref "C09") (pin "C2") (pinfunction "P$2_C2") (pintype "bidirectional"))
      (node (ref "C09") (pin "F1") (pinfunction "P$2_F1") (pintype "bidirectional"))
      (node (ref "C09") (pin "F2") (pinfunction "P$2_F2") (pintype "bidirectional"))
      (node (ref "C09") (pin "N1") (pinfunction "P$2_N1") (pintype "bidirectional"))
      (node (ref "C09") (pin "N2") (pinfunction "P$2_N2") (pintype "bidirectional"))
      (node (ref "C09") (pin "T1") (pinfunction "P$2_T1") (pintype "bidirectional"))
      (node (ref "C09") (pin "T2") (pinfunction "P$2_T2") (pintype "bidirectional"))
      (node (ref "C10") (pin "C1") (pinfunction "P$2_C1") (pintype "bidirectional"))
      (node (ref "C10") (pin "C2") (pinfunction "P$2_C2") (pintype "bidirectional"))
      (node (ref "C10") (pin "F1") (pinfunction "P$2_F1") (pintype "bidirectional"))
      (node (ref "C10") (pin "F2") (pinfunction "P$2_F2") (pintype "bidirectional"))
      (node (ref "C10") (pin "N1") (pinfunction "P$2_N1") (pintype "bidirectional"))
      (node (ref "C10") (pin "N2") (pinfunction "P$2_N2") (pintype "bidirectional"))
      (node (ref "C10") (pin "T1") (pinfunction "P$2_T1") (pintype "bidirectional"))
      (node (ref "C10") (pin "T2") (pinfunction "P$2_T2") (pintype "bidirectional"))
      (node (ref "C11") (pin "C1") (pinfunction "P$2_C1") (pintype "bidirectional"))
      (node (ref "C11") (pin "C2") (pinfunction "P$2_C2") (pintype "bidirectional"))
      (node (ref "C11") (pin "F1") (pinfunction "P$2_F1") (pintype "bidirectional"))
      (node (ref "C11") (pin "F2") (pinfunction "P$2_F2") (pintype "bidirectional"))
      (node (ref "C11") (pin "N1") (pinfunction "P$2_N1") (pintype "bidirectional"))
      (node (ref "C11") (pin "N2") (pinfunction "P$2_N2") (pintype "bidirectional"))
      (node (ref "C11") (pin "T1") (pinfunction "P$2_T1") (pintype "bidirectional"))
      (node (ref "C11") (pin "T2") (pinfunction "P$2_T2") (pintype "bidirectional"))
      (node (ref "C12") (pin "C1") (pinfunction "P$2_C1") (pintype "bidirectional"))
      (node (ref "C12") (pin "C2") (pinfunction "P$2_C2") (pintype "bidirectional"))
      (node (ref "C12") (pin "F1") (pinfunction "P$2_F1") (pintype "bidirectional"))
      (node (ref "C12") (pin "F2") (pinfunction "P$2_F2") (pintype "bidirectional"))
      (node (ref "C12") (pin "N1") (pinfunction "P$2_N1") (pintype "bidirectional"))
      (node (ref "C12") (pin "N2") (pinfunction "P$2_N2") (pintype "bidirectional"))
      (node (ref "C12") (pin "T1") (pinfunction "P$2_T1") (pintype "bidirectional"))
      (node (ref "C12") (pin "T2") (pinfunction "P$2_T2") (pintype "bidirectional"))
      (node (ref "C13") (pin "C1") (pinfunction "P$2_C1") (pintype "bidirectional"))
      (node (ref "C13") (pin "C2") (pinfunction "P$2_C2") (pintype "bidirectional"))
      (node (ref "C13") (pin "F1") (pinfunction "P$2_F1") (pintype "bidirectional"))
      (node (ref "C13") (pin "F2") (pinfunction "P$2_F2") (pintype "bidirectional"))
      (node (ref "C13") (pin "N1") (pinfunction "P$2_N1") (pintype "bidirectional"))
      (node (ref "C13") (pin "N2") (pinfunction "P$2_N2") (pintype "bidirectional"))
      (node (ref "C13") (pin "T1") (pinfunction "P$2_T1") (pintype "bidirectional"))
      (node (ref "C13") (pin "T2") (pinfunction "P$2_T2") (pintype "bidirectional"))
      (node (ref "C14") (pin "C1") (pinfunction "P$2_C1") (pintype "bidirectional"))
      (node (ref "C14") (pin "C2") (pinfunction "P$2_C2") (pintype "bidirectional"))
      (node (ref "C14") (pin "F1") (pinfunction "P$2_F1") (pintype "bidirectional"))
      (node (ref "C14") (pin "F2") (pinfunction "P$2_F2") (pintype "bidirectional"))
      (node (ref "C14") (pin "N1") (pinfunction "P$2_N1") (pintype "bidirectional"))
      (node (ref "C14") (pin "N2") (pinfunction "P$2_N2") (pintype "bidirectional"))
      (node (ref "C14") (pin "T1") (pinfunction "P$2_T1") (pintype "bidirectional"))
      (node (ref "C14") (pin "T2") (pinfunction "P$2_T2") (pintype "bidirectional"))
      (node (ref "C17") (pin "C1") (pinfunction "D_C1") (pintype "input"))
      (node (ref "C17") (pin "E2") (pinfunction "D_E2") (pintype "input"))
      (node (ref "C17") (pin "J1") (pinfunction "D_J1") (pintype "input"))
      (node (ref "C17") (pin "M2") (pinfunction "D_M2") (pintype "input"))
      (node (ref "C17") (pin "P1") (pinfunction "D_P1") (pintype "input"))
      (node (ref "C17") (pin "T2") (pinfunction "D_T2") (pintype "input"))
      (node (ref "D01") (pin "C1") (pinfunction "P$2_C1") (pintype "bidirectional"))
      (node (ref "D01") (pin "C2") (pinfunction "P$2_C2") (pintype "bidirectional"))
      (node (ref "D01") (pin "F1") (pinfunction "P$2_F1") (pintype "bidirectional"))
      (node (ref "D01") (pin "F2") (pinfunction "P$2_F2") (pintype "bidirectional"))
      (node (ref "D01") (pin "N1") (pinfunction "P$2_N1") (pintype "bidirectional"))
      (node (ref "D01") (pin "N2") (pinfunction "P$2_N2") (pintype "bidirectional"))
      (node (ref "D01") (pin "T1") (pinfunction "P$2_T1") (pintype "bidirectional"))
      (node (ref "D01") (pin "T2") (pinfunction "P$2_T2") (pintype "bidirectional"))
      (node (ref "D02") (pin "C1") (pinfunction "P$2_C1") (pintype "bidirectional"))
      (node (ref "D02") (pin "C2") (pinfunction "P$2_C2") (pintype "bidirectional"))
      (node (ref "D02") (pin "F1") (pinfunction "P$2_F1") (pintype "bidirectional"))
      (node (ref "D02") (pin "F2") (pinfunction "P$2_F2") (pintype "bidirectional"))
      (node (ref "D02") (pin "N1") (pinfunction "P$2_N1") (pintype "bidirectional"))
      (node (ref "D02") (pin "N2") (pinfunction "P$2_N2") (pintype "bidirectional"))
      (node (ref "D02") (pin "T1") (pinfunction "P$2_T1") (pintype "bidirectional"))
      (node (ref "D02") (pin "T2") (pinfunction "P$2_T2") (pintype "bidirectional"))
      (node (ref "D03") (pin "C1") (pinfunction "P$2_C1") (pintype "bidirectional"))
      (node (ref "D03") (pin "C2") (pinfunction "P$2_C2") (pintype "bidirectional"))
      (node (ref "D03") (pin "F1") (pinfunction "P$2_F1") (pintype "bidirectional"))
      (node (ref "D03") (pin "F2") (pinfunction "P$2_F2") (pintype "bidirectional"))
      (node (ref "D03") (pin "N1") (pinfunction "P$2_N1") (pintype "bidirectional"))
      (node (ref "D03") (pin "N2") (pinfunction "P$2_N2") (pintype "bidirectional"))
      (node (ref "D03") (pin "T1") (pinfunction "P$2_T1") (pintype "bidirectional"))
      (node (ref "D03") (pin "T2") (pinfunction "P$2_T2") (pintype "bidirectional"))
      (node (ref "D04") (pin "C1") (pinfunction "P$2_C1") (pintype "bidirectional"))
      (node (ref "D04") (pin "C2") (pinfunction "P$2_C2") (pintype "bidirectional"))
      (node (ref "D04") (pin "F1") (pinfunction "P$2_F1") (pintype "bidirectional"))
      (node (ref "D04") (pin "F2") (pinfunction "P$2_F2") (pintype "bidirectional"))
      (node (ref "D04") (pin "N1") (pinfunction "P$2_N1") (pintype "bidirectional"))
      (node (ref "D04") (pin "N2") (pinfunction "P$2_N2") (pintype "bidirectional"))
      (node (ref "D04") (pin "T1") (pinfunction "P$2_T1") (pintype "bidirectional"))
      (node (ref "D04") (pin "T2") (pinfunction "P$2_T2") (pintype "bidirectional"))
      (node (ref "D05") (pin "C1") (pinfunction "P$2_C1") (pintype "bidirectional"))
      (node (ref "D05") (pin "C2") (pinfunction "P$2_C2") (pintype "bidirectional"))
      (node (ref "D05") (pin "F1") (pinfunction "P$2_F1") (pintype "bidirectional"))
      (node (ref "D05") (pin "F2") (pinfunction "P$2_F2") (pintype "bidirectional"))
      (node (ref "D05") (pin "N1") (pinfunction "P$2_N1") (pintype "bidirectional"))
      (node (ref "D05") (pin "N2") (pinfunction "P$2_N2") (pintype "bidirectional"))
      (node (ref "D05") (pin "T1") (pinfunction "P$2_T1") (pintype "bidirectional"))
      (node (ref "D05") (pin "T2") (pinfunction "P$2_T2") (pintype "bidirectional"))
      (node (ref "D06") (pin "C1") (pinfunction "P$2_C1") (pintype "bidirectional"))
      (node (ref "D06") (pin "C2") (pinfunction "P$2_C2") (pintype "bidirectional"))
      (node (ref "D06") (pin "F1") (pinfunction "P$2_F1") (pintype "bidirectional"))
      (node (ref "D06") (pin "F2") (pinfunction "P$2_F2") (pintype "bidirectional"))
      (node (ref "D06") (pin "N1") (pinfunction "P$2_N1") (pintype "bidirectional"))
      (node (ref "D06") (pin "N2") (pinfunction "P$2_N2") (pintype "bidirectional"))
      (node (ref "D06") (pin "T1") (pinfunction "P$2_T1") (pintype "bidirectional"))
      (node (ref "D06") (pin "T2") (pinfunction "P$2_T2") (pintype "bidirectional"))
      (node (ref "D07") (pin "C1") (pinfunction "P$2_C1") (pintype "bidirectional"))
      (node (ref "D07") (pin "C2") (pinfunction "P$2_C2") (pintype "bidirectional"))
      (node (ref "D07") (pin "F1") (pinfunction "P$2_F1") (pintype "bidirectional"))
      (node (ref "D07") (pin "F2") (pinfunction "P$2_F2") (pintype "bidirectional"))
      (node (ref "D07") (pin "N1") (pinfunction "P$2_N1") (pintype "bidirectional"))
      (node (ref "D07") (pin "N2") (pinfunction "P$2_N2") (pintype "bidirectional"))
      (node (ref "D07") (pin "T1") (pinfunction "P$2_T1") (pintype "bidirectional"))
      (node (ref "D07") (pin "T2") (pinfunction "P$2_T2") (pintype "bidirectional"))
      (node (ref "D08") (pin "C1") (pinfunction "P$2_C1") (pintype "bidirectional"))
      (node (ref "D08") (pin "C2") (pinfunction "P$2_C2") (pintype "bidirectional"))
      (node (ref "D08") (pin "F1") (pinfunction "P$2_F1") (pintype "bidirectional"))
      (node (ref "D08") (pin "F2") (pinfunction "P$2_F2") (pintype "bidirectional"))
      (node (ref "D08") (pin "N1") (pinfunction "P$2_N1") (pintype "bidirectional"))
      (node (ref "D08") (pin "N2") (pinfunction "P$2_N2") (pintype "bidirectional"))
      (node (ref "D08") (pin "T1") (pinfunction "P$2_T1") (pintype "bidirectional"))
      (node (ref "D08") (pin "T2") (pinfunction "P$2_T2") (pintype "bidirectional"))
      (node (ref "D09") (pin "C1") (pinfunction "P$2_C1") (pintype "bidirectional"))
      (node (ref "D09") (pin "C2") (pinfunction "P$2_C2") (pintype "bidirectional"))
      (node (ref "D09") (pin "F1") (pinfunction "P$2_F1") (pintype "bidirectional"))
      (node (ref "D09") (pin "F2") (pinfunction "P$2_F2") (pintype "bidirectional"))
      (node (ref "D09") (pin "N1") (pinfunction "P$2_N1") (pintype "bidirectional"))
      (node (ref "D09") (pin "N2") (pinfunction "P$2_N2") (pintype "bidirectional"))
      (node (ref "D09") (pin "T1") (pinfunction "P$2_T1") (pintype "bidirectional"))
      (node (ref "D09") (pin "T2") (pinfunction "P$2_T2") (pintype "bidirectional"))
      (node (ref "D10") (pin "C1") (pinfunction "P$2_C1") (pintype "bidirectional"))
      (node (ref "D10") (pin "C2") (pinfunction "P$2_C2") (pintype "bidirectional"))
      (node (ref "D10") (pin "F1") (pinfunction "P$2_F1") (pintype "bidirectional"))
      (node (ref "D10") (pin "F2") (pinfunction "P$2_F2") (pintype "bidirectional"))
      (node (ref "D10") (pin "N1") (pinfunction "P$2_N1") (pintype "bidirectional"))
      (node (ref "D10") (pin "N2") (pinfunction "P$2_N2") (pintype "bidirectional"))
      (node (ref "D10") (pin "T1") (pinfunction "P$2_T1") (pintype "bidirectional"))
      (node (ref "D10") (pin "T2") (pinfunction "P$2_T2") (pintype "bidirectional"))
      (node (ref "D11") (pin "C1") (pinfunction "P$2_C1") (pintype "bidirectional"))
      (node (ref "D11") (pin "C2") (pinfunction "P$2_C2") (pintype "bidirectional"))
      (node (ref "D11") (pin "F1") (pinfunction "P$2_F1") (pintype "bidirectional"))
      (node (ref "D11") (pin "F2") (pinfunction "P$2_F2") (pintype "bidirectional"))
      (node (ref "D11") (pin "N1") (pinfunction "P$2_N1") (pintype "bidirectional"))
      (node (ref "D11") (pin "N2") (pinfunction "P$2_N2") (pintype "bidirectional"))
      (node (ref "D11") (pin "T1") (pinfunction "P$2_T1") (pintype "bidirectional"))
      (node (ref "D11") (pin "T2") (pinfunction "P$2_T2") (pintype "bidirectional"))
      (node (ref "D12") (pin "C1") (pinfunction "P$2_C1") (pintype "bidirectional"))
      (node (ref "D12") (pin "C2") (pinfunction "P$2_C2") (pintype "bidirectional"))
      (node (ref "D12") (pin "F1") (pinfunction "P$2_F1") (pintype "bidirectional"))
      (node (ref "D12") (pin "F2") (pinfunction "P$2_F2") (pintype "bidirectional"))
      (node (ref "D12") (pin "N1") (pinfunction "P$2_N1") (pintype "bidirectional"))
      (node (ref "D12") (pin "N2") (pinfunction "P$2_N2") (pintype "bidirectional"))
      (node (ref "D12") (pin "T1") (pinfunction "P$2_T1") (pintype "bidirectional"))
      (node (ref "D12") (pin "T2") (pinfunction "P$2_T2") (pintype "bidirectional"))
      (node (ref "D13") (pin "C1") (pinfunction "P$2_C1") (pintype "bidirectional"))
      (node (ref "D13") (pin "C2") (pinfunction "P$2_C2") (pintype "bidirectional"))
      (node (ref "D13") (pin "F1") (pinfunction "P$2_F1") (pintype "bidirectional"))
      (node (ref "D13") (pin "F2") (pinfunction "P$2_F2") (pintype "bidirectional"))
      (node (ref "D13") (pin "N1") (pinfunction "P$2_N1") (pintype "bidirectional"))
      (node (ref "D13") (pin "N2") (pinfunction "P$2_N2") (pintype "bidirectional"))
      (node (ref "D13") (pin "T1") (pinfunction "P$2_T1") (pintype "bidirectional"))
      (node (ref "D13") (pin "T2") (pinfunction "P$2_T2") (pintype "bidirectional"))
      (node (ref "D14") (pin "C1") (pinfunction "P$2_C1") (pintype "bidirectional"))
      (node (ref "D14") (pin "C2") (pinfunction "P$2_C2") (pintype "bidirectional"))
      (node (ref "D14") (pin "F1") (pinfunction "P$2_F1") (pintype "bidirectional"))
      (node (ref "D14") (pin "F2") (pinfunction "P$2_F2") (pintype "bidirectional"))
      (node (ref "D14") (pin "N1") (pinfunction "P$2_N1") (pintype "bidirectional"))
      (node (ref "D14") (pin "N2") (pinfunction "P$2_N2") (pintype "bidirectional"))
      (node (ref "D14") (pin "T1") (pinfunction "P$2_T1") (pintype "bidirectional"))
      (node (ref "D14") (pin "T2") (pinfunction "P$2_T2") (pintype "bidirectional"))
      (node (ref "D19") (pin "F1") (pinfunction "L3_F1") (pintype "bidirectional"))
      (node (ref "GND") (pin "1") (pinfunction "P_1") (pintype "passive"))
    )
    (net (code "110") (name "Net-(A01A-P$2)") (class "Default")
      (node (ref "A01") (pin "A1") (pinfunction "P$2_A1") (pintype "bidirectional"))
      (node (ref "A02") (pin "A1") (pinfunction "P$2_A1") (pintype "bidirectional"))
      (node (ref "A03") (pin "A1") (pinfunction "P$2_A1") (pintype "bidirectional"))
      (node (ref "A04") (pin "A1") (pinfunction "P$2_A1") (pintype "bidirectional"))
      (node (ref "A05") (pin "A1") (pinfunction "P$2_A1") (pintype "bidirectional"))
      (node (ref "A06") (pin "A1") (pinfunction "P$2_A1") (pintype "bidirectional"))
      (node (ref "A07") (pin "A1") (pinfunction "P$2_A1") (pintype "bidirectional"))
      (node (ref "A08") (pin "A1") (pinfunction "P$2_A1") (pintype "bidirectional"))
      (node (ref "A09") (pin "A1") (pinfunction "P$2_A1") (pintype "bidirectional"))
      (node (ref "A10") (pin "A1") (pinfunction "P$2_A1") (pintype "bidirectional"))
      (node (ref "A11") (pin "A1") (pinfunction "P$2_A1") (pintype "bidirectional"))
      (node (ref "A12") (pin "A1") (pinfunction "P$2_A1") (pintype "bidirectional"))
      (node (ref "A13") (pin "A1") (pinfunction "P$2_A1") (pintype "bidirectional"))
      (node (ref "A14") (pin "A1") (pinfunction "P$2_A1") (pintype "bidirectional"))
    )
    (net (code "111") (name "Net-(A01AA-P$2)") (class "Default")
      (node (ref "A01") (pin "R1") (pinfunction "P$2_R1") (pintype "bidirectional"))
      (node (ref "A02") (pin "R1") (pinfunction "P$2_R1") (pintype "bidirectional"))
      (node (ref "A03") (pin "R1") (pinfunction "P$2_R1") (pintype "bidirectional"))
      (node (ref "A04") (pin "R1") (pinfunction "P$2_R1") (pintype "bidirectional"))
      (node (ref "A05") (pin "R1") (pinfunction "P$2_R1") (pintype "bidirectional"))
      (node (ref "A06") (pin "R1") (pinfunction "P$2_R1") (pintype "bidirectional"))
      (node (ref "A07") (pin "R1") (pinfunction "P$2_R1") (pintype "bidirectional"))
      (node (ref "A08") (pin "R1") (pinfunction "P$2_R1") (pintype "bidirectional"))
      (node (ref "A09") (pin "R1") (pinfunction "P$2_R1") (pintype "bidirectional"))
      (node (ref "A10") (pin "R1") (pinfunction "P$2_R1") (pintype "bidirectional"))
      (node (ref "A11") (pin "R1") (pinfunction "P$2_R1") (pintype "bidirectional"))
      (node (ref "A12") (pin "R1") (pinfunction "P$2_R1") (pintype "bidirectional"))
      (node (ref "A13") (pin "R1") (pinfunction "P$2_R1") (pintype "bidirectional"))
      (node (ref "A14") (pin "R1") (pinfunction "P$2_R1") (pintype "bidirectional"))
    )
    (net (code "112") (name "Net-(A01AC-P$2)") (class "Default")
      (node (ref "A01") (pin "S1") (pinfunction "P$2_S1") (pintype "bidirectional"))
      (node (ref "A02") (pin "S1") (pinfunction "P$2_S1") (pintype "bidirectional"))
      (node (ref "A03") (pin "S1") (pinfunction "P$2_S1") (pintype "bidirectional"))
      (node (ref "A04") (pin "S1") (pinfunction "P$2_S1") (pintype "bidirectional"))
      (node (ref "A05") (pin "S1") (pinfunction "P$2_S1") (pintype "bidirectional"))
      (node (ref "A06") (pin "S1") (pinfunction "P$2_S1") (pintype "bidirectional"))
      (node (ref "A07") (pin "S1") (pinfunction "P$2_S1") (pintype "bidirectional"))
      (node (ref "A08") (pin "S1") (pinfunction "P$2_S1") (pintype "bidirectional"))
      (node (ref "A09") (pin "S1") (pinfunction "P$2_S1") (pintype "bidirectional"))
      (node (ref "A10") (pin "S1") (pinfunction "P$2_S1") (pintype "bidirectional"))
      (node (ref "A11") (pin "S1") (pinfunction "P$2_S1") (pintype "bidirectional"))
      (node (ref "A12") (pin "S1") (pinfunction "P$2_S1") (pintype "bidirectional"))
      (node (ref "A13") (pin "S1") (pinfunction "P$2_S1") (pintype "bidirectional"))
      (node (ref "A14") (pin "S1") (pinfunction "P$2_S1") (pintype "bidirectional"))
    )
    (net (code "113") (name "Net-(A01AG-P$2)") (class "Default")
      (node (ref "A01") (pin "U1") (pinfunction "P$2_U1") (pintype "bidirectional"))
      (node (ref "A02") (pin "U1") (pinfunction "P$2_U1") (pintype "bidirectional"))
      (node (ref "A03") (pin "U1") (pinfunction "P$2_U1") (pintype "bidirectional"))
      (node (ref "A04") (pin "U1") (pinfunction "P$2_U1") (pintype "bidirectional"))
      (node (ref "A05") (pin "U1") (pinfunction "P$2_U1") (pintype "bidirectional"))
      (node (ref "A06") (pin "U1") (pinfunction "P$2_U1") (pintype "bidirectional"))
      (node (ref "A07") (pin "U1") (pinfunction "P$2_U1") (pintype "bidirectional"))
      (node (ref "A08") (pin "U1") (pinfunction "P$2_U1") (pintype "bidirectional"))
      (node (ref "A09") (pin "U1") (pinfunction "P$2_U1") (pintype "bidirectional"))
      (node (ref "A10") (pin "U1") (pinfunction "P$2_U1") (pintype "bidirectional"))
      (node (ref "A11") (pin "U1") (pinfunction "P$2_U1") (pintype "bidirectional"))
      (node (ref "A12") (pin "U1") (pinfunction "P$2_U1") (pintype "bidirectional"))
      (node (ref "A13") (pin "U1") (pinfunction "P$2_U1") (pintype "bidirectional"))
      (node (ref "A14") (pin "U1") (pinfunction "P$2_U1") (pintype "bidirectional"))
    )
    (net (code "114") (name "Net-(A01AI-P$2)") (class "Default")
      (node (ref "A01") (pin "V1") (pinfunction "P$2_V1") (pintype "bidirectional"))
      (node (ref "A02") (pin "V1") (pinfunction "P$2_V1") (pintype "bidirectional"))
      (node (ref "A03") (pin "V1") (pinfunction "P$2_V1") (pintype "bidirectional"))
      (node (ref "A04") (pin "V1") (pinfunction "P$2_V1") (pintype "bidirectional"))
      (node (ref "A05") (pin "V1") (pinfunction "P$2_V1") (pintype "bidirectional"))
      (node (ref "A06") (pin "V1") (pinfunction "P$2_V1") (pintype "bidirectional"))
      (node (ref "A07") (pin "V1") (pinfunction "P$2_V1") (pintype "bidirectional"))
      (node (ref "A08") (pin "V1") (pinfunction "P$2_V1") (pintype "bidirectional"))
      (node (ref "A09") (pin "V1") (pinfunction "P$2_V1") (pintype "bidirectional"))
      (node (ref "A10") (pin "V1") (pinfunction "P$2_V1") (pintype "bidirectional"))
      (node (ref "A11") (pin "V1") (pinfunction "P$2_V1") (pintype "bidirectional"))
      (node (ref "A12") (pin "V1") (pinfunction "P$2_V1") (pintype "bidirectional"))
      (node (ref "A13") (pin "V1") (pinfunction "P$2_V1") (pintype "bidirectional"))
      (node (ref "A14") (pin "V1") (pinfunction "P$2_V1") (pintype "bidirectional"))
    )
    (net (code "115") (name "Net-(A01AJ-P$2)") (class "Default")
      (node (ref "A01") (pin "V2") (pinfunction "P$2_V2") (pintype "bidirectional"))
      (node (ref "A02") (pin "V2") (pinfunction "P$2_V2") (pintype "bidirectional"))
      (node (ref "A03") (pin "V2") (pinfunction "P$2_V2") (pintype "bidirectional"))
      (node (ref "A04") (pin "V2") (pinfunction "P$2_V2") (pintype "bidirectional"))
      (node (ref "A05") (pin "V2") (pinfunction "P$2_V2") (pintype "bidirectional"))
      (node (ref "A06") (pin "V2") (pinfunction "P$2_V2") (pintype "bidirectional"))
      (node (ref "A07") (pin "V2") (pinfunction "P$2_V2") (pintype "bidirectional"))
      (node (ref "A08") (pin "V2") (pinfunction "P$2_V2") (pintype "bidirectional"))
      (node (ref "A09") (pin "V2") (pinfunction "P$2_V2") (pintype "bidirectional"))
      (node (ref "A10") (pin "V2") (pinfunction "P$2_V2") (pintype "bidirectional"))
      (node (ref "A11") (pin "V2") (pinfunction "P$2_V2") (pintype "bidirectional"))
      (node (ref "A12") (pin "V2") (pinfunction "P$2_V2") (pintype "bidirectional"))
      (node (ref "A13") (pin "V2") (pinfunction "P$2_V2") (pintype "bidirectional"))
      (node (ref "A14") (pin "V2") (pinfunction "P$2_V2") (pintype "bidirectional"))
    )
    (net (code "116") (name "Net-(A01C-P$2)") (class "Default")
      (node (ref "A01") (pin "B1") (pinfunction "P$2_B1") (pintype "bidirectional"))
      (node (ref "A02") (pin "B1") (pinfunction "P$2_B1") (pintype "bidirectional"))
      (node (ref "A03") (pin "B1") (pinfunction "P$2_B1") (pintype "bidirectional"))
      (node (ref "A04") (pin "B1") (pinfunction "P$2_B1") (pintype "bidirectional"))
      (node (ref "A05") (pin "B1") (pinfunction "P$2_B1") (pintype "bidirectional"))
      (node (ref "A06") (pin "B1") (pinfunction "P$2_B1") (pintype "bidirectional"))
      (node (ref "A07") (pin "B1") (pinfunction "P$2_B1") (pintype "bidirectional"))
      (node (ref "A08") (pin "B1") (pinfunction "P$2_B1") (pintype "bidirectional"))
      (node (ref "A09") (pin "B1") (pinfunction "P$2_B1") (pintype "bidirectional"))
      (node (ref "A10") (pin "B1") (pinfunction "P$2_B1") (pintype "bidirectional"))
      (node (ref "A11") (pin "B1") (pinfunction "P$2_B1") (pintype "bidirectional"))
      (node (ref "A12") (pin "B1") (pinfunction "P$2_B1") (pintype "bidirectional"))
      (node (ref "A13") (pin "B1") (pinfunction "P$2_B1") (pintype "bidirectional"))
      (node (ref "A14") (pin "B1") (pinfunction "P$2_B1") (pintype "bidirectional"))
    )
    (net (code "117") (name "Net-(A01P-P$2)") (class "Default")
      (node (ref "A01") (pin "J2") (pinfunction "P$2_J2") (pintype "bidirectional"))
      (node (ref "A02") (pin "J2") (pinfunction "P$2_J2") (pintype "bidirectional"))
      (node (ref "A03") (pin "J2") (pinfunction "P$2_J2") (pintype "bidirectional"))
      (node (ref "A04") (pin "J2") (pinfunction "P$2_J2") (pintype "bidirectional"))
      (node (ref "A05") (pin "J2") (pinfunction "P$2_J2") (pintype "bidirectional"))
      (node (ref "A06") (pin "J2") (pinfunction "P$2_J2") (pintype "bidirectional"))
      (node (ref "A07") (pin "J2") (pinfunction "P$2_J2") (pintype "bidirectional"))
      (node (ref "A08") (pin "J2") (pinfunction "P$2_J2") (pintype "bidirectional"))
      (node (ref "A09") (pin "J2") (pinfunction "P$2_J2") (pintype "bidirectional"))
      (node (ref "A10") (pin "J2") (pinfunction "P$2_J2") (pintype "bidirectional"))
      (node (ref "A11") (pin "J2") (pinfunction "P$2_J2") (pintype "bidirectional"))
      (node (ref "A12") (pin "J2") (pinfunction "P$2_J2") (pintype "bidirectional"))
      (node (ref "A13") (pin "J2") (pinfunction "P$2_J2") (pintype "bidirectional"))
      (node (ref "A14") (pin "J2") (pinfunction "P$2_J2") (pintype "bidirectional"))
    )
    (net (code "118") (name "Net-(A15A-IN4)") (class "Default")
      (node (ref "A15") (pin "D1") (pinfunction "IN4_D1") (pintype "input"))
      (node (ref "C17") (pin "J2") (pinfunction "0_J2") (pintype "output"))
    )
    (net (code "119") (name "Net-(A15D-IN4)") (class "Default")
      (node (ref "A15") (pin "H2") (pinfunction "IN4_H2") (pintype "input"))
      (node (ref "C17") (pin "U1") (pinfunction "0_U1") (pintype "output"))
    )
    (net (code "120") (name "Net-(A15E-IN4)") (class "Default")
      (node (ref "A15") (pin "K1") (pinfunction "IN4_K1") (pintype "input"))
      (node (ref "C17") (pin "M1") (pinfunction "0_M1") (pintype "output"))
    )
    (net (code "121") (name "Net-(A15F-IN4)") (class "Default")
      (node (ref "A15") (pin "N2") (pinfunction "IN4_N2") (pintype "input"))
      (node (ref "C17") (pin "R2") (pinfunction "0_R2") (pintype "output"))
    )
    (net (code "122") (name "Net-(A15G-IN4)") (class "Default")
      (node (ref "A15") (pin "R1") (pinfunction "IN4_R1") (pintype "input"))
      (node (ref "C17") (pin "V1") (pinfunction "0_V1") (pintype "output"))
    )
    (net (code "123") (name "Net-(B01A-P$2)") (class "Default")
      (node (ref "B01") (pin "A1") (pinfunction "P$2_A1") (pintype "bidirectional"))
      (node (ref "B02") (pin "A1") (pinfunction "P$2_A1") (pintype "bidirectional"))
      (node (ref "B03") (pin "A1") (pinfunction "P$2_A1") (pintype "bidirectional"))
      (node (ref "B04") (pin "A1") (pinfunction "P$2_A1") (pintype "bidirectional"))
      (node (ref "B05") (pin "A1") (pinfunction "P$2_A1") (pintype "bidirectional"))
      (node (ref "B06") (pin "A1") (pinfunction "P$2_A1") (pintype "bidirectional"))
      (node (ref "B07") (pin "A1") (pinfunction "P$2_A1") (pintype "bidirectional"))
      (node (ref "B08") (pin "A1") (pinfunction "P$2_A1") (pintype "bidirectional"))
      (node (ref "B09") (pin "A1") (pinfunction "P$2_A1") (pintype "bidirectional"))
      (node (ref "B10") (pin "A1") (pinfunction "P$2_A1") (pintype "bidirectional"))
      (node (ref "B11") (pin "A1") (pinfunction "P$2_A1") (pintype "bidirectional"))
      (node (ref "B12") (pin "A1") (pinfunction "P$2_A1") (pintype "bidirectional"))
      (node (ref "B13") (pin "A1") (pinfunction "P$2_A1") (pintype "bidirectional"))
      (node (ref "B14") (pin "A1") (pinfunction "P$2_A1") (pintype "bidirectional"))
    )
    (net (code "124") (name "Net-(B01AA-P$2)") (class "Default")
      (node (ref "B01") (pin "R1") (pinfunction "P$2_R1") (pintype "bidirectional"))
      (node (ref "B02") (pin "R1") (pinfunction "P$2_R1") (pintype "bidirectional"))
      (node (ref "B03") (pin "R1") (pinfunction "P$2_R1") (pintype "bidirectional"))
      (node (ref "B04") (pin "R1") (pinfunction "P$2_R1") (pintype "bidirectional"))
      (node (ref "B05") (pin "R1") (pinfunction "P$2_R1") (pintype "bidirectional"))
      (node (ref "B06") (pin "R1") (pinfunction "P$2_R1") (pintype "bidirectional"))
      (node (ref "B07") (pin "R1") (pinfunction "P$2_R1") (pintype "bidirectional"))
      (node (ref "B08") (pin "R1") (pinfunction "P$2_R1") (pintype "bidirectional"))
      (node (ref "B09") (pin "R1") (pinfunction "P$2_R1") (pintype "bidirectional"))
      (node (ref "B10") (pin "R1") (pinfunction "P$2_R1") (pintype "bidirectional"))
      (node (ref "B11") (pin "R1") (pinfunction "P$2_R1") (pintype "bidirectional"))
      (node (ref "B12") (pin "R1") (pinfunction "P$2_R1") (pintype "bidirectional"))
      (node (ref "B13") (pin "R1") (pinfunction "P$2_R1") (pintype "bidirectional"))
      (node (ref "B14") (pin "R1") (pinfunction "P$2_R1") (pintype "bidirectional"))
    )
    (net (code "125") (name "Net-(B01AB-P$2)") (class "Default")
      (node (ref "B01") (pin "R2") (pinfunction "P$2_R2") (pintype "bidirectional"))
      (node (ref "B02") (pin "R2") (pinfunction "P$2_R2") (pintype "bidirectional"))
      (node (ref "B03") (pin "R2") (pinfunction "P$2_R2") (pintype "bidirectional"))
      (node (ref "B04") (pin "R2") (pinfunction "P$2_R2") (pintype "bidirectional"))
      (node (ref "B05") (pin "R2") (pinfunction "P$2_R2") (pintype "bidirectional"))
      (node (ref "B06") (pin "R2") (pinfunction "P$2_R2") (pintype "bidirectional"))
      (node (ref "B07") (pin "R2") (pinfunction "P$2_R2") (pintype "bidirectional"))
      (node (ref "B08") (pin "R2") (pinfunction "P$2_R2") (pintype "bidirectional"))
      (node (ref "B09") (pin "R2") (pinfunction "P$2_R2") (pintype "bidirectional"))
      (node (ref "B10") (pin "R2") (pinfunction "P$2_R2") (pintype "bidirectional"))
      (node (ref "B11") (pin "R2") (pinfunction "P$2_R2") (pintype "bidirectional"))
      (node (ref "B12") (pin "R2") (pinfunction "P$2_R2") (pintype "bidirectional"))
      (node (ref "B13") (pin "R2") (pinfunction "P$2_R2") (pintype "bidirectional"))
      (node (ref "B14") (pin "R2") (pinfunction "P$2_R2") (pintype "bidirectional"))
    )
    (net (code "126") (name "Net-(B01AC-P$2)") (class "Default")
      (node (ref "B01") (pin "S1") (pinfunction "P$2_S1") (pintype "bidirectional"))
      (node (ref "B02") (pin "S1") (pinfunction "P$2_S1") (pintype "bidirectional"))
      (node (ref "B03") (pin "S1") (pinfunction "P$2_S1") (pintype "bidirectional"))
      (node (ref "B04") (pin "S1") (pinfunction "P$2_S1") (pintype "bidirectional"))
      (node (ref "B05") (pin "S1") (pinfunction "P$2_S1") (pintype "bidirectional"))
      (node (ref "B06") (pin "S1") (pinfunction "P$2_S1") (pintype "bidirectional"))
      (node (ref "B07") (pin "S1") (pinfunction "P$2_S1") (pintype "bidirectional"))
      (node (ref "B08") (pin "S1") (pinfunction "P$2_S1") (pintype "bidirectional"))
      (node (ref "B09") (pin "S1") (pinfunction "P$2_S1") (pintype "bidirectional"))
      (node (ref "B10") (pin "S1") (pinfunction "P$2_S1") (pintype "bidirectional"))
      (node (ref "B11") (pin "S1") (pinfunction "P$2_S1") (pintype "bidirectional"))
      (node (ref "B12") (pin "S1") (pinfunction "P$2_S1") (pintype "bidirectional"))
      (node (ref "B13") (pin "S1") (pinfunction "P$2_S1") (pintype "bidirectional"))
      (node (ref "B14") (pin "S1") (pinfunction "P$2_S1") (pintype "bidirectional"))
    )
    (net (code "127") (name "Net-(B01AD-P$2)") (class "Default")
      (node (ref "B01") (pin "S2") (pinfunction "P$2_S2") (pintype "bidirectional"))
      (node (ref "B02") (pin "S2") (pinfunction "P$2_S2") (pintype "bidirectional"))
      (node (ref "B03") (pin "S2") (pinfunction "P$2_S2") (pintype "bidirectional"))
      (node (ref "B04") (pin "S2") (pinfunction "P$2_S2") (pintype "bidirectional"))
      (node (ref "B05") (pin "S2") (pinfunction "P$2_S2") (pintype "bidirectional"))
      (node (ref "B06") (pin "S2") (pinfunction "P$2_S2") (pintype "bidirectional"))
      (node (ref "B07") (pin "S2") (pinfunction "P$2_S2") (pintype "bidirectional"))
      (node (ref "B08") (pin "S2") (pinfunction "P$2_S2") (pintype "bidirectional"))
      (node (ref "B09") (pin "S2") (pinfunction "P$2_S2") (pintype "bidirectional"))
      (node (ref "B10") (pin "S2") (pinfunction "P$2_S2") (pintype "bidirectional"))
      (node (ref "B11") (pin "S2") (pinfunction "P$2_S2") (pintype "bidirectional"))
      (node (ref "B12") (pin "S2") (pinfunction "P$2_S2") (pintype "bidirectional"))
      (node (ref "B13") (pin "S2") (pinfunction "P$2_S2") (pintype "bidirectional"))
      (node (ref "B14") (pin "S2") (pinfunction "P$2_S2") (pintype "bidirectional"))
    )
    (net (code "128") (name "Net-(B01AG-P$2)") (class "Default")
      (node (ref "B01") (pin "U1") (pinfunction "P$2_U1") (pintype "bidirectional"))
      (node (ref "B02") (pin "U1") (pinfunction "P$2_U1") (pintype "bidirectional"))
      (node (ref "B03") (pin "U1") (pinfunction "P$2_U1") (pintype "bidirectional"))
      (node (ref "B04") (pin "U1") (pinfunction "P$2_U1") (pintype "bidirectional"))
      (node (ref "B05") (pin "U1") (pinfunction "P$2_U1") (pintype "bidirectional"))
      (node (ref "B06") (pin "U1") (pinfunction "P$2_U1") (pintype "bidirectional"))
      (node (ref "B07") (pin "U1") (pinfunction "P$2_U1") (pintype "bidirectional"))
      (node (ref "B08") (pin "U1") (pinfunction "P$2_U1") (pintype "bidirectional"))
      (node (ref "B09") (pin "U1") (pinfunction "P$2_U1") (pintype "bidirectional"))
      (node (ref "B10") (pin "U1") (pinfunction "P$2_U1") (pintype "bidirectional"))
      (node (ref "B11") (pin "U1") (pinfunction "P$2_U1") (pintype "bidirectional"))
      (node (ref "B12") (pin "U1") (pinfunction "P$2_U1") (pintype "bidirectional"))
      (node (ref "B13") (pin "U1") (pinfunction "P$2_U1") (pintype "bidirectional"))
      (node (ref "B14") (pin "U1") (pinfunction "P$2_U1") (pintype "bidirectional"))
    )
    (net (code "129") (name "Net-(B01AH-P$2)") (class "Default")
      (node (ref "B01") (pin "U2") (pinfunction "P$2_U2") (pintype "bidirectional"))
      (node (ref "B02") (pin "U2") (pinfunction "P$2_U2") (pintype "bidirectional"))
      (node (ref "B03") (pin "U2") (pinfunction "P$2_U2") (pintype "bidirectional"))
      (node (ref "B04") (pin "U2") (pinfunction "P$2_U2") (pintype "bidirectional"))
      (node (ref "B05") (pin "U2") (pinfunction "P$2_U2") (pintype "bidirectional"))
      (node (ref "B06") (pin "U2") (pinfunction "P$2_U2") (pintype "bidirectional"))
      (node (ref "B07") (pin "U2") (pinfunction "P$2_U2") (pintype "bidirectional"))
      (node (ref "B08") (pin "U2") (pinfunction "P$2_U2") (pintype "bidirectional"))
      (node (ref "B09") (pin "U2") (pinfunction "P$2_U2") (pintype "bidirectional"))
      (node (ref "B10") (pin "U2") (pinfunction "P$2_U2") (pintype "bidirectional"))
      (node (ref "B11") (pin "U2") (pinfunction "P$2_U2") (pintype "bidirectional"))
      (node (ref "B12") (pin "U2") (pinfunction "P$2_U2") (pintype "bidirectional"))
      (node (ref "B13") (pin "U2") (pinfunction "P$2_U2") (pintype "bidirectional"))
      (node (ref "B14") (pin "U2") (pinfunction "P$2_U2") (pintype "bidirectional"))
    )
    (net (code "130") (name "Net-(B01AI-P$2)") (class "Default")
      (node (ref "B01") (pin "V1") (pinfunction "P$2_V1") (pintype "bidirectional"))
      (node (ref "B02") (pin "V1") (pinfunction "P$2_V1") (pintype "bidirectional"))
      (node (ref "B03") (pin "V1") (pinfunction "P$2_V1") (pintype "bidirectional"))
      (node (ref "B04") (pin "V1") (pinfunction "P$2_V1") (pintype "bidirectional"))
      (node (ref "B05") (pin "V1") (pinfunction "P$2_V1") (pintype "bidirectional"))
      (node (ref "B06") (pin "V1") (pinfunction "P$2_V1") (pintype "bidirectional"))
      (node (ref "B07") (pin "V1") (pinfunction "P$2_V1") (pintype "bidirectional"))
      (node (ref "B08") (pin "V1") (pinfunction "P$2_V1") (pintype "bidirectional"))
      (node (ref "B09") (pin "V1") (pinfunction "P$2_V1") (pintype "bidirectional"))
      (node (ref "B10") (pin "V1") (pinfunction "P$2_V1") (pintype "bidirectional"))
      (node (ref "B11") (pin "V1") (pinfunction "P$2_V1") (pintype "bidirectional"))
      (node (ref "B12") (pin "V1") (pinfunction "P$2_V1") (pintype "bidirectional"))
      (node (ref "B13") (pin "V1") (pinfunction "P$2_V1") (pintype "bidirectional"))
      (node (ref "B14") (pin "V1") (pinfunction "P$2_V1") (pintype "bidirectional"))
    )
    (net (code "131") (name "Net-(B01C-P$2)") (class "Default")
      (node (ref "B01") (pin "B1") (pinfunction "P$2_B1") (pintype "bidirectional"))
      (node (ref "B02") (pin "B1") (pinfunction "P$2_B1") (pintype "bidirectional"))
      (node (ref "B03") (pin "B1") (pinfunction "P$2_B1") (pintype "bidirectional"))
      (node (ref "B04") (pin "B1") (pinfunction "P$2_B1") (pintype "bidirectional"))
      (node (ref "B05") (pin "B1") (pinfunction "P$2_B1") (pintype "bidirectional"))
      (node (ref "B06") (pin "B1") (pinfunction "P$2_B1") (pintype "bidirectional"))
      (node (ref "B07") (pin "B1") (pinfunction "P$2_B1") (pintype "bidirectional"))
      (node (ref "B08") (pin "B1") (pinfunction "P$2_B1") (pintype "bidirectional"))
      (node (ref "B09") (pin "B1") (pinfunction "P$2_B1") (pintype "bidirectional"))
      (node (ref "B10") (pin "B1") (pinfunction "P$2_B1") (pintype "bidirectional"))
      (node (ref "B11") (pin "B1") (pinfunction "P$2_B1") (pintype "bidirectional"))
      (node (ref "B12") (pin "B1") (pinfunction "P$2_B1") (pintype "bidirectional"))
      (node (ref "B13") (pin "B1") (pinfunction "P$2_B1") (pintype "bidirectional"))
      (node (ref "B14") (pin "B1") (pinfunction "P$2_B1") (pintype "bidirectional"))
    )
    (net (code "132") (name "Net-(B01H-P$2)") (class "Default")
      (node (ref "B01") (pin "D2") (pinfunction "P$2_D2") (pintype "bidirectional"))
      (node (ref "B02") (pin "D2") (pinfunction "P$2_D2") (pintype "bidirectional"))
      (node (ref "B03") (pin "D2") (pinfunction "P$2_D2") (pintype "bidirectional"))
      (node (ref "B04") (pin "D2") (pinfunction "P$2_D2") (pintype "bidirectional"))
      (node (ref "B05") (pin "D2") (pinfunction "P$2_D2") (pintype "bidirectional"))
      (node (ref "B06") (pin "D2") (pinfunction "P$2_D2") (pintype "bidirectional"))
      (node (ref "B07") (pin "D2") (pinfunction "P$2_D2") (pintype "bidirectional"))
      (node (ref "B08") (pin "D2") (pinfunction "P$2_D2") (pintype "bidirectional"))
      (node (ref "B09") (pin "D2") (pinfunction "P$2_D2") (pintype "bidirectional"))
      (node (ref "B10") (pin "D2") (pinfunction "P$2_D2") (pintype "bidirectional"))
      (node (ref "B11") (pin "D2") (pinfunction "P$2_D2") (pintype "bidirectional"))
      (node (ref "B12") (pin "D2") (pinfunction "P$2_D2") (pintype "bidirectional"))
      (node (ref "B13") (pin "D2") (pinfunction "P$2_D2") (pintype "bidirectional"))
      (node (ref "B14") (pin "D2") (pinfunction "P$2_D2") (pintype "bidirectional"))
    )
    (net (code "133") (name "Net-(B01J-P$2)") (class "Default")
      (node (ref "B01") (pin "E2") (pinfunction "P$2_E2") (pintype "bidirectional"))
      (node (ref "B02") (pin "E2") (pinfunction "P$2_E2") (pintype "bidirectional"))
      (node (ref "B03") (pin "E2") (pinfunction "P$2_E2") (pintype "bidirectional"))
      (node (ref "B04") (pin "E2") (pinfunction "P$2_E2") (pintype "bidirectional"))
      (node (ref "B05") (pin "E2") (pinfunction "P$2_E2") (pintype "bidirectional"))
      (node (ref "B06") (pin "E2") (pinfunction "P$2_E2") (pintype "bidirectional"))
      (node (ref "B07") (pin "E2") (pinfunction "P$2_E2") (pintype "bidirectional"))
      (node (ref "B08") (pin "E2") (pinfunction "P$2_E2") (pintype "bidirectional"))
      (node (ref "B09") (pin "E2") (pinfunction "P$2_E2") (pintype "bidirectional"))
      (node (ref "B10") (pin "E2") (pinfunction "P$2_E2") (pintype "bidirectional"))
      (node (ref "B11") (pin "E2") (pinfunction "P$2_E2") (pintype "bidirectional"))
      (node (ref "B12") (pin "E2") (pinfunction "P$2_E2") (pintype "bidirectional"))
      (node (ref "B13") (pin "E2") (pinfunction "P$2_E2") (pintype "bidirectional"))
      (node (ref "B14") (pin "E2") (pinfunction "P$2_E2") (pintype "bidirectional"))
    )
    (net (code "134") (name "Net-(B01N-P$2)") (class "Default")
      (node (ref "B01") (pin "H2") (pinfunction "P$2_H2") (pintype "bidirectional"))
      (node (ref "B02") (pin "H2") (pinfunction "P$2_H2") (pintype "bidirectional"))
      (node (ref "B03") (pin "H2") (pinfunction "P$2_H2") (pintype "bidirectional"))
      (node (ref "B04") (pin "H2") (pinfunction "P$2_H2") (pintype "bidirectional"))
      (node (ref "B05") (pin "H2") (pinfunction "P$2_H2") (pintype "bidirectional"))
      (node (ref "B06") (pin "H2") (pinfunction "P$2_H2") (pintype "bidirectional"))
      (node (ref "B07") (pin "H2") (pinfunction "P$2_H2") (pintype "bidirectional"))
      (node (ref "B08") (pin "H2") (pinfunction "P$2_H2") (pintype "bidirectional"))
      (node (ref "B09") (pin "H2") (pinfunction "P$2_H2") (pintype "bidirectional"))
      (node (ref "B10") (pin "H2") (pinfunction "P$2_H2") (pintype "bidirectional"))
      (node (ref "B11") (pin "H2") (pinfunction "P$2_H2") (pintype "bidirectional"))
      (node (ref "B12") (pin "H2") (pinfunction "P$2_H2") (pintype "bidirectional"))
      (node (ref "B13") (pin "H2") (pinfunction "P$2_H2") (pintype "bidirectional"))
      (node (ref "B14") (pin "H2") (pinfunction "P$2_H2") (pintype "bidirectional"))
    )
    (net (code "135") (name "Net-(B01P-P$2)") (class "Default")
      (node (ref "B01") (pin "J2") (pinfunction "P$2_J2") (pintype "bidirectional"))
      (node (ref "B02") (pin "J2") (pinfunction "P$2_J2") (pintype "bidirectional"))
      (node (ref "B03") (pin "J2") (pinfunction "P$2_J2") (pintype "bidirectional"))
      (node (ref "B04") (pin "J2") (pinfunction "P$2_J2") (pintype "bidirectional"))
      (node (ref "B05") (pin "J2") (pinfunction "P$2_J2") (pintype "bidirectional"))
      (node (ref "B06") (pin "J2") (pinfunction "P$2_J2") (pintype "bidirectional"))
      (node (ref "B07") (pin "J2") (pinfunction "P$2_J2") (pintype "bidirectional"))
      (node (ref "B08") (pin "J2") (pinfunction "P$2_J2") (pintype "bidirectional"))
      (node (ref "B09") (pin "J2") (pinfunction "P$2_J2") (pintype "bidirectional"))
      (node (ref "B10") (pin "J2") (pinfunction "P$2_J2") (pintype "bidirectional"))
      (node (ref "B11") (pin "J2") (pinfunction "P$2_J2") (pintype "bidirectional"))
      (node (ref "B12") (pin "J2") (pinfunction "P$2_J2") (pintype "bidirectional"))
      (node (ref "B13") (pin "J2") (pinfunction "P$2_J2") (pintype "bidirectional"))
      (node (ref "B14") (pin "J2") (pinfunction "P$2_J2") (pintype "bidirectional"))
    )
    (net (code "136") (name "Net-(B01R-P$2)") (class "Default")
      (node (ref "B01") (pin "K2") (pinfunction "P$2_K2") (pintype "bidirectional"))
      (node (ref "B02") (pin "K2") (pinfunction "P$2_K2") (pintype "bidirectional"))
      (node (ref "B03") (pin "K2") (pinfunction "P$2_K2") (pintype "bidirectional"))
      (node (ref "B04") (pin "K2") (pinfunction "P$2_K2") (pintype "bidirectional"))
      (node (ref "B05") (pin "K2") (pinfunction "P$2_K2") (pintype "bidirectional"))
      (node (ref "B06") (pin "K2") (pinfunction "P$2_K2") (pintype "bidirectional"))
      (node (ref "B07") (pin "K2") (pinfunction "P$2_K2") (pintype "bidirectional"))
      (node (ref "B08") (pin "K2") (pinfunction "P$2_K2") (pintype "bidirectional"))
      (node (ref "B09") (pin "K2") (pinfunction "P$2_K2") (pintype "bidirectional"))
      (node (ref "B10") (pin "K2") (pinfunction "P$2_K2") (pintype "bidirectional"))
      (node (ref "B11") (pin "K2") (pinfunction "P$2_K2") (pintype "bidirectional"))
      (node (ref "B12") (pin "K2") (pinfunction "P$2_K2") (pintype "bidirectional"))
      (node (ref "B13") (pin "K2") (pinfunction "P$2_K2") (pintype "bidirectional"))
      (node (ref "B14") (pin "K2") (pinfunction "P$2_K2") (pintype "bidirectional"))
    )
    (net (code "137") (name "Net-(B01T-P$2)") (class "Default")
      (node (ref "B01") (pin "L2") (pinfunction "P$2_L2") (pintype "bidirectional"))
      (node (ref "B02") (pin "L2") (pinfunction "P$2_L2") (pintype "bidirectional"))
      (node (ref "B03") (pin "L2") (pinfunction "P$2_L2") (pintype "bidirectional"))
      (node (ref "B04") (pin "L2") (pinfunction "P$2_L2") (pintype "bidirectional"))
      (node (ref "B05") (pin "L2") (pinfunction "P$2_L2") (pintype "bidirectional"))
      (node (ref "B06") (pin "L2") (pinfunction "P$2_L2") (pintype "bidirectional"))
      (node (ref "B07") (pin "L2") (pinfunction "P$2_L2") (pintype "bidirectional"))
      (node (ref "B08") (pin "L2") (pinfunction "P$2_L2") (pintype "bidirectional"))
      (node (ref "B09") (pin "L2") (pinfunction "P$2_L2") (pintype "bidirectional"))
      (node (ref "B10") (pin "L2") (pinfunction "P$2_L2") (pintype "bidirectional"))
      (node (ref "B11") (pin "L2") (pinfunction "P$2_L2") (pintype "bidirectional"))
      (node (ref "B12") (pin "L2") (pinfunction "P$2_L2") (pintype "bidirectional"))
      (node (ref "B13") (pin "L2") (pinfunction "P$2_L2") (pintype "bidirectional"))
      (node (ref "B14") (pin "L2") (pinfunction "P$2_L2") (pintype "bidirectional"))
    )
    (net (code "138") (name "Net-(B01V-P$2)") (class "Default")
      (node (ref "B01") (pin "M2") (pinfunction "P$2_M2") (pintype "bidirectional"))
      (node (ref "B02") (pin "M2") (pinfunction "P$2_M2") (pintype "bidirectional"))
      (node (ref "B03") (pin "M2") (pinfunction "P$2_M2") (pintype "bidirectional"))
      (node (ref "B04") (pin "M2") (pinfunction "P$2_M2") (pintype "bidirectional"))
      (node (ref "B05") (pin "M2") (pinfunction "P$2_M2") (pintype "bidirectional"))
      (node (ref "B06") (pin "M2") (pinfunction "P$2_M2") (pintype "bidirectional"))
      (node (ref "B07") (pin "M2") (pinfunction "P$2_M2") (pintype "bidirectional"))
      (node (ref "B08") (pin "M2") (pinfunction "P$2_M2") (pintype "bidirectional"))
      (node (ref "B09") (pin "M2") (pinfunction "P$2_M2") (pintype "bidirectional"))
      (node (ref "B10") (pin "M2") (pinfunction "P$2_M2") (pintype "bidirectional"))
      (node (ref "B11") (pin "M2") (pinfunction "P$2_M2") (pintype "bidirectional"))
      (node (ref "B12") (pin "M2") (pinfunction "P$2_M2") (pintype "bidirectional"))
      (node (ref "B13") (pin "M2") (pinfunction "P$2_M2") (pintype "bidirectional"))
      (node (ref "B14") (pin "M2") (pinfunction "P$2_M2") (pintype "bidirectional"))
    )
    (net (code "139") (name "Net-(B01Z-P$2)") (class "Default")
      (node (ref "B01") (pin "P2") (pinfunction "P$2_P2") (pintype "bidirectional"))
      (node (ref "B02") (pin "P2") (pinfunction "P$2_P2") (pintype "bidirectional"))
      (node (ref "B03") (pin "P2") (pinfunction "P$2_P2") (pintype "bidirectional"))
      (node (ref "B04") (pin "P2") (pinfunction "P$2_P2") (pintype "bidirectional"))
      (node (ref "B05") (pin "P2") (pinfunction "P$2_P2") (pintype "bidirectional"))
      (node (ref "B06") (pin "P2") (pinfunction "P$2_P2") (pintype "bidirectional"))
      (node (ref "B07") (pin "P2") (pinfunction "P$2_P2") (pintype "bidirectional"))
      (node (ref "B08") (pin "P2") (pinfunction "P$2_P2") (pintype "bidirectional"))
      (node (ref "B09") (pin "P2") (pinfunction "P$2_P2") (pintype "bidirectional"))
      (node (ref "B10") (pin "P2") (pinfunction "P$2_P2") (pintype "bidirectional"))
      (node (ref "B11") (pin "P2") (pinfunction "P$2_P2") (pintype "bidirectional"))
      (node (ref "B12") (pin "P2") (pinfunction "P$2_P2") (pintype "bidirectional"))
      (node (ref "B13") (pin "P2") (pinfunction "P$2_P2") (pintype "bidirectional"))
      (node (ref "B14") (pin "P2") (pinfunction "P$2_P2") (pintype "bidirectional"))
    )
    (net (code "140") (name "Net-(B15A-IN2)") (class "Default")
      (node (ref "B15") (pin "B1") (pinfunction "IN2_B1") (pintype "input"))
      (node (ref "B15") (pin "C1") (pinfunction "IN3_C1") (pintype "input"))
      (node (ref "B15") (pin "D1") (pinfunction "IN4_D1") (pintype "input"))
      (node (ref "B15") (pin "H1") (pinfunction "IN2_H1") (pintype "input"))
      (node (ref "B15") (pin "J1") (pinfunction "IN3_J1") (pintype "input"))
      (node (ref "B15") (pin "K1") (pinfunction "IN4_K1") (pintype "input"))
      (node (ref "B15") (pin "N1") (pinfunction "IN2_N1") (pintype "input"))
      (node (ref "B15") (pin "P1") (pinfunction "IN3_P1") (pintype "input"))
      (node (ref "B15") (pin "R1") (pinfunction "IN4_R1") (pintype "input"))
      (node (ref "B15") (pin "V1") (pinfunction "P$1_V1") (pintype "passive"))
    )
    (net (code "141") (name "Net-(B15D-IN2)") (class "Default")
      (node (ref "B15") (pin "E2") (pinfunction "IN2_E2") (pintype "input"))
      (node (ref "B15") (pin "F2") (pinfunction "IN3_F2") (pintype "input"))
      (node (ref "B15") (pin "H2") (pinfunction "IN4_H2") (pintype "input"))
      (node (ref "B15") (pin "L2") (pinfunction "IN2_L2") (pintype "input"))
      (node (ref "B15") (pin "M2") (pinfunction "IN3_M2") (pintype "input"))
      (node (ref "B15") (pin "N2") (pinfunction "IN4_N2") (pintype "input"))
      (node (ref "B15") (pin "S2") (pinfunction "IN2_S2") (pintype "input"))
      (node (ref "B15") (pin "T2") (pinfunction "IN3_T2") (pintype "input"))
      (node (ref "B15") (pin "U1") (pinfunction "P$1_U1") (pintype "passive"))
      (node (ref "B15") (pin "U2") (pinfunction "IN4_U2") (pintype "input"))
    )
    (net (code "142") (name "Net-(B16D-OUT)") (class "Default")
      (node (ref "B16") (pin "H2") (pinfunction "OUT_H2") (pintype "output"))
      (node (ref "C17") (pin "N2") (pinfunction "S_N2") (pintype "input"))
    )
    (net (code "143") (name "Net-(B16E-IN1)") (class "Default")
      (node (ref "B16") (pin "E1") (pinfunction "IN1_E1") (pintype "input"))
      (node (ref "D19") (pin "J2") (pinfunction "R1_J2") (pintype "bidirectional"))
    )
    (net (code "144") (name "Net-(B16E-IN2)") (class "Default")
      (node (ref "B16") (pin "F1") (pinfunction "IN2_F1") (pintype "input"))
      (node (ref "D19") (pin "F2") (pinfunction "R1_F2") (pintype "bidirectional"))
    )
    (net (code "145") (name "Net-(B16E-IN3)") (class "Default")
      (node (ref "B16") (pin "H1") (pinfunction "IN3_H1") (pintype "input"))
      (node (ref "D19") (pin "L2") (pinfunction "R1_L2") (pintype "bidirectional"))
    )
    (net (code "146") (name "Net-(B16E-OUT)") (class "Default")
      (node (ref "B16") (pin "J1") (pinfunction "OUT_J1") (pintype "output"))
      (node (ref "B17") (pin "U2") (pinfunction "IN2_U2") (pintype "input"))
    )
    (net (code "147") (name "Net-(B16F-OUT)") (class "Default")
      (node (ref "B16") (pin "M2") (pinfunction "OUT_M2") (pintype "output"))
      (node (ref "C17") (pin "U2") (pinfunction "S_U2") (pintype "input"))
    )
    (net (code "148") (name "Net-(B16I-OUT)") (class "Default")
      (node (ref "B16") (pin "U1") (pinfunction "OUT_U1") (pintype "output"))
      (node (ref "B18") (pin "R2") (pinfunction "A_R2") (pintype "input"))
    )
    (net (code "149") (name "Net-(B16J-OUT)") (class "Default")
      (node (ref "B16") (pin "V1") (pinfunction "OUT_V1") (pintype "output"))
      (node (ref "C20") (pin "H2") (pinfunction "H2_H2") (pintype "input"))
    )
    (net (code "150") (name "Net-(B17A-OUT)") (class "Default")
      (node (ref "B17") (pin "C1") (pinfunction "OUT_C1") (pintype "output"))
      (node (ref "D19") (pin "A1") (pinfunction "L1_A1") (pintype "bidirectional"))
    )
    (net (code "151") (name "Net-(B17B-OUT)") (class "Default")
      (node (ref "B17") (pin "F1") (pinfunction "OUT_F1") (pintype "output"))
      (node (ref "D18") (pin "H2") (pinfunction "IN_H2") (pintype "input"))
    )
    (net (code "152") (name "Net-(B17F-OUT)") (class "Default")
      (node (ref "B17") (pin "K1") (pinfunction "OUT_K1") (pintype "output"))
      (node (ref "D15") (pin "B1") (pinfunction "C_B1") (pintype "input"))
      (node (ref "D15") (pin "D2") (pinfunction "C_D2") (pintype "input"))
      (node (ref "D15") (pin "H1") (pinfunction "C_H1") (pintype "input"))
      (node (ref "D15") (pin "L2") (pinfunction "C_L2") (pintype "input"))
    )
    (net (code "153") (name "Net-(B17G-OUT)") (class "Default")
      (node (ref "B17") (pin "K2") (pinfunction "OUT_K2") (pintype "output"))
      (node (ref "D15") (pin "N1") (pinfunction "C_N1") (pintype "input"))
      (node (ref "D15") (pin "S2") (pinfunction "C_S2") (pintype "input"))
      (node (ref "D16") (pin "B1") (pinfunction "C_B1") (pintype "input"))
      (node (ref "D16") (pin "D2") (pinfunction "C_D2") (pintype "input"))
    )
    (net (code "154") (name "Net-(B17H-OUT)") (class "Default")
      (node (ref "B17") (pin "N1") (pinfunction "OUT_N1") (pintype "output"))
      (node (ref "D16") (pin "H1") (pinfunction "C_H1") (pintype "input"))
      (node (ref "D16") (pin "L2") (pinfunction "C_L2") (pintype "input"))
      (node (ref "D16") (pin "N1") (pinfunction "C_N1") (pintype "input"))
      (node (ref "D16") (pin "S2") (pinfunction "C_S2") (pintype "input"))
    )
    (net (code "155") (name "Net-(B17N-IN1)") (class "Default")
      (node (ref "B17") (pin "T2") (pinfunction "IN1_T2") (pintype "input"))
      (node (ref "D19") (pin "D2") (pinfunction "R1_D2") (pintype "bidirectional"))
    )
    (net (code "156") (name "Net-(B19A-C)") (class "Default")
      (node (ref "B19") (pin "C1") (pinfunction "C_C1") (pintype "input"))
      (node (ref "B19") (pin "F2") (pinfunction "C_F2") (pintype "input"))
      (node (ref "B19") (pin "J1") (pinfunction "C_J1") (pintype "input"))
      (node (ref "B19") (pin "M2") (pinfunction "C_M2") (pintype "input"))
      (node (ref "B19") (pin "P1") (pinfunction "C_P1") (pintype "input"))
      (node (ref "B19") (pin "T2") (pinfunction "C_T2") (pintype "input"))
      (node (ref "C16") (pin "J2") (pinfunction "OUT_J2") (pintype "output"))
    )
    (net (code "157") (name "Net-(B20A-A)") (class "Default")
      (node (ref "B20") (pin "A1") (pinfunction "A_A1") (pintype "input"))
      (node (ref "D15") (pin "F1") (pinfunction "0_F1") (pintype "output"))
    )
    (net (code "158") (name "Net-(B20A-B)") (class "Default")
      (node (ref "B20") (pin "B1") (pinfunction "B_B1") (pintype "input"))
      (node (ref "D15") (pin "J2") (pinfunction "0_J2") (pintype "output"))
    )
    (net (code "159") (name "Net-(B20A-C)") (class "Default")
      (node (ref "B20") (pin "C1") (pinfunction "C_C1") (pintype "input"))
      (node (ref "B20") (pin "F2") (pinfunction "C_F2") (pintype "input"))
      (node (ref "B20") (pin "J1") (pinfunction "C_J1") (pintype "input"))
      (node (ref "B20") (pin "M2") (pinfunction "C_M2") (pintype "input"))
      (node (ref "B20") (pin "P1") (pinfunction "C_P1") (pintype "input"))
      (node (ref "B20") (pin "T2") (pinfunction "C_T2") (pintype "input"))
      (node (ref "C16") (pin "P2") (pinfunction "OUT_P2") (pintype "output"))
    )
    (net (code "160") (name "Net-(B20F-A)") (class "Default")
      (node (ref "B20") (pin "D2") (pinfunction "A_D2") (pintype "input"))
      (node (ref "D16") (pin "F1") (pinfunction "0_F1") (pintype "output"))
    )
    (net (code "161") (name "Net-(B20F-B)") (class "Default")
      (node (ref "B20") (pin "E2") (pinfunction "B_E2") (pintype "input"))
      (node (ref "D16") (pin "J2") (pinfunction "0_J2") (pintype "output"))
    )
    (net (code "162") (name "Net-(B20G-A)") (class "Default")
      (node (ref "B20") (pin "F1") (pinfunction "A_F1") (pintype "input"))
      (node (ref "D15") (pin "M1") (pinfunction "0_M1") (pintype "output"))
    )
    (net (code "163") (name "Net-(B20G-B)") (class "Default")
      (node (ref "B20") (pin "H1") (pinfunction "B_H1") (pintype "input"))
      (node (ref "D15") (pin "R2") (pinfunction "0_R2") (pintype "output"))
    )
    (net (code "164") (name "Net-(B20H-A)") (class "Default")
      (node (ref "B20") (pin "K2") (pinfunction "A_K2") (pintype "input"))
      (node (ref "D16") (pin "M1") (pinfunction "0_M1") (pintype "output"))
    )
    (net (code "165") (name "Net-(B20H-B)") (class "Default")
      (node (ref "B20") (pin "L2") (pinfunction "B_L2") (pintype "input"))
      (node (ref "D16") (pin "R2") (pinfunction "0_R2") (pintype "output"))
    )
    (net (code "166") (name "Net-(B20I-A)") (class "Default")
      (node (ref "B20") (pin "M1") (pinfunction "A_M1") (pintype "input"))
      (node (ref "D15") (pin "U1") (pinfunction "0_U1") (pintype "output"))
    )
    (net (code "167") (name "Net-(B20I-B)") (class "Default")
      (node (ref "B20") (pin "N1") (pinfunction "B_N1") (pintype "input"))
      (node (ref "D15") (pin "V1") (pinfunction "0_V1") (pintype "output"))
    )
    (net (code "168") (name "Net-(B20J-A)") (class "Default")
      (node (ref "B20") (pin "R2") (pinfunction "A_R2") (pintype "input"))
      (node (ref "D16") (pin "U1") (pinfunction "0_U1") (pintype "output"))
    )
    (net (code "169") (name "Net-(B20J-B)") (class "Default")
      (node (ref "B20") (pin "S2") (pinfunction "B_S2") (pintype "input"))
      (node (ref "D16") (pin "V1") (pinfunction "0_V1") (pintype "output"))
    )
    (net (code "170") (name "Net-(C01A-P$2)") (class "Default")
      (node (ref "C01") (pin "A1") (pinfunction "P$2_A1") (pintype "bidirectional"))
      (node (ref "C02") (pin "A1") (pinfunction "P$2_A1") (pintype "bidirectional"))
      (node (ref "C03") (pin "A1") (pinfunction "P$2_A1") (pintype "bidirectional"))
      (node (ref "C04") (pin "A1") (pinfunction "P$2_A1") (pintype "bidirectional"))
      (node (ref "C05") (pin "A1") (pinfunction "P$2_A1") (pintype "bidirectional"))
      (node (ref "C06") (pin "A1") (pinfunction "P$2_A1") (pintype "bidirectional"))
      (node (ref "C07") (pin "A1") (pinfunction "P$2_A1") (pintype "bidirectional"))
      (node (ref "C08") (pin "A1") (pinfunction "P$2_A1") (pintype "bidirectional"))
      (node (ref "C09") (pin "A1") (pinfunction "P$2_A1") (pintype "bidirectional"))
      (node (ref "C10") (pin "A1") (pinfunction "P$2_A1") (pintype "bidirectional"))
      (node (ref "C11") (pin "A1") (pinfunction "P$2_A1") (pintype "bidirectional"))
      (node (ref "C12") (pin "A1") (pinfunction "P$2_A1") (pintype "bidirectional"))
      (node (ref "C13") (pin "A1") (pinfunction "P$2_A1") (pintype "bidirectional"))
      (node (ref "C14") (pin "A1") (pinfunction "P$2_A1") (pintype "bidirectional"))
    )
    (net (code "171") (name "Net-(C01AA-P$2)") (class "Default")
      (node (ref "C01") (pin "R1") (pinfunction "P$2_R1") (pintype "bidirectional"))
      (node (ref "C02") (pin "R1") (pinfunction "P$2_R1") (pintype "bidirectional"))
      (node (ref "C03") (pin "R1") (pinfunction "P$2_R1") (pintype "bidirectional"))
      (node (ref "C04") (pin "R1") (pinfunction "P$2_R1") (pintype "bidirectional"))
      (node (ref "C05") (pin "R1") (pinfunction "P$2_R1") (pintype "bidirectional"))
      (node (ref "C06") (pin "R1") (pinfunction "P$2_R1") (pintype "bidirectional"))
      (node (ref "C07") (pin "R1") (pinfunction "P$2_R1") (pintype "bidirectional"))
      (node (ref "C08") (pin "R1") (pinfunction "P$2_R1") (pintype "bidirectional"))
      (node (ref "C09") (pin "R1") (pinfunction "P$2_R1") (pintype "bidirectional"))
      (node (ref "C10") (pin "R1") (pinfunction "P$2_R1") (pintype "bidirectional"))
      (node (ref "C11") (pin "R1") (pinfunction "P$2_R1") (pintype "bidirectional"))
      (node (ref "C12") (pin "R1") (pinfunction "P$2_R1") (pintype "bidirectional"))
      (node (ref "C13") (pin "R1") (pinfunction "P$2_R1") (pintype "bidirectional"))
      (node (ref "C14") (pin "R1") (pinfunction "P$2_R1") (pintype "bidirectional"))
    )
    (net (code "172") (name "Net-(C01AB-P$2)") (class "Default")
      (node (ref "C01") (pin "R2") (pinfunction "P$2_R2") (pintype "bidirectional"))
      (node (ref "C02") (pin "R2") (pinfunction "P$2_R2") (pintype "bidirectional"))
      (node (ref "C03") (pin "R2") (pinfunction "P$2_R2") (pintype "bidirectional"))
      (node (ref "C04") (pin "R2") (pinfunction "P$2_R2") (pintype "bidirectional"))
      (node (ref "C05") (pin "R2") (pinfunction "P$2_R2") (pintype "bidirectional"))
      (node (ref "C06") (pin "R2") (pinfunction "P$2_R2") (pintype "bidirectional"))
      (node (ref "C07") (pin "R2") (pinfunction "P$2_R2") (pintype "bidirectional"))
      (node (ref "C08") (pin "R2") (pinfunction "P$2_R2") (pintype "bidirectional"))
      (node (ref "C09") (pin "R2") (pinfunction "P$2_R2") (pintype "bidirectional"))
      (node (ref "C10") (pin "R2") (pinfunction "P$2_R2") (pintype "bidirectional"))
      (node (ref "C11") (pin "R2") (pinfunction "P$2_R2") (pintype "bidirectional"))
      (node (ref "C12") (pin "R2") (pinfunction "P$2_R2") (pintype "bidirectional"))
      (node (ref "C13") (pin "R2") (pinfunction "P$2_R2") (pintype "bidirectional"))
      (node (ref "C14") (pin "R2") (pinfunction "P$2_R2") (pintype "bidirectional"))
    )
    (net (code "173") (name "Net-(C01AC-P$2)") (class "Default")
      (node (ref "C01") (pin "S1") (pinfunction "P$2_S1") (pintype "bidirectional"))
      (node (ref "C02") (pin "S1") (pinfunction "P$2_S1") (pintype "bidirectional"))
      (node (ref "C03") (pin "S1") (pinfunction "P$2_S1") (pintype "bidirectional"))
      (node (ref "C04") (pin "S1") (pinfunction "P$2_S1") (pintype "bidirectional"))
      (node (ref "C05") (pin "S1") (pinfunction "P$2_S1") (pintype "bidirectional"))
      (node (ref "C06") (pin "S1") (pinfunction "P$2_S1") (pintype "bidirectional"))
      (node (ref "C07") (pin "S1") (pinfunction "P$2_S1") (pintype "bidirectional"))
      (node (ref "C08") (pin "S1") (pinfunction "P$2_S1") (pintype "bidirectional"))
      (node (ref "C09") (pin "S1") (pinfunction "P$2_S1") (pintype "bidirectional"))
      (node (ref "C10") (pin "S1") (pinfunction "P$2_S1") (pintype "bidirectional"))
      (node (ref "C11") (pin "S1") (pinfunction "P$2_S1") (pintype "bidirectional"))
      (node (ref "C12") (pin "S1") (pinfunction "P$2_S1") (pintype "bidirectional"))
      (node (ref "C13") (pin "S1") (pinfunction "P$2_S1") (pintype "bidirectional"))
      (node (ref "C14") (pin "S1") (pinfunction "P$2_S1") (pintype "bidirectional"))
    )
    (net (code "174") (name "Net-(C01AD-P$2)") (class "Default")
      (node (ref "C01") (pin "S2") (pinfunction "P$2_S2") (pintype "bidirectional"))
      (node (ref "C02") (pin "S2") (pinfunction "P$2_S2") (pintype "bidirectional"))
      (node (ref "C03") (pin "S2") (pinfunction "P$2_S2") (pintype "bidirectional"))
      (node (ref "C04") (pin "S2") (pinfunction "P$2_S2") (pintype "bidirectional"))
      (node (ref "C05") (pin "S2") (pinfunction "P$2_S2") (pintype "bidirectional"))
      (node (ref "C06") (pin "S2") (pinfunction "P$2_S2") (pintype "bidirectional"))
      (node (ref "C07") (pin "S2") (pinfunction "P$2_S2") (pintype "bidirectional"))
      (node (ref "C08") (pin "S2") (pinfunction "P$2_S2") (pintype "bidirectional"))
      (node (ref "C09") (pin "S2") (pinfunction "P$2_S2") (pintype "bidirectional"))
      (node (ref "C10") (pin "S2") (pinfunction "P$2_S2") (pintype "bidirectional"))
      (node (ref "C11") (pin "S2") (pinfunction "P$2_S2") (pintype "bidirectional"))
      (node (ref "C12") (pin "S2") (pinfunction "P$2_S2") (pintype "bidirectional"))
      (node (ref "C13") (pin "S2") (pinfunction "P$2_S2") (pintype "bidirectional"))
      (node (ref "C14") (pin "S2") (pinfunction "P$2_S2") (pintype "bidirectional"))
    )
    (net (code "175") (name "Net-(C01AG-P$2)") (class "Default")
      (node (ref "C01") (pin "U1") (pinfunction "P$2_U1") (pintype "bidirectional"))
      (node (ref "C02") (pin "U1") (pinfunction "P$2_U1") (pintype "bidirectional"))
      (node (ref "C03") (pin "U1") (pinfunction "P$2_U1") (pintype "bidirectional"))
      (node (ref "C04") (pin "U1") (pinfunction "P$2_U1") (pintype "bidirectional"))
      (node (ref "C05") (pin "U1") (pinfunction "P$2_U1") (pintype "bidirectional"))
      (node (ref "C06") (pin "U1") (pinfunction "P$2_U1") (pintype "bidirectional"))
      (node (ref "C07") (pin "U1") (pinfunction "P$2_U1") (pintype "bidirectional"))
      (node (ref "C08") (pin "U1") (pinfunction "P$2_U1") (pintype "bidirectional"))
      (node (ref "C09") (pin "U1") (pinfunction "P$2_U1") (pintype "bidirectional"))
      (node (ref "C10") (pin "U1") (pinfunction "P$2_U1") (pintype "bidirectional"))
      (node (ref "C11") (pin "U1") (pinfunction "P$2_U1") (pintype "bidirectional"))
      (node (ref "C12") (pin "U1") (pinfunction "P$2_U1") (pintype "bidirectional"))
      (node (ref "C13") (pin "U1") (pinfunction "P$2_U1") (pintype "bidirectional"))
      (node (ref "C14") (pin "U1") (pinfunction "P$2_U1") (pintype "bidirectional"))
    )
    (net (code "176") (name "Net-(C01AH-P$2)") (class "Default")
      (node (ref "C01") (pin "U2") (pinfunction "P$2_U2") (pintype "bidirectional"))
      (node (ref "C02") (pin "U2") (pinfunction "P$2_U2") (pintype "bidirectional"))
      (node (ref "C03") (pin "U2") (pinfunction "P$2_U2") (pintype "bidirectional"))
      (node (ref "C04") (pin "U2") (pinfunction "P$2_U2") (pintype "bidirectional"))
      (node (ref "C05") (pin "U2") (pinfunction "P$2_U2") (pintype "bidirectional"))
      (node (ref "C06") (pin "U2") (pinfunction "P$2_U2") (pintype "bidirectional"))
      (node (ref "C07") (pin "U2") (pinfunction "P$2_U2") (pintype "bidirectional"))
      (node (ref "C08") (pin "U2") (pinfunction "P$2_U2") (pintype "bidirectional"))
      (node (ref "C09") (pin "U2") (pinfunction "P$2_U2") (pintype "bidirectional"))
      (node (ref "C10") (pin "U2") (pinfunction "P$2_U2") (pintype "bidirectional"))
      (node (ref "C11") (pin "U2") (pinfunction "P$2_U2") (pintype "bidirectional"))
      (node (ref "C12") (pin "U2") (pinfunction "P$2_U2") (pintype "bidirectional"))
      (node (ref "C13") (pin "U2") (pinfunction "P$2_U2") (pintype "bidirectional"))
      (node (ref "C14") (pin "U2") (pinfunction "P$2_U2") (pintype "bidirectional"))
    )
    (net (code "177") (name "Net-(C01AI-P$2)") (class "Default")
      (node (ref "C01") (pin "V1") (pinfunction "P$2_V1") (pintype "bidirectional"))
      (node (ref "C02") (pin "V1") (pinfunction "P$2_V1") (pintype "bidirectional"))
      (node (ref "C03") (pin "V1") (pinfunction "P$2_V1") (pintype "bidirectional"))
      (node (ref "C04") (pin "V1") (pinfunction "P$2_V1") (pintype "bidirectional"))
      (node (ref "C05") (pin "V1") (pinfunction "P$2_V1") (pintype "bidirectional"))
      (node (ref "C06") (pin "V1") (pinfunction "P$2_V1") (pintype "bidirectional"))
      (node (ref "C07") (pin "V1") (pinfunction "P$2_V1") (pintype "bidirectional"))
      (node (ref "C08") (pin "V1") (pinfunction "P$2_V1") (pintype "bidirectional"))
      (node (ref "C09") (pin "V1") (pinfunction "P$2_V1") (pintype "bidirectional"))
      (node (ref "C10") (pin "V1") (pinfunction "P$2_V1") (pintype "bidirectional"))
      (node (ref "C11") (pin "V1") (pinfunction "P$2_V1") (pintype "bidirectional"))
      (node (ref "C12") (pin "V1") (pinfunction "P$2_V1") (pintype "bidirectional"))
      (node (ref "C13") (pin "V1") (pinfunction "P$2_V1") (pintype "bidirectional"))
      (node (ref "C14") (pin "V1") (pinfunction "P$2_V1") (pintype "bidirectional"))
    )
    (net (code "178") (name "Net-(C01AJ-P$2)") (class "Default")
      (node (ref "C01") (pin "V2") (pinfunction "P$2_V2") (pintype "bidirectional"))
      (node (ref "C02") (pin "V2") (pinfunction "P$2_V2") (pintype "bidirectional"))
      (node (ref "C03") (pin "V2") (pinfunction "P$2_V2") (pintype "bidirectional"))
      (node (ref "C04") (pin "V2") (pinfunction "P$2_V2") (pintype "bidirectional"))
      (node (ref "C05") (pin "V2") (pinfunction "P$2_V2") (pintype "bidirectional"))
      (node (ref "C06") (pin "V2") (pinfunction "P$2_V2") (pintype "bidirectional"))
      (node (ref "C07") (pin "V2") (pinfunction "P$2_V2") (pintype "bidirectional"))
      (node (ref "C08") (pin "V2") (pinfunction "P$2_V2") (pintype "bidirectional"))
      (node (ref "C09") (pin "V2") (pinfunction "P$2_V2") (pintype "bidirectional"))
      (node (ref "C10") (pin "V2") (pinfunction "P$2_V2") (pintype "bidirectional"))
      (node (ref "C11") (pin "V2") (pinfunction "P$2_V2") (pintype "bidirectional"))
      (node (ref "C12") (pin "V2") (pinfunction "P$2_V2") (pintype "bidirectional"))
      (node (ref "C13") (pin "V2") (pinfunction "P$2_V2") (pintype "bidirectional"))
      (node (ref "C14") (pin "V2") (pinfunction "P$2_V2") (pintype "bidirectional"))
    )
    (net (code "179") (name "Net-(C01C-P$2)") (class "Default")
      (node (ref "C01") (pin "B1") (pinfunction "P$2_B1") (pintype "bidirectional"))
      (node (ref "C02") (pin "B1") (pinfunction "P$2_B1") (pintype "bidirectional"))
      (node (ref "C03") (pin "B1") (pinfunction "P$2_B1") (pintype "bidirectional"))
      (node (ref "C04") (pin "B1") (pinfunction "P$2_B1") (pintype "bidirectional"))
      (node (ref "C05") (pin "B1") (pinfunction "P$2_B1") (pintype "bidirectional"))
      (node (ref "C06") (pin "B1") (pinfunction "P$2_B1") (pintype "bidirectional"))
      (node (ref "C07") (pin "B1") (pinfunction "P$2_B1") (pintype "bidirectional"))
      (node (ref "C08") (pin "B1") (pinfunction "P$2_B1") (pintype "bidirectional"))
      (node (ref "C09") (pin "B1") (pinfunction "P$2_B1") (pintype "bidirectional"))
      (node (ref "C10") (pin "B1") (pinfunction "P$2_B1") (pintype "bidirectional"))
      (node (ref "C11") (pin "B1") (pinfunction "P$2_B1") (pintype "bidirectional"))
      (node (ref "C12") (pin "B1") (pinfunction "P$2_B1") (pintype "bidirectional"))
      (node (ref "C13") (pin "B1") (pinfunction "P$2_B1") (pintype "bidirectional"))
      (node (ref "C14") (pin "B1") (pinfunction "P$2_B1") (pintype "bidirectional"))
    )
    (net (code "180") (name "Net-(C01G-P$2)") (class "Default")
      (node (ref "C01") (pin "D1") (pinfunction "P$2_D1") (pintype "bidirectional"))
      (node (ref "C02") (pin "D1") (pinfunction "P$2_D1") (pintype "bidirectional"))
      (node (ref "C03") (pin "D1") (pinfunction "P$2_D1") (pintype "bidirectional"))
      (node (ref "C04") (pin "D1") (pinfunction "P$2_D1") (pintype "bidirectional"))
      (node (ref "C05") (pin "D1") (pinfunction "P$2_D1") (pintype "bidirectional"))
      (node (ref "C06") (pin "D1") (pinfunction "P$2_D1") (pintype "bidirectional"))
      (node (ref "C07") (pin "D1") (pinfunction "P$2_D1") (pintype "bidirectional"))
      (node (ref "C08") (pin "D1") (pinfunction "P$2_D1") (pintype "bidirectional"))
      (node (ref "C09") (pin "D1") (pinfunction "P$2_D1") (pintype "bidirectional"))
      (node (ref "C10") (pin "D1") (pinfunction "P$2_D1") (pintype "bidirectional"))
      (node (ref "C11") (pin "D1") (pinfunction "P$2_D1") (pintype "bidirectional"))
      (node (ref "C12") (pin "D1") (pinfunction "P$2_D1") (pintype "bidirectional"))
      (node (ref "C13") (pin "D1") (pinfunction "P$2_D1") (pintype "bidirectional"))
      (node (ref "C14") (pin "D1") (pinfunction "P$2_D1") (pintype "bidirectional"))
    )
    (net (code "181") (name "Net-(C01H-P$2)") (class "Default")
      (node (ref "C01") (pin "D2") (pinfunction "P$2_D2") (pintype "bidirectional"))
      (node (ref "C02") (pin "D2") (pinfunction "P$2_D2") (pintype "bidirectional"))
      (node (ref "C03") (pin "D2") (pinfunction "P$2_D2") (pintype "bidirectional"))
      (node (ref "C04") (pin "D2") (pinfunction "P$2_D2") (pintype "bidirectional"))
      (node (ref "C05") (pin "D2") (pinfunction "P$2_D2") (pintype "bidirectional"))
      (node (ref "C06") (pin "D2") (pinfunction "P$2_D2") (pintype "bidirectional"))
      (node (ref "C07") (pin "D2") (pinfunction "P$2_D2") (pintype "bidirectional"))
      (node (ref "C08") (pin "D2") (pinfunction "P$2_D2") (pintype "bidirectional"))
      (node (ref "C09") (pin "D2") (pinfunction "P$2_D2") (pintype "bidirectional"))
      (node (ref "C10") (pin "D2") (pinfunction "P$2_D2") (pintype "bidirectional"))
      (node (ref "C11") (pin "D2") (pinfunction "P$2_D2") (pintype "bidirectional"))
      (node (ref "C12") (pin "D2") (pinfunction "P$2_D2") (pintype "bidirectional"))
      (node (ref "C13") (pin "D2") (pinfunction "P$2_D2") (pintype "bidirectional"))
      (node (ref "C14") (pin "D2") (pinfunction "P$2_D2") (pintype "bidirectional"))
    )
    (net (code "182") (name "Net-(C01I-P$2)") (class "Default")
      (node (ref "C01") (pin "E1") (pinfunction "P$2_E1") (pintype "bidirectional"))
      (node (ref "C02") (pin "E1") (pinfunction "P$2_E1") (pintype "bidirectional"))
      (node (ref "C03") (pin "E1") (pinfunction "P$2_E1") (pintype "bidirectional"))
      (node (ref "C04") (pin "E1") (pinfunction "P$2_E1") (pintype "bidirectional"))
      (node (ref "C05") (pin "E1") (pinfunction "P$2_E1") (pintype "bidirectional"))
      (node (ref "C06") (pin "E1") (pinfunction "P$2_E1") (pintype "bidirectional"))
      (node (ref "C07") (pin "E1") (pinfunction "P$2_E1") (pintype "bidirectional"))
      (node (ref "C08") (pin "E1") (pinfunction "P$2_E1") (pintype "bidirectional"))
      (node (ref "C09") (pin "E1") (pinfunction "P$2_E1") (pintype "bidirectional"))
      (node (ref "C10") (pin "E1") (pinfunction "P$2_E1") (pintype "bidirectional"))
      (node (ref "C11") (pin "E1") (pinfunction "P$2_E1") (pintype "bidirectional"))
      (node (ref "C12") (pin "E1") (pinfunction "P$2_E1") (pintype "bidirectional"))
      (node (ref "C13") (pin "E1") (pinfunction "P$2_E1") (pintype "bidirectional"))
      (node (ref "C14") (pin "E1") (pinfunction "P$2_E1") (pintype "bidirectional"))
    )
    (net (code "183") (name "Net-(C01J-P$2)") (class "Default")
      (node (ref "C01") (pin "E2") (pinfunction "P$2_E2") (pintype "bidirectional"))
      (node (ref "C02") (pin "E2") (pinfunction "P$2_E2") (pintype "bidirectional"))
      (node (ref "C03") (pin "E2") (pinfunction "P$2_E2") (pintype "bidirectional"))
      (node (ref "C04") (pin "E2") (pinfunction "P$2_E2") (pintype "bidirectional"))
      (node (ref "C05") (pin "E2") (pinfunction "P$2_E2") (pintype "bidirectional"))
      (node (ref "C06") (pin "E2") (pinfunction "P$2_E2") (pintype "bidirectional"))
      (node (ref "C07") (pin "E2") (pinfunction "P$2_E2") (pintype "bidirectional"))
      (node (ref "C08") (pin "E2") (pinfunction "P$2_E2") (pintype "bidirectional"))
      (node (ref "C09") (pin "E2") (pinfunction "P$2_E2") (pintype "bidirectional"))
      (node (ref "C10") (pin "E2") (pinfunction "P$2_E2") (pintype "bidirectional"))
      (node (ref "C11") (pin "E2") (pinfunction "P$2_E2") (pintype "bidirectional"))
      (node (ref "C12") (pin "E2") (pinfunction "P$2_E2") (pintype "bidirectional"))
      (node (ref "C13") (pin "E2") (pinfunction "P$2_E2") (pintype "bidirectional"))
      (node (ref "C14") (pin "E2") (pinfunction "P$2_E2") (pintype "bidirectional"))
    )
    (net (code "184") (name "Net-(C01M-P$2)") (class "Default")
      (node (ref "C01") (pin "H1") (pinfunction "P$2_H1") (pintype "bidirectional"))
      (node (ref "C02") (pin "H1") (pinfunction "P$2_H1") (pintype "bidirectional"))
      (node (ref "C03") (pin "H1") (pinfunction "P$2_H1") (pintype "bidirectional"))
      (node (ref "C04") (pin "H1") (pinfunction "P$2_H1") (pintype "bidirectional"))
      (node (ref "C05") (pin "H1") (pinfunction "P$2_H1") (pintype "bidirectional"))
      (node (ref "C06") (pin "H1") (pinfunction "P$2_H1") (pintype "bidirectional"))
      (node (ref "C07") (pin "H1") (pinfunction "P$2_H1") (pintype "bidirectional"))
      (node (ref "C08") (pin "H1") (pinfunction "P$2_H1") (pintype "bidirectional"))
      (node (ref "C09") (pin "H1") (pinfunction "P$2_H1") (pintype "bidirectional"))
      (node (ref "C10") (pin "H1") (pinfunction "P$2_H1") (pintype "bidirectional"))
      (node (ref "C11") (pin "H1") (pinfunction "P$2_H1") (pintype "bidirectional"))
      (node (ref "C12") (pin "H1") (pinfunction "P$2_H1") (pintype "bidirectional"))
      (node (ref "C13") (pin "H1") (pinfunction "P$2_H1") (pintype "bidirectional"))
      (node (ref "C14") (pin "H1") (pinfunction "P$2_H1") (pintype "bidirectional"))
    )
    (net (code "185") (name "Net-(C01N-P$2)") (class "Default")
      (node (ref "C01") (pin "H2") (pinfunction "P$2_H2") (pintype "bidirectional"))
      (node (ref "C02") (pin "H2") (pinfunction "P$2_H2") (pintype "bidirectional"))
      (node (ref "C03") (pin "H2") (pinfunction "P$2_H2") (pintype "bidirectional"))
      (node (ref "C04") (pin "H2") (pinfunction "P$2_H2") (pintype "bidirectional"))
      (node (ref "C05") (pin "H2") (pinfunction "P$2_H2") (pintype "bidirectional"))
      (node (ref "C06") (pin "H2") (pinfunction "P$2_H2") (pintype "bidirectional"))
      (node (ref "C07") (pin "H2") (pinfunction "P$2_H2") (pintype "bidirectional"))
      (node (ref "C08") (pin "H2") (pinfunction "P$2_H2") (pintype "bidirectional"))
      (node (ref "C09") (pin "H2") (pinfunction "P$2_H2") (pintype "bidirectional"))
      (node (ref "C10") (pin "H2") (pinfunction "P$2_H2") (pintype "bidirectional"))
      (node (ref "C11") (pin "H2") (pinfunction "P$2_H2") (pintype "bidirectional"))
      (node (ref "C12") (pin "H2") (pinfunction "P$2_H2") (pintype "bidirectional"))
      (node (ref "C13") (pin "H2") (pinfunction "P$2_H2") (pintype "bidirectional"))
      (node (ref "C14") (pin "H2") (pinfunction "P$2_H2") (pintype "bidirectional"))
    )
    (net (code "186") (name "Net-(C01O-P$2)") (class "Default")
      (node (ref "C01") (pin "J1") (pinfunction "P$2_J1") (pintype "bidirectional"))
      (node (ref "C02") (pin "J1") (pinfunction "P$2_J1") (pintype "bidirectional"))
      (node (ref "C03") (pin "J1") (pinfunction "P$2_J1") (pintype "bidirectional"))
      (node (ref "C04") (pin "J1") (pinfunction "P$2_J1") (pintype "bidirectional"))
      (node (ref "C05") (pin "J1") (pinfunction "P$2_J1") (pintype "bidirectional"))
      (node (ref "C06") (pin "J1") (pinfunction "P$2_J1") (pintype "bidirectional"))
      (node (ref "C07") (pin "J1") (pinfunction "P$2_J1") (pintype "bidirectional"))
      (node (ref "C08") (pin "J1") (pinfunction "P$2_J1") (pintype "bidirectional"))
      (node (ref "C09") (pin "J1") (pinfunction "P$2_J1") (pintype "bidirectional"))
      (node (ref "C10") (pin "J1") (pinfunction "P$2_J1") (pintype "bidirectional"))
      (node (ref "C11") (pin "J1") (pinfunction "P$2_J1") (pintype "bidirectional"))
      (node (ref "C12") (pin "J1") (pinfunction "P$2_J1") (pintype "bidirectional"))
      (node (ref "C13") (pin "J1") (pinfunction "P$2_J1") (pintype "bidirectional"))
      (node (ref "C14") (pin "J1") (pinfunction "P$2_J1") (pintype "bidirectional"))
    )
    (net (code "187") (name "Net-(C01P-P$2)") (class "Default")
      (node (ref "C01") (pin "J2") (pinfunction "P$2_J2") (pintype "bidirectional"))
      (node (ref "C02") (pin "J2") (pinfunction "P$2_J2") (pintype "bidirectional"))
      (node (ref "C03") (pin "J2") (pinfunction "P$2_J2") (pintype "bidirectional"))
      (node (ref "C04") (pin "J2") (pinfunction "P$2_J2") (pintype "bidirectional"))
      (node (ref "C05") (pin "J2") (pinfunction "P$2_J2") (pintype "bidirectional"))
      (node (ref "C06") (pin "J2") (pinfunction "P$2_J2") (pintype "bidirectional"))
      (node (ref "C07") (pin "J2") (pinfunction "P$2_J2") (pintype "bidirectional"))
      (node (ref "C08") (pin "J2") (pinfunction "P$2_J2") (pintype "bidirectional"))
      (node (ref "C09") (pin "J2") (pinfunction "P$2_J2") (pintype "bidirectional"))
      (node (ref "C10") (pin "J2") (pinfunction "P$2_J2") (pintype "bidirectional"))
      (node (ref "C11") (pin "J2") (pinfunction "P$2_J2") (pintype "bidirectional"))
      (node (ref "C12") (pin "J2") (pinfunction "P$2_J2") (pintype "bidirectional"))
      (node (ref "C13") (pin "J2") (pinfunction "P$2_J2") (pintype "bidirectional"))
      (node (ref "C14") (pin "J2") (pinfunction "P$2_J2") (pintype "bidirectional"))
    )
    (net (code "188") (name "Net-(C01Q-P$2)") (class "Default")
      (node (ref "C01") (pin "K1") (pinfunction "P$2_K1") (pintype "bidirectional"))
      (node (ref "C02") (pin "K1") (pinfunction "P$2_K1") (pintype "bidirectional"))
      (node (ref "C03") (pin "K1") (pinfunction "P$2_K1") (pintype "bidirectional"))
      (node (ref "C04") (pin "K1") (pinfunction "P$2_K1") (pintype "bidirectional"))
      (node (ref "C05") (pin "K1") (pinfunction "P$2_K1") (pintype "bidirectional"))
      (node (ref "C06") (pin "K1") (pinfunction "P$2_K1") (pintype "bidirectional"))
      (node (ref "C07") (pin "K1") (pinfunction "P$2_K1") (pintype "bidirectional"))
      (node (ref "C08") (pin "K1") (pinfunction "P$2_K1") (pintype "bidirectional"))
      (node (ref "C09") (pin "K1") (pinfunction "P$2_K1") (pintype "bidirectional"))
      (node (ref "C10") (pin "K1") (pinfunction "P$2_K1") (pintype "bidirectional"))
      (node (ref "C11") (pin "K1") (pinfunction "P$2_K1") (pintype "bidirectional"))
      (node (ref "C12") (pin "K1") (pinfunction "P$2_K1") (pintype "bidirectional"))
      (node (ref "C13") (pin "K1") (pinfunction "P$2_K1") (pintype "bidirectional"))
      (node (ref "C14") (pin "K1") (pinfunction "P$2_K1") (pintype "bidirectional"))
    )
    (net (code "189") (name "Net-(C01R-P$2)") (class "Default")
      (node (ref "C01") (pin "K2") (pinfunction "P$2_K2") (pintype "bidirectional"))
      (node (ref "C02") (pin "K2") (pinfunction "P$2_K2") (pintype "bidirectional"))
      (node (ref "C03") (pin "K2") (pinfunction "P$2_K2") (pintype "bidirectional"))
      (node (ref "C04") (pin "K2") (pinfunction "P$2_K2") (pintype "bidirectional"))
      (node (ref "C05") (pin "K2") (pinfunction "P$2_K2") (pintype "bidirectional"))
      (node (ref "C06") (pin "K2") (pinfunction "P$2_K2") (pintype "bidirectional"))
      (node (ref "C07") (pin "K2") (pinfunction "P$2_K2") (pintype "bidirectional"))
      (node (ref "C08") (pin "K2") (pinfunction "P$2_K2") (pintype "bidirectional"))
      (node (ref "C09") (pin "K2") (pinfunction "P$2_K2") (pintype "bidirectional"))
      (node (ref "C10") (pin "K2") (pinfunction "P$2_K2") (pintype "bidirectional"))
      (node (ref "C11") (pin "K2") (pinfunction "P$2_K2") (pintype "bidirectional"))
      (node (ref "C12") (pin "K2") (pinfunction "P$2_K2") (pintype "bidirectional"))
      (node (ref "C13") (pin "K2") (pinfunction "P$2_K2") (pintype "bidirectional"))
      (node (ref "C14") (pin "K2") (pinfunction "P$2_K2") (pintype "bidirectional"))
    )
    (net (code "190") (name "Net-(C01S-P$2)") (class "Default")
      (node (ref "C01") (pin "L1") (pinfunction "P$2_L1") (pintype "bidirectional"))
      (node (ref "C02") (pin "L1") (pinfunction "P$2_L1") (pintype "bidirectional"))
      (node (ref "C03") (pin "L1") (pinfunction "P$2_L1") (pintype "bidirectional"))
      (node (ref "C04") (pin "L1") (pinfunction "P$2_L1") (pintype "bidirectional"))
      (node (ref "C05") (pin "L1") (pinfunction "P$2_L1") (pintype "bidirectional"))
      (node (ref "C06") (pin "L1") (pinfunction "P$2_L1") (pintype "bidirectional"))
      (node (ref "C07") (pin "L1") (pinfunction "P$2_L1") (pintype "bidirectional"))
      (node (ref "C08") (pin "L1") (pinfunction "P$2_L1") (pintype "bidirectional"))
      (node (ref "C09") (pin "L1") (pinfunction "P$2_L1") (pintype "bidirectional"))
      (node (ref "C10") (pin "L1") (pinfunction "P$2_L1") (pintype "bidirectional"))
      (node (ref "C11") (pin "L1") (pinfunction "P$2_L1") (pintype "bidirectional"))
      (node (ref "C12") (pin "L1") (pinfunction "P$2_L1") (pintype "bidirectional"))
      (node (ref "C13") (pin "L1") (pinfunction "P$2_L1") (pintype "bidirectional"))
      (node (ref "C14") (pin "L1") (pinfunction "P$2_L1") (pintype "bidirectional"))
    )
    (net (code "191") (name "Net-(C01T-P$2)") (class "Default")
      (node (ref "C01") (pin "L2") (pinfunction "P$2_L2") (pintype "bidirectional"))
      (node (ref "C02") (pin "L2") (pinfunction "P$2_L2") (pintype "bidirectional"))
      (node (ref "C03") (pin "L2") (pinfunction "P$2_L2") (pintype "bidirectional"))
      (node (ref "C04") (pin "L2") (pinfunction "P$2_L2") (pintype "bidirectional"))
      (node (ref "C05") (pin "L2") (pinfunction "P$2_L2") (pintype "bidirectional"))
      (node (ref "C06") (pin "L2") (pinfunction "P$2_L2") (pintype "bidirectional"))
      (node (ref "C07") (pin "L2") (pinfunction "P$2_L2") (pintype "bidirectional"))
      (node (ref "C08") (pin "L2") (pinfunction "P$2_L2") (pintype "bidirectional"))
      (node (ref "C09") (pin "L2") (pinfunction "P$2_L2") (pintype "bidirectional"))
      (node (ref "C10") (pin "L2") (pinfunction "P$2_L2") (pintype "bidirectional"))
      (node (ref "C11") (pin "L2") (pinfunction "P$2_L2") (pintype "bidirectional"))
      (node (ref "C12") (pin "L2") (pinfunction "P$2_L2") (pintype "bidirectional"))
      (node (ref "C13") (pin "L2") (pinfunction "P$2_L2") (pintype "bidirectional"))
      (node (ref "C14") (pin "L2") (pinfunction "P$2_L2") (pintype "bidirectional"))
    )
    (net (code "192") (name "Net-(C01U-P$2)") (class "Default")
      (node (ref "C01") (pin "M1") (pinfunction "P$2_M1") (pintype "bidirectional"))
      (node (ref "C02") (pin "M1") (pinfunction "P$2_M1") (pintype "bidirectional"))
      (node (ref "C03") (pin "M1") (pinfunction "P$2_M1") (pintype "bidirectional"))
      (node (ref "C04") (pin "M1") (pinfunction "P$2_M1") (pintype "bidirectional"))
      (node (ref "C05") (pin "M1") (pinfunction "P$2_M1") (pintype "bidirectional"))
      (node (ref "C06") (pin "M1") (pinfunction "P$2_M1") (pintype "bidirectional"))
      (node (ref "C07") (pin "M1") (pinfunction "P$2_M1") (pintype "bidirectional"))
      (node (ref "C08") (pin "M1") (pinfunction "P$2_M1") (pintype "bidirectional"))
      (node (ref "C09") (pin "M1") (pinfunction "P$2_M1") (pintype "bidirectional"))
      (node (ref "C10") (pin "M1") (pinfunction "P$2_M1") (pintype "bidirectional"))
      (node (ref "C11") (pin "M1") (pinfunction "P$2_M1") (pintype "bidirectional"))
      (node (ref "C12") (pin "M1") (pinfunction "P$2_M1") (pintype "bidirectional"))
      (node (ref "C13") (pin "M1") (pinfunction "P$2_M1") (pintype "bidirectional"))
      (node (ref "C14") (pin "M1") (pinfunction "P$2_M1") (pintype "bidirectional"))
    )
    (net (code "193") (name "Net-(C01V-P$2)") (class "Default")
      (node (ref "C01") (pin "M2") (pinfunction "P$2_M2") (pintype "bidirectional"))
      (node (ref "C02") (pin "M2") (pinfunction "P$2_M2") (pintype "bidirectional"))
      (node (ref "C03") (pin "M2") (pinfunction "P$2_M2") (pintype "bidirectional"))
      (node (ref "C04") (pin "M2") (pinfunction "P$2_M2") (pintype "bidirectional"))
      (node (ref "C05") (pin "M2") (pinfunction "P$2_M2") (pintype "bidirectional"))
      (node (ref "C06") (pin "M2") (pinfunction "P$2_M2") (pintype "bidirectional"))
      (node (ref "C07") (pin "M2") (pinfunction "P$2_M2") (pintype "bidirectional"))
      (node (ref "C08") (pin "M2") (pinfunction "P$2_M2") (pintype "bidirectional"))
      (node (ref "C09") (pin "M2") (pinfunction "P$2_M2") (pintype "bidirectional"))
      (node (ref "C10") (pin "M2") (pinfunction "P$2_M2") (pintype "bidirectional"))
      (node (ref "C11") (pin "M2") (pinfunction "P$2_M2") (pintype "bidirectional"))
      (node (ref "C12") (pin "M2") (pinfunction "P$2_M2") (pintype "bidirectional"))
      (node (ref "C13") (pin "M2") (pinfunction "P$2_M2") (pintype "bidirectional"))
      (node (ref "C14") (pin "M2") (pinfunction "P$2_M2") (pintype "bidirectional"))
    )
    (net (code "194") (name "Net-(C01Y-P$2)") (class "Default")
      (node (ref "C01") (pin "P1") (pinfunction "P$2_P1") (pintype "bidirectional"))
      (node (ref "C02") (pin "P1") (pinfunction "P$2_P1") (pintype "bidirectional"))
      (node (ref "C03") (pin "P1") (pinfunction "P$2_P1") (pintype "bidirectional"))
      (node (ref "C04") (pin "P1") (pinfunction "P$2_P1") (pintype "bidirectional"))
      (node (ref "C05") (pin "P1") (pinfunction "P$2_P1") (pintype "bidirectional"))
      (node (ref "C06") (pin "P1") (pinfunction "P$2_P1") (pintype "bidirectional"))
      (node (ref "C07") (pin "P1") (pinfunction "P$2_P1") (pintype "bidirectional"))
      (node (ref "C08") (pin "P1") (pinfunction "P$2_P1") (pintype "bidirectional"))
      (node (ref "C09") (pin "P1") (pinfunction "P$2_P1") (pintype "bidirectional"))
      (node (ref "C10") (pin "P1") (pinfunction "P$2_P1") (pintype "bidirectional"))
      (node (ref "C11") (pin "P1") (pinfunction "P$2_P1") (pintype "bidirectional"))
      (node (ref "C12") (pin "P1") (pinfunction "P$2_P1") (pintype "bidirectional"))
      (node (ref "C13") (pin "P1") (pinfunction "P$2_P1") (pintype "bidirectional"))
      (node (ref "C14") (pin "P1") (pinfunction "P$2_P1") (pintype "bidirectional"))
    )
    (net (code "195") (name "Net-(C01Z-P$2)") (class "Default")
      (node (ref "C01") (pin "P2") (pinfunction "P$2_P2") (pintype "bidirectional"))
      (node (ref "C02") (pin "P2") (pinfunction "P$2_P2") (pintype "bidirectional"))
      (node (ref "C03") (pin "P2") (pinfunction "P$2_P2") (pintype "bidirectional"))
      (node (ref "C04") (pin "P2") (pinfunction "P$2_P2") (pintype "bidirectional"))
      (node (ref "C05") (pin "P2") (pinfunction "P$2_P2") (pintype "bidirectional"))
      (node (ref "C06") (pin "P2") (pinfunction "P$2_P2") (pintype "bidirectional"))
      (node (ref "C07") (pin "P2") (pinfunction "P$2_P2") (pintype "bidirectional"))
      (node (ref "C08") (pin "P2") (pinfunction "P$2_P2") (pintype "bidirectional"))
      (node (ref "C09") (pin "P2") (pinfunction "P$2_P2") (pintype "bidirectional"))
      (node (ref "C10") (pin "P2") (pinfunction "P$2_P2") (pintype "bidirectional"))
      (node (ref "C11") (pin "P2") (pinfunction "P$2_P2") (pintype "bidirectional"))
      (node (ref "C12") (pin "P2") (pinfunction "P$2_P2") (pintype "bidirectional"))
      (node (ref "C13") (pin "P2") (pinfunction "P$2_P2") (pintype "bidirectional"))
      (node (ref "C14") (pin "P2") (pinfunction "P$2_P2") (pintype "bidirectional"))
    )
    (net (code "196") (name "Net-(C15A-IN2)") (class "Default")
      (node (ref "C15") (pin "B1") (pinfunction "IN2_B1") (pintype "input"))
      (node (ref "C15") (pin "C1") (pinfunction "IN3_C1") (pintype "input"))
      (node (ref "C15") (pin "D1") (pinfunction "IN4_D1") (pintype "input"))
      (node (ref "C15") (pin "H1") (pinfunction "IN2_H1") (pintype "input"))
      (node (ref "C15") (pin "J1") (pinfunction "IN3_J1") (pintype "input"))
      (node (ref "C15") (pin "K1") (pinfunction "IN4_K1") (pintype "input"))
      (node (ref "C15") (pin "N1") (pinfunction "IN2_N1") (pintype "input"))
      (node (ref "C15") (pin "P1") (pinfunction "IN3_P1") (pintype "input"))
      (node (ref "C15") (pin "R1") (pinfunction "IN4_R1") (pintype "input"))
      (node (ref "C15") (pin "V1") (pinfunction "P$1_V1") (pintype "passive"))
    )
    (net (code "197") (name "Net-(C15D-IN2)") (class "Default")
      (node (ref "C15") (pin "E2") (pinfunction "IN2_E2") (pintype "input"))
      (node (ref "C15") (pin "F2") (pinfunction "IN3_F2") (pintype "input"))
      (node (ref "C15") (pin "H2") (pinfunction "IN4_H2") (pintype "input"))
      (node (ref "C15") (pin "L2") (pinfunction "IN2_L2") (pintype "input"))
      (node (ref "C15") (pin "M2") (pinfunction "IN3_M2") (pintype "input"))
      (node (ref "C15") (pin "N2") (pinfunction "IN4_N2") (pintype "input"))
      (node (ref "C15") (pin "S2") (pinfunction "IN2_S2") (pintype "input"))
      (node (ref "C15") (pin "T2") (pinfunction "IN3_T2") (pintype "input"))
      (node (ref "C15") (pin "U1") (pinfunction "P$1_U1") (pintype "passive"))
      (node (ref "C15") (pin "U2") (pinfunction "IN4_U2") (pintype "input"))
    )
    (net (code "198") (name "Net-(C16A-IN2)") (class "Default")
      (node (ref "C16") (pin "B1") (pinfunction "IN2_B1") (pintype "input"))
      (node (ref "C16") (pin "C1") (pinfunction "IN3_C1") (pintype "input"))
      (node (ref "C16") (pin "D1") (pinfunction "IN4_D1") (pintype "input"))
      (node (ref "C16") (pin "H1") (pinfunction "IN2_H1") (pintype "input"))
      (node (ref "C16") (pin "J1") (pinfunction "IN3_J1") (pintype "input"))
      (node (ref "C16") (pin "K1") (pinfunction "IN4_K1") (pintype "input"))
      (node (ref "C16") (pin "N1") (pinfunction "IN2_N1") (pintype "input"))
      (node (ref "C16") (pin "P1") (pinfunction "IN3_P1") (pintype "input"))
      (node (ref "C16") (pin "R1") (pinfunction "IN4_R1") (pintype "input"))
      (node (ref "C16") (pin "V1") (pinfunction "P$1_V1") (pintype "passive"))
    )
    (net (code "199") (name "Net-(C16J-OUT)") (class "Default")
      (node (ref "C16") (pin "V2") (pinfunction "OUT_V2") (pintype "output"))
      (node (ref "D15") (pin "D1") (pinfunction "S_D1") (pintype "input"))
      (node (ref "D15") (pin "F2") (pinfunction "S_F2") (pintype "input"))
      (node (ref "D15") (pin "K1") (pinfunction "S_K1") (pintype "input"))
      (node (ref "D15") (pin "N2") (pinfunction "S_N2") (pintype "input"))
      (node (ref "D15") (pin "R1") (pinfunction "S_R1") (pintype "input"))
      (node (ref "D15") (pin "U2") (pinfunction "S_U2") (pintype "input"))
      (node (ref "D16") (pin "D1") (pinfunction "S_D1") (pintype "input"))
      (node (ref "D16") (pin "F2") (pinfunction "S_F2") (pintype "input"))
      (node (ref "D16") (pin "K1") (pinfunction "S_K1") (pintype "input"))
      (node (ref "D16") (pin "N2") (pinfunction "S_N2") (pintype "input"))
      (node (ref "D16") (pin "R1") (pinfunction "S_R1") (pintype "input"))
      (node (ref "D16") (pin "U2") (pinfunction "S_U2") (pintype "input"))
    )
    (net (code "200") (name "Net-(C18A-IN)") (class "Default")
      (node (ref "C18") (pin "E1") (pinfunction "IN_E1") (pintype "input"))
      (node (ref "C18") (pin "J2") (pinfunction "J2_J2") (pintype "output"))
    )
    (net (code "201") (name "Net-(C19A-IN)") (class "Default")
      (node (ref "C19") (pin "E1") (pinfunction "IN_E1") (pintype "input"))
      (node (ref "C19") (pin "L2") (pinfunction "L2_L2") (pintype "output"))
    )
    (net (code "202") (name "Net-(C19E-IN)") (class "Default")
      (node (ref "C19") (pin "H1") (pinfunction "IN_H1") (pintype "input"))
      (node (ref "C19") (pin "M2") (pinfunction "M2_M2") (pintype "output"))
    )
    (net (code "203") (name "Net-(C20A-IN)") (class "Default")
      (node (ref "C20") (pin "E1") (pinfunction "IN_E1") (pintype "input"))
      (node (ref "C20") (pin "K2") (pinfunction "K2_K2") (pintype "output"))
    )
    (net (code "204") (name "Net-(C20E-IN)") (class "Default")
      (node (ref "C20") (pin "H1") (pinfunction "IN_H1") (pintype "input"))
      (node (ref "C20") (pin "N2") (pinfunction "N2_N2") (pintype "output"))
    )
    (net (code "205") (name "Net-(D01A-P$2)") (class "Default")
      (node (ref "D01") (pin "A1") (pinfunction "P$2_A1") (pintype "bidirectional"))
      (node (ref "D02") (pin "A1") (pinfunction "P$2_A1") (pintype "bidirectional"))
      (node (ref "D03") (pin "A1") (pinfunction "P$2_A1") (pintype "bidirectional"))
      (node (ref "D04") (pin "A1") (pinfunction "P$2_A1") (pintype "bidirectional"))
      (node (ref "D05") (pin "A1") (pinfunction "P$2_A1") (pintype "bidirectional"))
      (node (ref "D06") (pin "A1") (pinfunction "P$2_A1") (pintype "bidirectional"))
      (node (ref "D07") (pin "A1") (pinfunction "P$2_A1") (pintype "bidirectional"))
      (node (ref "D08") (pin "A1") (pinfunction "P$2_A1") (pintype "bidirectional"))
      (node (ref "D09") (pin "A1") (pinfunction "P$2_A1") (pintype "bidirectional"))
      (node (ref "D10") (pin "A1") (pinfunction "P$2_A1") (pintype "bidirectional"))
      (node (ref "D11") (pin "A1") (pinfunction "P$2_A1") (pintype "bidirectional"))
      (node (ref "D12") (pin "A1") (pinfunction "P$2_A1") (pintype "bidirectional"))
      (node (ref "D13") (pin "A1") (pinfunction "P$2_A1") (pintype "bidirectional"))
      (node (ref "D14") (pin "A1") (pinfunction "P$2_A1") (pintype "bidirectional"))
    )
    (net (code "206") (name "Net-(D01AA-P$2)") (class "Default")
      (node (ref "D01") (pin "R1") (pinfunction "P$2_R1") (pintype "bidirectional"))
      (node (ref "D02") (pin "R1") (pinfunction "P$2_R1") (pintype "bidirectional"))
      (node (ref "D03") (pin "R1") (pinfunction "P$2_R1") (pintype "bidirectional"))
      (node (ref "D04") (pin "R1") (pinfunction "P$2_R1") (pintype "bidirectional"))
      (node (ref "D05") (pin "R1") (pinfunction "P$2_R1") (pintype "bidirectional"))
      (node (ref "D06") (pin "R1") (pinfunction "P$2_R1") (pintype "bidirectional"))
      (node (ref "D07") (pin "R1") (pinfunction "P$2_R1") (pintype "bidirectional"))
      (node (ref "D08") (pin "R1") (pinfunction "P$2_R1") (pintype "bidirectional"))
      (node (ref "D09") (pin "R1") (pinfunction "P$2_R1") (pintype "bidirectional"))
      (node (ref "D10") (pin "R1") (pinfunction "P$2_R1") (pintype "bidirectional"))
      (node (ref "D11") (pin "R1") (pinfunction "P$2_R1") (pintype "bidirectional"))
      (node (ref "D12") (pin "R1") (pinfunction "P$2_R1") (pintype "bidirectional"))
      (node (ref "D13") (pin "R1") (pinfunction "P$2_R1") (pintype "bidirectional"))
      (node (ref "D14") (pin "R1") (pinfunction "P$2_R1") (pintype "bidirectional"))
    )
    (net (code "207") (name "Net-(D01AB-P$2)") (class "Default")
      (node (ref "D01") (pin "R2") (pinfunction "P$2_R2") (pintype "bidirectional"))
      (node (ref "D02") (pin "R2") (pinfunction "P$2_R2") (pintype "bidirectional"))
      (node (ref "D03") (pin "R2") (pinfunction "P$2_R2") (pintype "bidirectional"))
      (node (ref "D04") (pin "R2") (pinfunction "P$2_R2") (pintype "bidirectional"))
      (node (ref "D05") (pin "R2") (pinfunction "P$2_R2") (pintype "bidirectional"))
      (node (ref "D06") (pin "R2") (pinfunction "P$2_R2") (pintype "bidirectional"))
      (node (ref "D07") (pin "R2") (pinfunction "P$2_R2") (pintype "bidirectional"))
      (node (ref "D08") (pin "R2") (pinfunction "P$2_R2") (pintype "bidirectional"))
      (node (ref "D09") (pin "R2") (pinfunction "P$2_R2") (pintype "bidirectional"))
      (node (ref "D10") (pin "R2") (pinfunction "P$2_R2") (pintype "bidirectional"))
      (node (ref "D11") (pin "R2") (pinfunction "P$2_R2") (pintype "bidirectional"))
      (node (ref "D12") (pin "R2") (pinfunction "P$2_R2") (pintype "bidirectional"))
      (node (ref "D13") (pin "R2") (pinfunction "P$2_R2") (pintype "bidirectional"))
      (node (ref "D14") (pin "R2") (pinfunction "P$2_R2") (pintype "bidirectional"))
    )
    (net (code "208") (name "Net-(D01AD-P$2)") (class "Default")
      (node (ref "D01") (pin "S2") (pinfunction "P$2_S2") (pintype "bidirectional"))
      (node (ref "D02") (pin "S2") (pinfunction "P$2_S2") (pintype "bidirectional"))
      (node (ref "D03") (pin "S2") (pinfunction "P$2_S2") (pintype "bidirectional"))
      (node (ref "D04") (pin "S2") (pinfunction "P$2_S2") (pintype "bidirectional"))
      (node (ref "D05") (pin "S2") (pinfunction "P$2_S2") (pintype "bidirectional"))
      (node (ref "D06") (pin "S2") (pinfunction "P$2_S2") (pintype "bidirectional"))
      (node (ref "D07") (pin "S2") (pinfunction "P$2_S2") (pintype "bidirectional"))
      (node (ref "D08") (pin "S2") (pinfunction "P$2_S2") (pintype "bidirectional"))
      (node (ref "D09") (pin "S2") (pinfunction "P$2_S2") (pintype "bidirectional"))
      (node (ref "D10") (pin "S2") (pinfunction "P$2_S2") (pintype "bidirectional"))
      (node (ref "D11") (pin "S2") (pinfunction "P$2_S2") (pintype "bidirectional"))
      (node (ref "D12") (pin "S2") (pinfunction "P$2_S2") (pintype "bidirectional"))
      (node (ref "D13") (pin "S2") (pinfunction "P$2_S2") (pintype "bidirectional"))
      (node (ref "D14") (pin "S2") (pinfunction "P$2_S2") (pintype "bidirectional"))
    )
    (net (code "209") (name "Net-(D01AG-P$2)") (class "Default")
      (node (ref "D01") (pin "U1") (pinfunction "P$2_U1") (pintype "bidirectional"))
      (node (ref "D02") (pin "U1") (pinfunction "P$2_U1") (pintype "bidirectional"))
      (node (ref "D03") (pin "U1") (pinfunction "P$2_U1") (pintype "bidirectional"))
      (node (ref "D04") (pin "U1") (pinfunction "P$2_U1") (pintype "bidirectional"))
      (node (ref "D05") (pin "U1") (pinfunction "P$2_U1") (pintype "bidirectional"))
      (node (ref "D06") (pin "U1") (pinfunction "P$2_U1") (pintype "bidirectional"))
      (node (ref "D07") (pin "U1") (pinfunction "P$2_U1") (pintype "bidirectional"))
      (node (ref "D08") (pin "U1") (pinfunction "P$2_U1") (pintype "bidirectional"))
      (node (ref "D09") (pin "U1") (pinfunction "P$2_U1") (pintype "bidirectional"))
      (node (ref "D10") (pin "U1") (pinfunction "P$2_U1") (pintype "bidirectional"))
      (node (ref "D11") (pin "U1") (pinfunction "P$2_U1") (pintype "bidirectional"))
      (node (ref "D12") (pin "U1") (pinfunction "P$2_U1") (pintype "bidirectional"))
      (node (ref "D13") (pin "U1") (pinfunction "P$2_U1") (pintype "bidirectional"))
      (node (ref "D14") (pin "U1") (pinfunction "P$2_U1") (pintype "bidirectional"))
    )
    (net (code "210") (name "Net-(D01AH-P$2)") (class "Default")
      (node (ref "D01") (pin "U2") (pinfunction "P$2_U2") (pintype "bidirectional"))
      (node (ref "D02") (pin "U2") (pinfunction "P$2_U2") (pintype "bidirectional"))
      (node (ref "D03") (pin "U2") (pinfunction "P$2_U2") (pintype "bidirectional"))
      (node (ref "D04") (pin "U2") (pinfunction "P$2_U2") (pintype "bidirectional"))
      (node (ref "D05") (pin "U2") (pinfunction "P$2_U2") (pintype "bidirectional"))
      (node (ref "D06") (pin "U2") (pinfunction "P$2_U2") (pintype "bidirectional"))
      (node (ref "D07") (pin "U2") (pinfunction "P$2_U2") (pintype "bidirectional"))
      (node (ref "D08") (pin "U2") (pinfunction "P$2_U2") (pintype "bidirectional"))
      (node (ref "D09") (pin "U2") (pinfunction "P$2_U2") (pintype "bidirectional"))
      (node (ref "D10") (pin "U2") (pinfunction "P$2_U2") (pintype "bidirectional"))
      (node (ref "D11") (pin "U2") (pinfunction "P$2_U2") (pintype "bidirectional"))
      (node (ref "D12") (pin "U2") (pinfunction "P$2_U2") (pintype "bidirectional"))
      (node (ref "D13") (pin "U2") (pinfunction "P$2_U2") (pintype "bidirectional"))
      (node (ref "D14") (pin "U2") (pinfunction "P$2_U2") (pintype "bidirectional"))
    )
    (net (code "211") (name "Net-(D01AI-P$2)") (class "Default")
      (node (ref "D01") (pin "V1") (pinfunction "P$2_V1") (pintype "bidirectional"))
      (node (ref "D02") (pin "V1") (pinfunction "P$2_V1") (pintype "bidirectional"))
      (node (ref "D03") (pin "V1") (pinfunction "P$2_V1") (pintype "bidirectional"))
      (node (ref "D04") (pin "V1") (pinfunction "P$2_V1") (pintype "bidirectional"))
      (node (ref "D05") (pin "V1") (pinfunction "P$2_V1") (pintype "bidirectional"))
      (node (ref "D06") (pin "V1") (pinfunction "P$2_V1") (pintype "bidirectional"))
      (node (ref "D07") (pin "V1") (pinfunction "P$2_V1") (pintype "bidirectional"))
      (node (ref "D08") (pin "V1") (pinfunction "P$2_V1") (pintype "bidirectional"))
      (node (ref "D09") (pin "V1") (pinfunction "P$2_V1") (pintype "bidirectional"))
      (node (ref "D10") (pin "V1") (pinfunction "P$2_V1") (pintype "bidirectional"))
      (node (ref "D11") (pin "V1") (pinfunction "P$2_V1") (pintype "bidirectional"))
      (node (ref "D12") (pin "V1") (pinfunction "P$2_V1") (pintype "bidirectional"))
      (node (ref "D13") (pin "V1") (pinfunction "P$2_V1") (pintype "bidirectional"))
      (node (ref "D14") (pin "V1") (pinfunction "P$2_V1") (pintype "bidirectional"))
    )
    (net (code "212") (name "Net-(D01AJ-P$2)") (class "Default")
      (node (ref "D01") (pin "V2") (pinfunction "P$2_V2") (pintype "bidirectional"))
      (node (ref "D02") (pin "V2") (pinfunction "P$2_V2") (pintype "bidirectional"))
      (node (ref "D03") (pin "V2") (pinfunction "P$2_V2") (pintype "bidirectional"))
      (node (ref "D04") (pin "V2") (pinfunction "P$2_V2") (pintype "bidirectional"))
      (node (ref "D05") (pin "V2") (pinfunction "P$2_V2") (pintype "bidirectional"))
      (node (ref "D06") (pin "V2") (pinfunction "P$2_V2") (pintype "bidirectional"))
      (node (ref "D07") (pin "V2") (pinfunction "P$2_V2") (pintype "bidirectional"))
      (node (ref "D08") (pin "V2") (pinfunction "P$2_V2") (pintype "bidirectional"))
      (node (ref "D09") (pin "V2") (pinfunction "P$2_V2") (pintype "bidirectional"))
      (node (ref "D10") (pin "V2") (pinfunction "P$2_V2") (pintype "bidirectional"))
      (node (ref "D11") (pin "V2") (pinfunction "P$2_V2") (pintype "bidirectional"))
      (node (ref "D12") (pin "V2") (pinfunction "P$2_V2") (pintype "bidirectional"))
      (node (ref "D13") (pin "V2") (pinfunction "P$2_V2") (pintype "bidirectional"))
      (node (ref "D14") (pin "V2") (pinfunction "P$2_V2") (pintype "bidirectional"))
    )
    (net (code "213") (name "Net-(D01C-P$2)") (class "Default")
      (node (ref "D01") (pin "B1") (pinfunction "P$2_B1") (pintype "bidirectional"))
      (node (ref "D02") (pin "B1") (pinfunction "P$2_B1") (pintype "bidirectional"))
      (node (ref "D03") (pin "B1") (pinfunction "P$2_B1") (pintype "bidirectional"))
      (node (ref "D04") (pin "B1") (pinfunction "P$2_B1") (pintype "bidirectional"))
      (node (ref "D05") (pin "B1") (pinfunction "P$2_B1") (pintype "bidirectional"))
      (node (ref "D06") (pin "B1") (pinfunction "P$2_B1") (pintype "bidirectional"))
      (node (ref "D07") (pin "B1") (pinfunction "P$2_B1") (pintype "bidirectional"))
      (node (ref "D08") (pin "B1") (pinfunction "P$2_B1") (pintype "bidirectional"))
      (node (ref "D09") (pin "B1") (pinfunction "P$2_B1") (pintype "bidirectional"))
      (node (ref "D10") (pin "B1") (pinfunction "P$2_B1") (pintype "bidirectional"))
      (node (ref "D11") (pin "B1") (pinfunction "P$2_B1") (pintype "bidirectional"))
      (node (ref "D12") (pin "B1") (pinfunction "P$2_B1") (pintype "bidirectional"))
      (node (ref "D13") (pin "B1") (pinfunction "P$2_B1") (pintype "bidirectional"))
      (node (ref "D14") (pin "B1") (pinfunction "P$2_B1") (pintype "bidirectional"))
    )
    (net (code "214") (name "Net-(D01H-P$2)") (class "Default")
      (node (ref "D01") (pin "D2") (pinfunction "P$2_D2") (pintype "bidirectional"))
      (node (ref "D02") (pin "D2") (pinfunction "P$2_D2") (pintype "bidirectional"))
      (node (ref "D03") (pin "D2") (pinfunction "P$2_D2") (pintype "bidirectional"))
      (node (ref "D04") (pin "D2") (pinfunction "P$2_D2") (pintype "bidirectional"))
      (node (ref "D05") (pin "D2") (pinfunction "P$2_D2") (pintype "bidirectional"))
      (node (ref "D06") (pin "D2") (pinfunction "P$2_D2") (pintype "bidirectional"))
      (node (ref "D07") (pin "D2") (pinfunction "P$2_D2") (pintype "bidirectional"))
      (node (ref "D08") (pin "D2") (pinfunction "P$2_D2") (pintype "bidirectional"))
      (node (ref "D09") (pin "D2") (pinfunction "P$2_D2") (pintype "bidirectional"))
      (node (ref "D10") (pin "D2") (pinfunction "P$2_D2") (pintype "bidirectional"))
      (node (ref "D11") (pin "D2") (pinfunction "P$2_D2") (pintype "bidirectional"))
      (node (ref "D12") (pin "D2") (pinfunction "P$2_D2") (pintype "bidirectional"))
      (node (ref "D13") (pin "D2") (pinfunction "P$2_D2") (pintype "bidirectional"))
      (node (ref "D14") (pin "D2") (pinfunction "P$2_D2") (pintype "bidirectional"))
    )
    (net (code "215") (name "Net-(D01J-P$2)") (class "Default")
      (node (ref "D01") (pin "E2") (pinfunction "P$2_E2") (pintype "bidirectional"))
      (node (ref "D02") (pin "E2") (pinfunction "P$2_E2") (pintype "bidirectional"))
      (node (ref "D03") (pin "E2") (pinfunction "P$2_E2") (pintype "bidirectional"))
      (node (ref "D04") (pin "E2") (pinfunction "P$2_E2") (pintype "bidirectional"))
      (node (ref "D05") (pin "E2") (pinfunction "P$2_E2") (pintype "bidirectional"))
      (node (ref "D06") (pin "E2") (pinfunction "P$2_E2") (pintype "bidirectional"))
      (node (ref "D07") (pin "E2") (pinfunction "P$2_E2") (pintype "bidirectional"))
      (node (ref "D08") (pin "E2") (pinfunction "P$2_E2") (pintype "bidirectional"))
      (node (ref "D09") (pin "E2") (pinfunction "P$2_E2") (pintype "bidirectional"))
      (node (ref "D10") (pin "E2") (pinfunction "P$2_E2") (pintype "bidirectional"))
      (node (ref "D11") (pin "E2") (pinfunction "P$2_E2") (pintype "bidirectional"))
      (node (ref "D12") (pin "E2") (pinfunction "P$2_E2") (pintype "bidirectional"))
      (node (ref "D13") (pin "E2") (pinfunction "P$2_E2") (pintype "bidirectional"))
      (node (ref "D14") (pin "E2") (pinfunction "P$2_E2") (pintype "bidirectional"))
    )
    (net (code "216") (name "Net-(D01N-P$2)") (class "Default")
      (node (ref "D01") (pin "H2") (pinfunction "P$2_H2") (pintype "bidirectional"))
      (node (ref "D02") (pin "H2") (pinfunction "P$2_H2") (pintype "bidirectional"))
      (node (ref "D03") (pin "H2") (pinfunction "P$2_H2") (pintype "bidirectional"))
      (node (ref "D04") (pin "H2") (pinfunction "P$2_H2") (pintype "bidirectional"))
      (node (ref "D05") (pin "H2") (pinfunction "P$2_H2") (pintype "bidirectional"))
      (node (ref "D06") (pin "H2") (pinfunction "P$2_H2") (pintype "bidirectional"))
      (node (ref "D07") (pin "H2") (pinfunction "P$2_H2") (pintype "bidirectional"))
      (node (ref "D08") (pin "H2") (pinfunction "P$2_H2") (pintype "bidirectional"))
      (node (ref "D09") (pin "H2") (pinfunction "P$2_H2") (pintype "bidirectional"))
      (node (ref "D10") (pin "H2") (pinfunction "P$2_H2") (pintype "bidirectional"))
      (node (ref "D11") (pin "H2") (pinfunction "P$2_H2") (pintype "bidirectional"))
      (node (ref "D12") (pin "H2") (pinfunction "P$2_H2") (pintype "bidirectional"))
      (node (ref "D13") (pin "H2") (pinfunction "P$2_H2") (pintype "bidirectional"))
      (node (ref "D14") (pin "H2") (pinfunction "P$2_H2") (pintype "bidirectional"))
    )
    (net (code "217") (name "Net-(D01P-P$2)") (class "Default")
      (node (ref "D01") (pin "J2") (pinfunction "P$2_J2") (pintype "bidirectional"))
      (node (ref "D02") (pin "J2") (pinfunction "P$2_J2") (pintype "bidirectional"))
      (node (ref "D03") (pin "J2") (pinfunction "P$2_J2") (pintype "bidirectional"))
      (node (ref "D04") (pin "J2") (pinfunction "P$2_J2") (pintype "bidirectional"))
      (node (ref "D05") (pin "J2") (pinfunction "P$2_J2") (pintype "bidirectional"))
      (node (ref "D06") (pin "J2") (pinfunction "P$2_J2") (pintype "bidirectional"))
      (node (ref "D07") (pin "J2") (pinfunction "P$2_J2") (pintype "bidirectional"))
      (node (ref "D08") (pin "J2") (pinfunction "P$2_J2") (pintype "bidirectional"))
      (node (ref "D09") (pin "J2") (pinfunction "P$2_J2") (pintype "bidirectional"))
      (node (ref "D10") (pin "J2") (pinfunction "P$2_J2") (pintype "bidirectional"))
      (node (ref "D11") (pin "J2") (pinfunction "P$2_J2") (pintype "bidirectional"))
      (node (ref "D12") (pin "J2") (pinfunction "P$2_J2") (pintype "bidirectional"))
      (node (ref "D13") (pin "J2") (pinfunction "P$2_J2") (pintype "bidirectional"))
      (node (ref "D14") (pin "J2") (pinfunction "P$2_J2") (pintype "bidirectional"))
    )
    (net (code "218") (name "Net-(D01R-P$2)") (class "Default")
      (node (ref "D01") (pin "K2") (pinfunction "P$2_K2") (pintype "bidirectional"))
      (node (ref "D02") (pin "K2") (pinfunction "P$2_K2") (pintype "bidirectional"))
      (node (ref "D03") (pin "K2") (pinfunction "P$2_K2") (pintype "bidirectional"))
      (node (ref "D04") (pin "K2") (pinfunction "P$2_K2") (pintype "bidirectional"))
      (node (ref "D05") (pin "K2") (pinfunction "P$2_K2") (pintype "bidirectional"))
      (node (ref "D06") (pin "K2") (pinfunction "P$2_K2") (pintype "bidirectional"))
      (node (ref "D07") (pin "K2") (pinfunction "P$2_K2") (pintype "bidirectional"))
      (node (ref "D08") (pin "K2") (pinfunction "P$2_K2") (pintype "bidirectional"))
      (node (ref "D09") (pin "K2") (pinfunction "P$2_K2") (pintype "bidirectional"))
      (node (ref "D10") (pin "K2") (pinfunction "P$2_K2") (pintype "bidirectional"))
      (node (ref "D11") (pin "K2") (pinfunction "P$2_K2") (pintype "bidirectional"))
      (node (ref "D12") (pin "K2") (pinfunction "P$2_K2") (pintype "bidirectional"))
      (node (ref "D13") (pin "K2") (pinfunction "P$2_K2") (pintype "bidirectional"))
      (node (ref "D14") (pin "K2") (pinfunction "P$2_K2") (pintype "bidirectional"))
    )
    (net (code "219") (name "Net-(D01T-P$2)") (class "Default")
      (node (ref "D01") (pin "L2") (pinfunction "P$2_L2") (pintype "bidirectional"))
      (node (ref "D02") (pin "L2") (pinfunction "P$2_L2") (pintype "bidirectional"))
      (node (ref "D03") (pin "L2") (pinfunction "P$2_L2") (pintype "bidirectional"))
      (node (ref "D04") (pin "L2") (pinfunction "P$2_L2") (pintype "bidirectional"))
      (node (ref "D05") (pin "L2") (pinfunction "P$2_L2") (pintype "bidirectional"))
      (node (ref "D06") (pin "L2") (pinfunction "P$2_L2") (pintype "bidirectional"))
      (node (ref "D07") (pin "L2") (pinfunction "P$2_L2") (pintype "bidirectional"))
      (node (ref "D08") (pin "L2") (pinfunction "P$2_L2") (pintype "bidirectional"))
      (node (ref "D09") (pin "L2") (pinfunction "P$2_L2") (pintype "bidirectional"))
      (node (ref "D10") (pin "L2") (pinfunction "P$2_L2") (pintype "bidirectional"))
      (node (ref "D11") (pin "L2") (pinfunction "P$2_L2") (pintype "bidirectional"))
      (node (ref "D12") (pin "L2") (pinfunction "P$2_L2") (pintype "bidirectional"))
      (node (ref "D13") (pin "L2") (pinfunction "P$2_L2") (pintype "bidirectional"))
      (node (ref "D14") (pin "L2") (pinfunction "P$2_L2") (pintype "bidirectional"))
    )
    (net (code "220") (name "Net-(D01V-P$2)") (class "Default")
      (node (ref "D01") (pin "M2") (pinfunction "P$2_M2") (pintype "bidirectional"))
      (node (ref "D02") (pin "M2") (pinfunction "P$2_M2") (pintype "bidirectional"))
      (node (ref "D03") (pin "M2") (pinfunction "P$2_M2") (pintype "bidirectional"))
      (node (ref "D04") (pin "M2") (pinfunction "P$2_M2") (pintype "bidirectional"))
      (node (ref "D05") (pin "M2") (pinfunction "P$2_M2") (pintype "bidirectional"))
      (node (ref "D06") (pin "M2") (pinfunction "P$2_M2") (pintype "bidirectional"))
      (node (ref "D07") (pin "M2") (pinfunction "P$2_M2") (pintype "bidirectional"))
      (node (ref "D08") (pin "M2") (pinfunction "P$2_M2") (pintype "bidirectional"))
      (node (ref "D09") (pin "M2") (pinfunction "P$2_M2") (pintype "bidirectional"))
      (node (ref "D10") (pin "M2") (pinfunction "P$2_M2") (pintype "bidirectional"))
      (node (ref "D11") (pin "M2") (pinfunction "P$2_M2") (pintype "bidirectional"))
      (node (ref "D12") (pin "M2") (pinfunction "P$2_M2") (pintype "bidirectional"))
      (node (ref "D13") (pin "M2") (pinfunction "P$2_M2") (pintype "bidirectional"))
      (node (ref "D14") (pin "M2") (pinfunction "P$2_M2") (pintype "bidirectional"))
    )
    (net (code "221") (name "Net-(D01Z-P$2)") (class "Default")
      (node (ref "D01") (pin "P2") (pinfunction "P$2_P2") (pintype "bidirectional"))
      (node (ref "D02") (pin "P2") (pinfunction "P$2_P2") (pintype "bidirectional"))
      (node (ref "D03") (pin "P2") (pinfunction "P$2_P2") (pintype "bidirectional"))
      (node (ref "D04") (pin "P2") (pinfunction "P$2_P2") (pintype "bidirectional"))
      (node (ref "D05") (pin "P2") (pinfunction "P$2_P2") (pintype "bidirectional"))
      (node (ref "D06") (pin "P2") (pinfunction "P$2_P2") (pintype "bidirectional"))
      (node (ref "D07") (pin "P2") (pinfunction "P$2_P2") (pintype "bidirectional"))
      (node (ref "D08") (pin "P2") (pinfunction "P$2_P2") (pintype "bidirectional"))
      (node (ref "D09") (pin "P2") (pinfunction "P$2_P2") (pintype "bidirectional"))
      (node (ref "D10") (pin "P2") (pinfunction "P$2_P2") (pintype "bidirectional"))
      (node (ref "D11") (pin "P2") (pinfunction "P$2_P2") (pintype "bidirectional"))
      (node (ref "D12") (pin "P2") (pinfunction "P$2_P2") (pintype "bidirectional"))
      (node (ref "D13") (pin "P2") (pinfunction "P$2_P2") (pintype "bidirectional"))
      (node (ref "D14") (pin "P2") (pinfunction "P$2_P2") (pintype "bidirectional"))
    )
    (net (code "222") (name "Net-(D18B-OUT)") (class "Default")
      (node (ref "D18") (pin "D2") (pinfunction "OUT_D2") (pintype "output"))
      (node (ref "D19") (pin "B1") (pinfunction "L2_B1") (pintype "bidirectional"))
    )
    (net (code "223") (name "Net-(D18H-OUT)") (class "Default")
      (node (ref "D18") (pin "J2") (pinfunction "OUT_J2") (pintype "output"))
      (node (ref "D19") (pin "C1") (pinfunction "L3_C1") (pintype "bidirectional"))
    )
    (net (code "224") (name "VCC") (class "Default")
      (node (ref "+5V") (pin "1") (pinfunction "P_1") (pintype "passive"))
      (node (ref "A01") (pin "A2") (pinfunction "P$2_A2") (pintype "bidirectional"))
      (node (ref "A02") (pin "A2") (pinfunction "P$2_A2") (pintype "bidirectional"))
      (node (ref "A03") (pin "A2") (pinfunction "P$2_A2") (pintype "bidirectional"))
      (node (ref "A04") (pin "A2") (pinfunction "P$2_A2") (pintype "bidirectional"))
      (node (ref "A05") (pin "A2") (pinfunction "P$2_A2") (pintype "bidirectional"))
      (node (ref "A06") (pin "A2") (pinfunction "P$2_A2") (pintype "bidirectional"))
      (node (ref "A07") (pin "A2") (pinfunction "P$2_A2") (pintype "bidirectional"))
      (node (ref "A08") (pin "A2") (pinfunction "P$2_A2") (pintype "bidirectional"))
      (node (ref "A09") (pin "A2") (pinfunction "P$2_A2") (pintype "bidirectional"))
      (node (ref "A10") (pin "A2") (pinfunction "P$2_A2") (pintype "bidirectional"))
      (node (ref "A11") (pin "A2") (pinfunction "P$2_A2") (pintype "bidirectional"))
      (node (ref "A12") (pin "A2") (pinfunction "P$2_A2") (pintype "bidirectional"))
      (node (ref "A13") (pin "A2") (pinfunction "P$2_A2") (pintype "bidirectional"))
      (node (ref "A14") (pin "A2") (pinfunction "P$2_A2") (pintype "bidirectional"))
      (node (ref "B01") (pin "A2") (pinfunction "P$2_A2") (pintype "bidirectional"))
      (node (ref "B02") (pin "A2") (pinfunction "P$2_A2") (pintype "bidirectional"))
      (node (ref "B03") (pin "A2") (pinfunction "P$2_A2") (pintype "bidirectional"))
      (node (ref "B04") (pin "A2") (pinfunction "P$2_A2") (pintype "bidirectional"))
      (node (ref "B05") (pin "A2") (pinfunction "P$2_A2") (pintype "bidirectional"))
      (node (ref "B06") (pin "A2") (pinfunction "P$2_A2") (pintype "bidirectional"))
      (node (ref "B07") (pin "A2") (pinfunction "P$2_A2") (pintype "bidirectional"))
      (node (ref "B08") (pin "A2") (pinfunction "P$2_A2") (pintype "bidirectional"))
      (node (ref "B09") (pin "A2") (pinfunction "P$2_A2") (pintype "bidirectional"))
      (node (ref "B10") (pin "A2") (pinfunction "P$2_A2") (pintype "bidirectional"))
      (node (ref "B11") (pin "A2") (pinfunction "P$2_A2") (pintype "bidirectional"))
      (node (ref "B12") (pin "A2") (pinfunction "P$2_A2") (pintype "bidirectional"))
      (node (ref "B13") (pin "A2") (pinfunction "P$2_A2") (pintype "bidirectional"))
      (node (ref "B14") (pin "A2") (pinfunction "P$2_A2") (pintype "bidirectional"))
      (node (ref "C01") (pin "A2") (pinfunction "P$2_A2") (pintype "bidirectional"))
      (node (ref "C02") (pin "A2") (pinfunction "P$2_A2") (pintype "bidirectional"))
      (node (ref "C03") (pin "A2") (pinfunction "P$2_A2") (pintype "bidirectional"))
      (node (ref "C04") (pin "A2") (pinfunction "P$2_A2") (pintype "bidirectional"))
      (node (ref "C05") (pin "A2") (pinfunction "P$2_A2") (pintype "bidirectional"))
      (node (ref "C06") (pin "A2") (pinfunction "P$2_A2") (pintype "bidirectional"))
      (node (ref "C07") (pin "A2") (pinfunction "P$2_A2") (pintype "bidirectional"))
      (node (ref "C08") (pin "A2") (pinfunction "P$2_A2") (pintype "bidirectional"))
      (node (ref "C09") (pin "A2") (pinfunction "P$2_A2") (pintype "bidirectional"))
      (node (ref "C10") (pin "A2") (pinfunction "P$2_A2") (pintype "bidirectional"))
      (node (ref "C11") (pin "A2") (pinfunction "P$2_A2") (pintype "bidirectional"))
      (node (ref "C12") (pin "A2") (pinfunction "P$2_A2") (pintype "bidirectional"))
      (node (ref "C13") (pin "A2") (pinfunction "P$2_A2") (pintype "bidirectional"))
      (node (ref "C14") (pin "A2") (pinfunction "P$2_A2") (pintype "bidirectional"))
      (node (ref "D01") (pin "A2") (pinfunction "P$2_A2") (pintype "bidirectional"))
      (node (ref "D02") (pin "A2") (pinfunction "P$2_A2") (pintype "bidirectional"))
      (node (ref "D03") (pin "A2") (pinfunction "P$2_A2") (pintype "bidirectional"))
      (node (ref "D04") (pin "A2") (pinfunction "P$2_A2") (pintype "bidirectional"))
      (node (ref "D05") (pin "A2") (pinfunction "P$2_A2") (pintype "bidirectional"))
      (node (ref "D06") (pin "A2") (pinfunction "P$2_A2") (pintype "bidirectional"))
      (node (ref "D07") (pin "A2") (pinfunction "P$2_A2") (pintype "bidirectional"))
      (node (ref "D08") (pin "A2") (pinfunction "P$2_A2") (pintype "bidirectional"))
      (node (ref "D09") (pin "A2") (pinfunction "P$2_A2") (pintype "bidirectional"))
      (node (ref "D10") (pin "A2") (pinfunction "P$2_A2") (pintype "bidirectional"))
      (node (ref "D11") (pin "A2") (pinfunction "P$2_A2") (pintype "bidirectional"))
      (node (ref "D12") (pin "A2") (pinfunction "P$2_A2") (pintype "bidirectional"))
      (node (ref "D13") (pin "A2") (pinfunction "P$2_A2") (pintype "bidirectional"))
      (node (ref "D14") (pin "A2") (pinfunction "P$2_A2") (pintype "bidirectional"))
    )
    (net (code "225") (name "unconnected-(C17D-1-PadH2)") (class "Default")
      (node (ref "C17") (pin "H2") (pinfunction "1_H2") (pintype "output"))
    )
    (net (code "226") (name "unconnected-(C17E-1-PadL1)") (class "Default")
      (node (ref "C17") (pin "L1") (pinfunction "1_L1") (pintype "output"))
    )
    (net (code "227") (name "unconnected-(C17F-1-PadP2)") (class "Default")
      (node (ref "C17") (pin "P2") (pinfunction "1_P2") (pintype "output"))
    )
    (net (code "228") (name "unconnected-(C17H-1-PadV2)") (class "Default")
      (node (ref "C17") (pin "V2") (pinfunction "1_V2") (pintype "output"))
    )
    (net (code "229") (name "unconnected-(C18-PadK2)") (class "Default")
      (node (ref "C18") (pin "K2") (pinfunction "K2_K2") (pintype "output"))
    )
    (net (code "230") (name "unconnected-(C18-PadL2)") (class "Default")
      (node (ref "C18") (pin "L2") (pinfunction "L2_L2") (pintype "output"))
    )
    (net (code "231") (name "unconnected-(C18-PadM2)") (class "Default")
      (node (ref "C18") (pin "M2") (pinfunction "M2_M2") (pintype "output"))
    )
    (net (code "232") (name "unconnected-(C18-PadN2)") (class "Default")
      (node (ref "C18") (pin "N2") (pinfunction "N2_N2") (pintype "output"))
    )
    (net (code "233") (name "unconnected-(C18-PadP2)") (class "Default")
      (node (ref "C18") (pin "P2") (pinfunction "P2_P2") (pintype "output"))
    )
    (net (code "234") (name "unconnected-(C18-PadR2)") (class "Default")
      (node (ref "C18") (pin "R2") (pinfunction "R2_R2") (pintype "output"))
    )
    (net (code "235") (name "unconnected-(C18-PadS2)") (class "Default")
      (node (ref "C18") (pin "S2") (pinfunction "S2_S2") (pintype "output"))
    )
    (net (code "236") (name "unconnected-(C18-PadT2)") (class "Default")
      (node (ref "C18") (pin "T2") (pinfunction "T2_T2") (pintype "output"))
    )
    (net (code "237") (name "unconnected-(C18-PadU2)") (class "Default")
      (node (ref "C18") (pin "U2") (pinfunction "U2_U2") (pintype "output"))
    )
    (net (code "238") (name "unconnected-(C18-PadV2)") (class "Default")
      (node (ref "C18") (pin "V2") (pinfunction "V2_V2") (pintype "output"))
    )
    (net (code "239") (name "unconnected-(C19-PadJ2)") (class "Default")
      (node (ref "C19") (pin "J2") (pinfunction "J2_J2") (pintype "output"))
    )
    (net (code "240") (name "unconnected-(C19-PadK2)") (class "Default")
      (node (ref "C19") (pin "K2") (pinfunction "K2_K2") (pintype "output"))
    )
    (net (code "241") (name "unconnected-(C19-PadN2)") (class "Default")
      (node (ref "C19") (pin "N2") (pinfunction "N2_N2") (pintype "output"))
    )
    (net (code "242") (name "unconnected-(C19-PadP2)") (class "Default")
      (node (ref "C19") (pin "P2") (pinfunction "P2_P2") (pintype "output"))
    )
    (net (code "243") (name "unconnected-(C19-PadR2)") (class "Default")
      (node (ref "C19") (pin "R2") (pinfunction "R2_R2") (pintype "output"))
    )
    (net (code "244") (name "unconnected-(C19-PadS2)") (class "Default")
      (node (ref "C19") (pin "S2") (pinfunction "S2_S2") (pintype "output"))
    )
    (net (code "245") (name "unconnected-(C19-PadT2)") (class "Default")
      (node (ref "C19") (pin "T2") (pinfunction "T2_T2") (pintype "output"))
    )
    (net (code "246") (name "unconnected-(C19-PadU2)") (class "Default")
      (node (ref "C19") (pin "U2") (pinfunction "U2_U2") (pintype "output"))
    )
    (net (code "247") (name "unconnected-(C19-PadV2)") (class "Default")
      (node (ref "C19") (pin "V2") (pinfunction "V2_V2") (pintype "output"))
    )
    (net (code "248") (name "unconnected-(C20-PadJ2)") (class "Default")
      (node (ref "C20") (pin "J2") (pinfunction "J2_J2") (pintype "output"))
    )
    (net (code "249") (name "unconnected-(C20-PadL2)") (class "Default")
      (node (ref "C20") (pin "L2") (pinfunction "L2_L2") (pintype "output"))
    )
    (net (code "250") (name "unconnected-(C20-PadM2)") (class "Default")
      (node (ref "C20") (pin "M2") (pinfunction "M2_M2") (pintype "output"))
    )
    (net (code "251") (name "unconnected-(C20-PadP2)") (class "Default")
      (node (ref "C20") (pin "P2") (pinfunction "P2_P2") (pintype "output"))
    )
    (net (code "252") (name "unconnected-(C20-PadR2)") (class "Default")
      (node (ref "C20") (pin "R2") (pinfunction "R2_R2") (pintype "output"))
    )
    (net (code "253") (name "unconnected-(C20-PadS2)") (class "Default")
      (node (ref "C20") (pin "S2") (pinfunction "S2_S2") (pintype "output"))
    )
    (net (code "254") (name "unconnected-(C20-PadT2)") (class "Default")
      (node (ref "C20") (pin "T2") (pinfunction "T2_T2") (pintype "output"))
    )
    (net (code "255") (name "unconnected-(C20-PadU2)") (class "Default")
      (node (ref "C20") (pin "U2") (pinfunction "U2_U2") (pintype "output"))
    )
    (net (code "256") (name "unconnected-(C20-PadV2)") (class "Default")
      (node (ref "C20") (pin "V2") (pinfunction "V2_V2") (pintype "output"))
    )
    (net (code "257") (name "unconnected-(D15A-1-PadE1)") (class "Default")
      (node (ref "D15") (pin "E1") (pinfunction "1_E1") (pintype "output"))
    )
    (net (code "258") (name "unconnected-(D15D-1-PadH2)") (class "Default")
      (node (ref "D15") (pin "H2") (pinfunction "1_H2") (pintype "output"))
    )
    (net (code "259") (name "unconnected-(D15E-1-PadL1)") (class "Default")
      (node (ref "D15") (pin "L1") (pinfunction "1_L1") (pintype "output"))
    )
    (net (code "260") (name "unconnected-(D15F-1-PadP2)") (class "Default")
      (node (ref "D15") (pin "P2") (pinfunction "1_P2") (pintype "output"))
    )
    (net (code "261") (name "unconnected-(D15G-1-PadS1)") (class "Default")
      (node (ref "D15") (pin "S1") (pinfunction "1_S1") (pintype "output"))
    )
    (net (code "262") (name "unconnected-(D15H-1-PadV2)") (class "Default")
      (node (ref "D15") (pin "V2") (pinfunction "1_V2") (pintype "output"))
    )
    (net (code "263") (name "unconnected-(D16A-1-PadE1)") (class "Default")
      (node (ref "D16") (pin "E1") (pinfunction "1_E1") (pintype "output"))
    )
    (net (code "264") (name "unconnected-(D16D-1-PadH2)") (class "Default")
      (node (ref "D16") (pin "H2") (pinfunction "1_H2") (pintype "output"))
    )
    (net (code "265") (name "unconnected-(D16E-1-PadL1)") (class "Default")
      (node (ref "D16") (pin "L1") (pinfunction "1_L1") (pintype "output"))
    )
    (net (code "266") (name "unconnected-(D16F-1-PadP2)") (class "Default")
      (node (ref "D16") (pin "P2") (pinfunction "1_P2") (pintype "output"))
    )
    (net (code "267") (name "unconnected-(D16G-1-PadS1)") (class "Default")
      (node (ref "D16") (pin "S1") (pinfunction "1_S1") (pintype "output"))
    )
    (net (code "268") (name "unconnected-(D16H-1-PadV2)") (class "Default")
      (node (ref "D16") (pin "V2") (pinfunction "1_V2") (pintype "output"))
    )
    (net (code "269") (name "unconnected-(D17F-1-PadP2)") (class "Default")
      (node (ref "D17") (pin "P2") (pinfunction "1_P2") (pintype "output"))
    )
    (net (code "270") (name "unconnected-(D17G-1-PadS1)") (class "Default")
      (node (ref "D17") (pin "S1") (pinfunction "1_S1") (pintype "output"))
    )
    (net (code "271") (name "unconnected-(D17H-1-PadV2)") (class "Default")
      (node (ref "D17") (pin "V2") (pinfunction "1_V2") (pintype "output"))
    )
    (net (code "272") (name "unconnected-(D19A-R2-PadE2)") (class "Default")
      (node (ref "D19") (pin "E2") (pinfunction "R2_E2") (pintype "bidirectional"))
    )
    (net (code "273") (name "unconnected-(D19B-R2-PadH2)") (class "Default")
      (node (ref "D19") (pin "H2") (pinfunction "R2_H2") (pintype "bidirectional"))
    )
    (net (code "274") (name "unconnected-(D19C-L3-PadK1)") (class "Default")
      (node (ref "D19") (pin "K1") (pinfunction "L3_K1") (pintype "bidirectional"))
    )
    (net (code "275") (name "unconnected-(D19C-R2-PadK2)") (class "Default")
      (node (ref "D19") (pin "K2") (pinfunction "R2_K2") (pintype "bidirectional"))
    )
    (net (code "276") (name "unconnected-(D19D-L3-PadN1)") (class "Default")
      (node (ref "D19") (pin "N1") (pinfunction "L3_N1") (pintype "bidirectional"))
    )
    (net (code "277") (name "unconnected-(D19D-R2-PadM2)") (class "Default")
      (node (ref "D19") (pin "M2") (pinfunction "R2_M2") (pintype "bidirectional"))
    )
  )
)
